# SMPS.net
KiCad netlist of a schematic drawn in Altium Designer
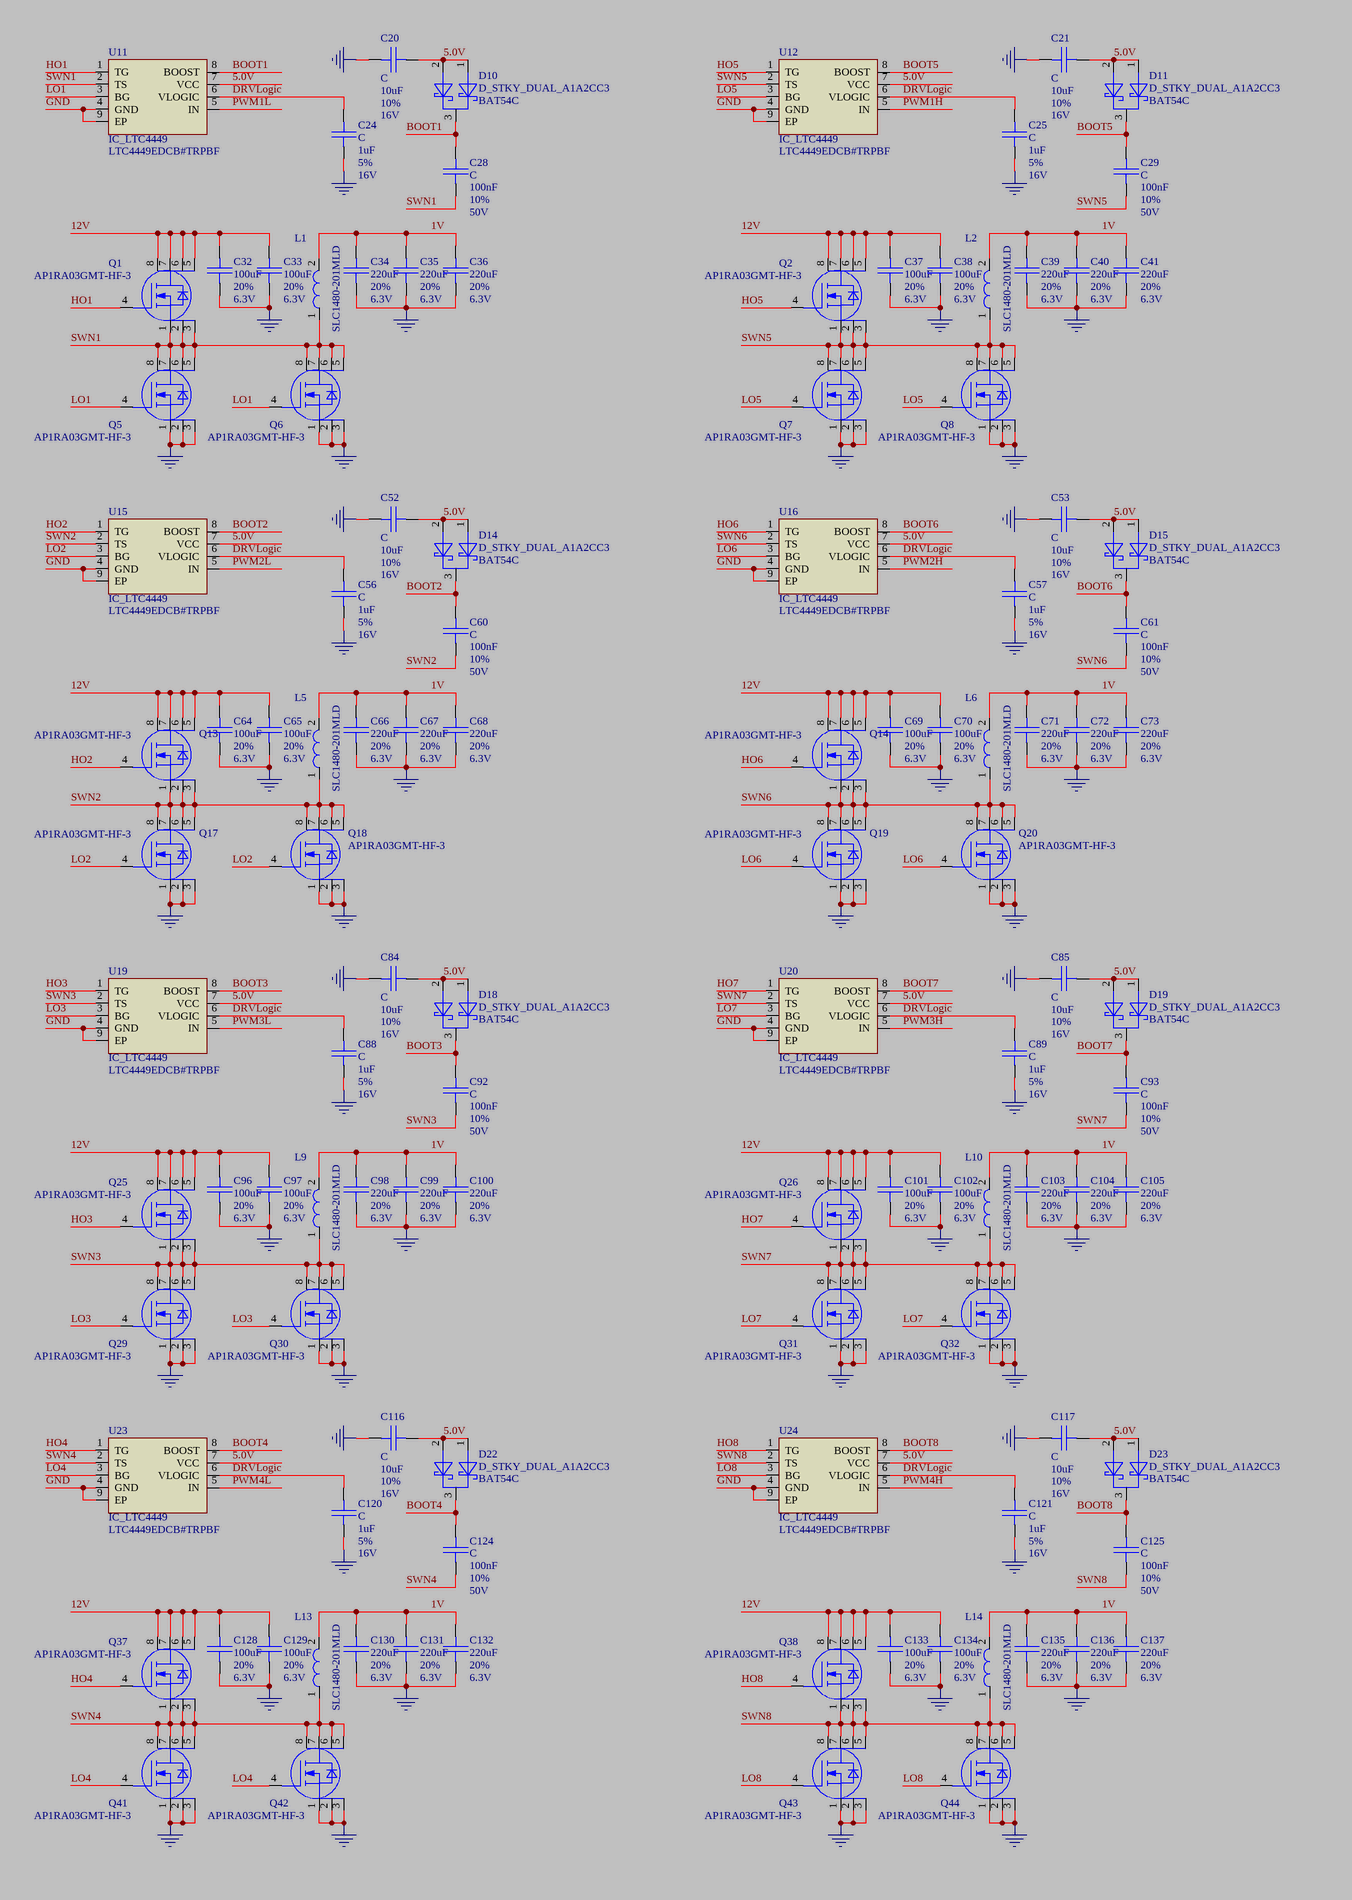
[diagram p0: SMPS.SchDoc, left]
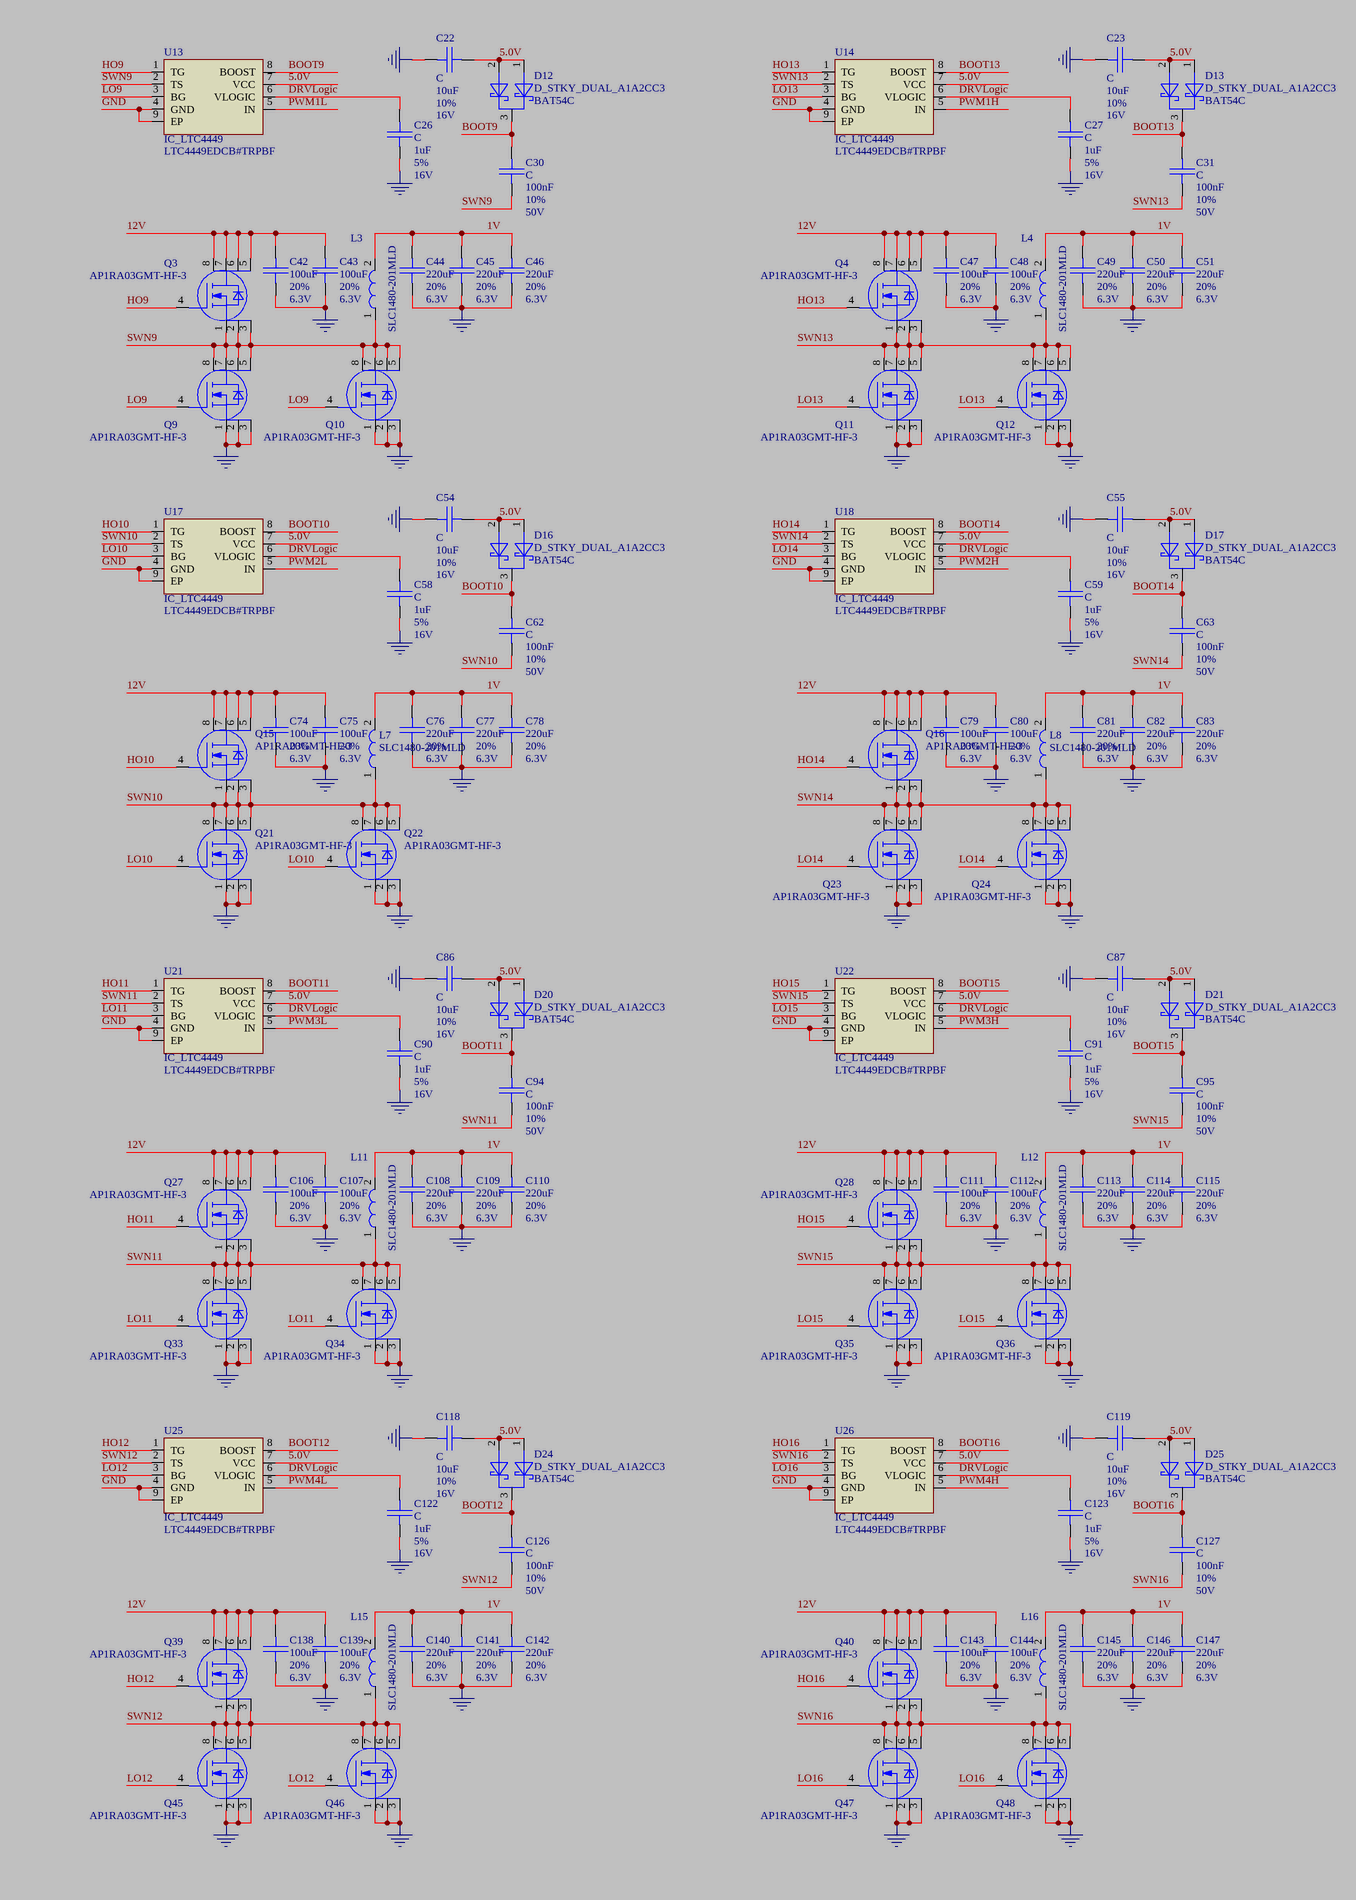
[diagram p1: SMPS.SchDoc, right]

(export (version "E")
  (design (tool "Eeschema 10.0.6"))
  (components
    (comp (ref "C20")
      (value "C")
      (footprint "SMD_0805_CAPC2012X145N")
      (fields
        (field (name "DB_PART_NUMBER") "CAP000043636")
        (field (name "DB_VALUE") "10uF")
        (field (name "DB_TOLERANCE") "10%")
        (field (name "DB_VOLTAGE") "16V")
        (field (name "DB_MANUFACTURER_PART") "KEMET    C0805C106K4PAC")
        (field (name "DB_APPROVED_BY") "ISHIDDEN=T")
      )
      (libsource (lib "Database_Libs1") (part "C"))
    )
    (comp (ref "C21")
      (value "C")
      (footprint "SMD_0805_CAPC2012X145N")
      (fields
        (field (name "DB_PART_NUMBER") "CAP000043636")
        (field (name "DB_VALUE") "10uF")
        (field (name "DB_TOLERANCE") "10%")
        (field (name "DB_VOLTAGE") "16V")
        (field (name "DB_MANUFACTURER_PART") "KEMET    C0805C106K4PAC")
        (field (name "DB_APPROVED_BY") "ISHIDDEN=T")
      )
      (libsource (lib "Database_Libs1") (part "C"))
    )
    (comp (ref "C22")
      (value "C")
      (footprint "SMD_0805_CAPC2012X145N")
      (fields
        (field (name "DB_PART_NUMBER") "CAP000043636")
        (field (name "DB_VALUE") "10uF")
        (field (name "DB_TOLERANCE") "10%")
        (field (name "DB_VOLTAGE") "16V")
        (field (name "DB_MANUFACTURER_PART") "KEMET    C0805C106K4PAC")
        (field (name "DB_APPROVED_BY") "ISHIDDEN=T")
      )
      (libsource (lib "Database_Libs1") (part "C"))
    )
    (comp (ref "C23")
      (value "C")
      (footprint "SMD_0805_CAPC2012X145N")
      (fields
        (field (name "DB_PART_NUMBER") "CAP000043636")
        (field (name "DB_VALUE") "10uF")
        (field (name "DB_TOLERANCE") "10%")
        (field (name "DB_VOLTAGE") "16V")
        (field (name "DB_MANUFACTURER_PART") "KEMET    C0805C106K4PAC")
        (field (name "DB_APPROVED_BY") "ISHIDDEN=T")
      )
      (libsource (lib "Database_Libs1") (part "C"))
    )
    (comp (ref "C24")
      (value "C")
      (footprint "SMD_0805_CAPC2012X145N")
      (fields
        (field (name "DB_PART_NUMBER") "CAP000028589")
        (field (name "DB_VALUE") "1uF")
        (field (name "DB_TOLERANCE") "5%")
        (field (name "DB_VOLTAGE") "16V")
        (field (name "DB_MANUFACTURER_PART") "KEMET    C0805C105J4RAC")
        (field (name "DB_APPROVED_BY") "ISHIDDEN=T")
      )
      (libsource (lib "Database_Libs1") (part "C"))
    )
    (comp (ref "C25")
      (value "C")
      (footprint "SMD_0805_CAPC2012X145N")
      (fields
        (field (name "DB_PART_NUMBER") "CAP000028589")
        (field (name "DB_VALUE") "1uF")
        (field (name "DB_TOLERANCE") "5%")
        (field (name "DB_VOLTAGE") "16V")
        (field (name "DB_MANUFACTURER_PART") "KEMET    C0805C105J4RAC")
        (field (name "DB_APPROVED_BY") "ISHIDDEN=T")
      )
      (libsource (lib "Database_Libs1") (part "C"))
    )
    (comp (ref "C26")
      (value "C")
      (footprint "SMD_0805_CAPC2012X145N")
      (fields
        (field (name "DB_PART_NUMBER") "CAP000028589")
        (field (name "DB_VALUE") "1uF")
        (field (name "DB_TOLERANCE") "5%")
        (field (name "DB_VOLTAGE") "16V")
        (field (name "DB_MANUFACTURER_PART") "KEMET    C0805C105J4RAC")
        (field (name "DB_APPROVED_BY") "ISHIDDEN=T")
      )
      (libsource (lib "Database_Libs1") (part "C"))
    )
    (comp (ref "C27")
      (value "C")
      (footprint "SMD_0805_CAPC2012X145N")
      (fields
        (field (name "DB_PART_NUMBER") "CAP000028589")
        (field (name "DB_VALUE") "1uF")
        (field (name "DB_TOLERANCE") "5%")
        (field (name "DB_VOLTAGE") "16V")
        (field (name "DB_MANUFACTURER_PART") "KEMET    C0805C105J4RAC")
        (field (name "DB_APPROVED_BY") "ISHIDDEN=T")
      )
      (libsource (lib "Database_Libs1") (part "C"))
    )
    (comp (ref "C28")
      (value "C")
      (footprint "SMD_0805_CAPC2012X145N")
      (fields
        (field (name "DB_PART_NUMBER") "CAP000027193")
        (field (name "DB_VALUE") "100nF")
        (field (name "DB_TOLERANCE") "10%")
        (field (name "DB_VOLTAGE") "50V")
        (field (name "DB_MANUFACTURER_PART") "KEMET    C0805C104K5RAC")
        (field (name "DB_APPROVED_BY") "ISHIDDEN=T")
      )
      (libsource (lib "Database_Libs1") (part "C"))
    )
    (comp (ref "C29")
      (value "C")
      (footprint "SMD_0805_CAPC2012X145N")
      (fields
        (field (name "DB_PART_NUMBER") "CAP000027193")
        (field (name "DB_VALUE") "100nF")
        (field (name "DB_TOLERANCE") "10%")
        (field (name "DB_VOLTAGE") "50V")
        (field (name "DB_MANUFACTURER_PART") "KEMET    C0805C104K5RAC")
        (field (name "DB_APPROVED_BY") "ISHIDDEN=T")
      )
      (libsource (lib "Database_Libs1") (part "C"))
    )
    (comp (ref "C30")
      (value "C")
      (footprint "SMD_0805_CAPC2012X145N")
      (fields
        (field (name "DB_PART_NUMBER") "CAP000027193")
        (field (name "DB_VALUE") "100nF")
        (field (name "DB_TOLERANCE") "10%")
        (field (name "DB_VOLTAGE") "50V")
        (field (name "DB_MANUFACTURER_PART") "KEMET    C0805C104K5RAC")
        (field (name "DB_APPROVED_BY") "ISHIDDEN=T")
      )
      (libsource (lib "Database_Libs1") (part "C"))
    )
    (comp (ref "C31")
      (value "C")
      (footprint "SMD_0805_CAPC2012X145N")
      (fields
        (field (name "DB_PART_NUMBER") "CAP000027193")
        (field (name "DB_VALUE") "100nF")
        (field (name "DB_TOLERANCE") "10%")
        (field (name "DB_VOLTAGE") "50V")
        (field (name "DB_MANUFACTURER_PART") "KEMET    C0805C104K5RAC")
        (field (name "DB_APPROVED_BY") "ISHIDDEN=T")
      )
      (libsource (lib "Database_Libs1") (part "C"))
    )
    (comp (ref "C32")
      (value "C")
      (footprint "SMD_1210_CAPC3225X270N")
      (fields
        (field (name "DB_PART_NUMBER") "CAP000043701")
        (field (name "DB_VALUE") "100uF")
        (field (name "DB_TOLERANCE") "20%")
        (field (name "DB_VOLTAGE") "6.3V")
        (field (name "DB_MANUFACTURER_PART") "KEMET    C1210C107M9PAC")
        (field (name "DB_APPROVED_BY") "ISHIDDEN=T")
      )
      (libsource (lib "Database_Libs1") (part "C"))
    )
    (comp (ref "C33")
      (value "C")
      (footprint "SMD_1210_CAPC3225X270N")
      (fields
        (field (name "DB_PART_NUMBER") "CAP000043701")
        (field (name "DB_VALUE") "100uF")
        (field (name "DB_TOLERANCE") "20%")
        (field (name "DB_VOLTAGE") "6.3V")
        (field (name "DB_MANUFACTURER_PART") "KEMET    C1210C107M9PAC")
        (field (name "DB_APPROVED_BY") "ISHIDDEN=T")
      )
      (libsource (lib "Database_Libs1") (part "C"))
    )
    (comp (ref "C34")
      (value "C")
      (footprint "SMD_1210_CAPC3225X279N")
      (fields
        (field (name "DB_PART_NUMBER") "CAP000047355")
        (field (name "DB_VALUE") "220uF")
        (field (name "DB_TOLERANCE") "20%")
        (field (name "DB_VOLTAGE") "6.3V")
        (field (name "DB_MANUFACTURER_PART") "SAMSUNG    CL32A227MQVNNNE")
        (field (name "DB_APPROVED_BY") "VSN")
      )
      (libsource (lib "Database_Libs1") (part "C"))
    )
    (comp (ref "C35")
      (value "C")
      (footprint "SMD_1210_CAPC3225X279N")
      (fields
        (field (name "DB_PART_NUMBER") "CAP000047355")
        (field (name "DB_VALUE") "220uF")
        (field (name "DB_TOLERANCE") "20%")
        (field (name "DB_VOLTAGE") "6.3V")
        (field (name "DB_MANUFACTURER_PART") "SAMSUNG    CL32A227MQVNNNE")
        (field (name "DB_APPROVED_BY") "VSN")
      )
      (libsource (lib "Database_Libs1") (part "C"))
    )
    (comp (ref "C36")
      (value "C")
      (footprint "SMD_1210_CAPC3225X279N")
      (fields
        (field (name "DB_PART_NUMBER") "CAP000047355")
        (field (name "DB_VALUE") "220uF")
        (field (name "DB_TOLERANCE") "20%")
        (field (name "DB_VOLTAGE") "6.3V")
        (field (name "DB_MANUFACTURER_PART") "SAMSUNG    CL32A227MQVNNNE")
        (field (name "DB_APPROVED_BY") "VSN")
      )
      (libsource (lib "Database_Libs1") (part "C"))
    )
    (comp (ref "C37")
      (value "C")
      (footprint "SMD_1210_CAPC3225X270N")
      (fields
        (field (name "DB_PART_NUMBER") "CAP000043701")
        (field (name "DB_VALUE") "100uF")
        (field (name "DB_TOLERANCE") "20%")
        (field (name "DB_VOLTAGE") "6.3V")
        (field (name "DB_MANUFACTURER_PART") "KEMET    C1210C107M9PAC")
        (field (name "DB_APPROVED_BY") "ISHIDDEN=T")
      )
      (libsource (lib "Database_Libs1") (part "C"))
    )
    (comp (ref "C38")
      (value "C")
      (footprint "SMD_1210_CAPC3225X270N")
      (fields
        (field (name "DB_PART_NUMBER") "CAP000043701")
        (field (name "DB_VALUE") "100uF")
        (field (name "DB_TOLERANCE") "20%")
        (field (name "DB_VOLTAGE") "6.3V")
        (field (name "DB_MANUFACTURER_PART") "KEMET    C1210C107M9PAC")
        (field (name "DB_APPROVED_BY") "ISHIDDEN=T")
      )
      (libsource (lib "Database_Libs1") (part "C"))
    )
    (comp (ref "C39")
      (value "C")
      (footprint "SMD_1210_CAPC3225X279N")
      (fields
        (field (name "DB_PART_NUMBER") "CAP000047355")
        (field (name "DB_VALUE") "220uF")
        (field (name "DB_TOLERANCE") "20%")
        (field (name "DB_VOLTAGE") "6.3V")
        (field (name "DB_MANUFACTURER_PART") "SAMSUNG    CL32A227MQVNNNE")
        (field (name "DB_APPROVED_BY") "VSN")
      )
      (libsource (lib "Database_Libs1") (part "C"))
    )
    (comp (ref "C40")
      (value "C")
      (footprint "SMD_1210_CAPC3225X279N")
      (fields
        (field (name "DB_PART_NUMBER") "CAP000047355")
        (field (name "DB_VALUE") "220uF")
        (field (name "DB_TOLERANCE") "20%")
        (field (name "DB_VOLTAGE") "6.3V")
        (field (name "DB_MANUFACTURER_PART") "SAMSUNG    CL32A227MQVNNNE")
        (field (name "DB_APPROVED_BY") "VSN")
      )
      (libsource (lib "Database_Libs1") (part "C"))
    )
    (comp (ref "C41")
      (value "C")
      (footprint "SMD_1210_CAPC3225X279N")
      (fields
        (field (name "DB_PART_NUMBER") "CAP000047355")
        (field (name "DB_VALUE") "220uF")
        (field (name "DB_TOLERANCE") "20%")
        (field (name "DB_VOLTAGE") "6.3V")
        (field (name "DB_MANUFACTURER_PART") "SAMSUNG    CL32A227MQVNNNE")
        (field (name "DB_APPROVED_BY") "VSN")
      )
      (libsource (lib "Database_Libs1") (part "C"))
    )
    (comp (ref "C42")
      (value "C")
      (footprint "SMD_1210_CAPC3225X270N")
      (fields
        (field (name "DB_PART_NUMBER") "CAP000043701")
        (field (name "DB_VALUE") "100uF")
        (field (name "DB_TOLERANCE") "20%")
        (field (name "DB_VOLTAGE") "6.3V")
        (field (name "DB_MANUFACTURER_PART") "KEMET    C1210C107M9PAC")
        (field (name "DB_APPROVED_BY") "ISHIDDEN=T")
      )
      (libsource (lib "Database_Libs1") (part "C"))
    )
    (comp (ref "C43")
      (value "C")
      (footprint "SMD_1210_CAPC3225X270N")
      (fields
        (field (name "DB_PART_NUMBER") "CAP000043701")
        (field (name "DB_VALUE") "100uF")
        (field (name "DB_TOLERANCE") "20%")
        (field (name "DB_VOLTAGE") "6.3V")
        (field (name "DB_MANUFACTURER_PART") "KEMET    C1210C107M9PAC")
        (field (name "DB_APPROVED_BY") "ISHIDDEN=T")
      )
      (libsource (lib "Database_Libs1") (part "C"))
    )
    (comp (ref "C44")
      (value "C")
      (footprint "SMD_1210_CAPC3225X279N")
      (fields
        (field (name "DB_PART_NUMBER") "CAP000047355")
        (field (name "DB_VALUE") "220uF")
        (field (name "DB_TOLERANCE") "20%")
        (field (name "DB_VOLTAGE") "6.3V")
        (field (name "DB_MANUFACTURER_PART") "SAMSUNG    CL32A227MQVNNNE")
        (field (name "DB_APPROVED_BY") "VSN")
      )
      (libsource (lib "Database_Libs1") (part "C"))
    )
    (comp (ref "C45")
      (value "C")
      (footprint "SMD_1210_CAPC3225X279N")
      (fields
        (field (name "DB_PART_NUMBER") "CAP000047355")
        (field (name "DB_VALUE") "220uF")
        (field (name "DB_TOLERANCE") "20%")
        (field (name "DB_VOLTAGE") "6.3V")
        (field (name "DB_MANUFACTURER_PART") "SAMSUNG    CL32A227MQVNNNE")
        (field (name "DB_APPROVED_BY") "VSN")
      )
      (libsource (lib "Database_Libs1") (part "C"))
    )
    (comp (ref "C46")
      (value "C")
      (footprint "SMD_1210_CAPC3225X279N")
      (fields
        (field (name "DB_PART_NUMBER") "CAP000047355")
        (field (name "DB_VALUE") "220uF")
        (field (name "DB_TOLERANCE") "20%")
        (field (name "DB_VOLTAGE") "6.3V")
        (field (name "DB_MANUFACTURER_PART") "SAMSUNG    CL32A227MQVNNNE")
        (field (name "DB_APPROVED_BY") "VSN")
      )
      (libsource (lib "Database_Libs1") (part "C"))
    )
    (comp (ref "C47")
      (value "C")
      (footprint "SMD_1210_CAPC3225X270N")
      (fields
        (field (name "DB_PART_NUMBER") "CAP000043701")
        (field (name "DB_VALUE") "100uF")
        (field (name "DB_TOLERANCE") "20%")
        (field (name "DB_VOLTAGE") "6.3V")
        (field (name "DB_MANUFACTURER_PART") "KEMET    C1210C107M9PAC")
        (field (name "DB_APPROVED_BY") "ISHIDDEN=T")
      )
      (libsource (lib "Database_Libs1") (part "C"))
    )
    (comp (ref "C48")
      (value "C")
      (footprint "SMD_1210_CAPC3225X270N")
      (fields
        (field (name "DB_PART_NUMBER") "CAP000043701")
        (field (name "DB_VALUE") "100uF")
        (field (name "DB_TOLERANCE") "20%")
        (field (name "DB_VOLTAGE") "6.3V")
        (field (name "DB_MANUFACTURER_PART") "KEMET    C1210C107M9PAC")
        (field (name "DB_APPROVED_BY") "ISHIDDEN=T")
      )
      (libsource (lib "Database_Libs1") (part "C"))
    )
    (comp (ref "C49")
      (value "C")
      (footprint "SMD_1210_CAPC3225X279N")
      (fields
        (field (name "DB_PART_NUMBER") "CAP000047355")
        (field (name "DB_VALUE") "220uF")
        (field (name "DB_TOLERANCE") "20%")
        (field (name "DB_VOLTAGE") "6.3V")
        (field (name "DB_MANUFACTURER_PART") "SAMSUNG    CL32A227MQVNNNE")
        (field (name "DB_APPROVED_BY") "VSN")
      )
      (libsource (lib "Database_Libs1") (part "C"))
    )
    (comp (ref "C50")
      (value "C")
      (footprint "SMD_1210_CAPC3225X279N")
      (fields
        (field (name "DB_PART_NUMBER") "CAP000047355")
        (field (name "DB_VALUE") "220uF")
        (field (name "DB_TOLERANCE") "20%")
        (field (name "DB_VOLTAGE") "6.3V")
        (field (name "DB_MANUFACTURER_PART") "SAMSUNG    CL32A227MQVNNNE")
        (field (name "DB_APPROVED_BY") "VSN")
      )
      (libsource (lib "Database_Libs1") (part "C"))
    )
    (comp (ref "C51")
      (value "C")
      (footprint "SMD_1210_CAPC3225X279N")
      (fields
        (field (name "DB_PART_NUMBER") "CAP000047355")
        (field (name "DB_VALUE") "220uF")
        (field (name "DB_TOLERANCE") "20%")
        (field (name "DB_VOLTAGE") "6.3V")
        (field (name "DB_MANUFACTURER_PART") "SAMSUNG    CL32A227MQVNNNE")
        (field (name "DB_APPROVED_BY") "VSN")
      )
      (libsource (lib "Database_Libs1") (part "C"))
    )
    (comp (ref "C52")
      (value "C")
      (footprint "SMD_0805_CAPC2012X145N")
      (fields
        (field (name "DB_PART_NUMBER") "CAP000043636")
        (field (name "DB_VALUE") "10uF")
        (field (name "DB_TOLERANCE") "10%")
        (field (name "DB_VOLTAGE") "16V")
        (field (name "DB_MANUFACTURER_PART") "KEMET    C0805C106K4PAC")
        (field (name "DB_APPROVED_BY") "ISHIDDEN=T")
      )
      (libsource (lib "Database_Libs1") (part "C"))
    )
    (comp (ref "C53")
      (value "C")
      (footprint "SMD_0805_CAPC2012X145N")
      (fields
        (field (name "DB_PART_NUMBER") "CAP000043636")
        (field (name "DB_VALUE") "10uF")
        (field (name "DB_TOLERANCE") "10%")
        (field (name "DB_VOLTAGE") "16V")
        (field (name "DB_MANUFACTURER_PART") "KEMET    C0805C106K4PAC")
        (field (name "DB_APPROVED_BY") "ISHIDDEN=T")
      )
      (libsource (lib "Database_Libs1") (part "C"))
    )
    (comp (ref "C54")
      (value "C")
      (footprint "SMD_0805_CAPC2012X145N")
      (fields
        (field (name "DB_PART_NUMBER") "CAP000043636")
        (field (name "DB_VALUE") "10uF")
        (field (name "DB_TOLERANCE") "10%")
        (field (name "DB_VOLTAGE") "16V")
        (field (name "DB_MANUFACTURER_PART") "KEMET    C0805C106K4PAC")
        (field (name "DB_APPROVED_BY") "ISHIDDEN=T")
      )
      (libsource (lib "Database_Libs1") (part "C"))
    )
    (comp (ref "C55")
      (value "C")
      (footprint "SMD_0805_CAPC2012X145N")
      (fields
        (field (name "DB_PART_NUMBER") "CAP000043636")
        (field (name "DB_VALUE") "10uF")
        (field (name "DB_TOLERANCE") "10%")
        (field (name "DB_VOLTAGE") "16V")
        (field (name "DB_MANUFACTURER_PART") "KEMET    C0805C106K4PAC")
        (field (name "DB_APPROVED_BY") "ISHIDDEN=T")
      )
      (libsource (lib "Database_Libs1") (part "C"))
    )
    (comp (ref "C56")
      (value "C")
      (footprint "SMD_0805_CAPC2012X145N")
      (fields
        (field (name "DB_PART_NUMBER") "CAP000028589")
        (field (name "DB_VALUE") "1uF")
        (field (name "DB_TOLERANCE") "5%")
        (field (name "DB_VOLTAGE") "16V")
        (field (name "DB_MANUFACTURER_PART") "KEMET    C0805C105J4RAC")
        (field (name "DB_APPROVED_BY") "ISHIDDEN=T")
      )
      (libsource (lib "Database_Libs1") (part "C"))
    )
    (comp (ref "C57")
      (value "C")
      (footprint "SMD_0805_CAPC2012X145N")
      (fields
        (field (name "DB_PART_NUMBER") "CAP000028589")
        (field (name "DB_VALUE") "1uF")
        (field (name "DB_TOLERANCE") "5%")
        (field (name "DB_VOLTAGE") "16V")
        (field (name "DB_MANUFACTURER_PART") "KEMET    C0805C105J4RAC")
        (field (name "DB_APPROVED_BY") "ISHIDDEN=T")
      )
      (libsource (lib "Database_Libs1") (part "C"))
    )
    (comp (ref "C58")
      (value "C")
      (footprint "SMD_0805_CAPC2012X145N")
      (fields
        (field (name "DB_PART_NUMBER") "CAP000028589")
        (field (name "DB_VALUE") "1uF")
        (field (name "DB_TOLERANCE") "5%")
        (field (name "DB_VOLTAGE") "16V")
        (field (name "DB_MANUFACTURER_PART") "KEMET    C0805C105J4RAC")
        (field (name "DB_APPROVED_BY") "ISHIDDEN=T")
      )
      (libsource (lib "Database_Libs1") (part "C"))
    )
    (comp (ref "C59")
      (value "C")
      (footprint "SMD_0805_CAPC2012X145N")
      (fields
        (field (name "DB_PART_NUMBER") "CAP000028589")
        (field (name "DB_VALUE") "1uF")
        (field (name "DB_TOLERANCE") "5%")
        (field (name "DB_VOLTAGE") "16V")
        (field (name "DB_MANUFACTURER_PART") "KEMET    C0805C105J4RAC")
        (field (name "DB_APPROVED_BY") "ISHIDDEN=T")
      )
      (libsource (lib "Database_Libs1") (part "C"))
    )
    (comp (ref "C60")
      (value "C")
      (footprint "SMD_0805_CAPC2012X145N")
      (fields
        (field (name "DB_PART_NUMBER") "CAP000027193")
        (field (name "DB_VALUE") "100nF")
        (field (name "DB_TOLERANCE") "10%")
        (field (name "DB_VOLTAGE") "50V")
        (field (name "DB_MANUFACTURER_PART") "KEMET    C0805C104K5RAC")
        (field (name "DB_APPROVED_BY") "ISHIDDEN=T")
      )
      (libsource (lib "Database_Libs1") (part "C"))
    )
    (comp (ref "C61")
      (value "C")
      (footprint "SMD_0805_CAPC2012X145N")
      (fields
        (field (name "DB_PART_NUMBER") "CAP000027193")
        (field (name "DB_VALUE") "100nF")
        (field (name "DB_TOLERANCE") "10%")
        (field (name "DB_VOLTAGE") "50V")
        (field (name "DB_MANUFACTURER_PART") "KEMET    C0805C104K5RAC")
        (field (name "DB_APPROVED_BY") "ISHIDDEN=T")
      )
      (libsource (lib "Database_Libs1") (part "C"))
    )
    (comp (ref "C62")
      (value "C")
      (footprint "SMD_0805_CAPC2012X145N")
      (fields
        (field (name "DB_PART_NUMBER") "CAP000027193")
        (field (name "DB_VALUE") "100nF")
        (field (name "DB_TOLERANCE") "10%")
        (field (name "DB_VOLTAGE") "50V")
        (field (name "DB_MANUFACTURER_PART") "KEMET    C0805C104K5RAC")
        (field (name "DB_APPROVED_BY") "ISHIDDEN=T")
      )
      (libsource (lib "Database_Libs1") (part "C"))
    )
    (comp (ref "C63")
      (value "C")
      (footprint "SMD_0805_CAPC2012X145N")
      (fields
        (field (name "DB_PART_NUMBER") "CAP000027193")
        (field (name "DB_VALUE") "100nF")
        (field (name "DB_TOLERANCE") "10%")
        (field (name "DB_VOLTAGE") "50V")
        (field (name "DB_MANUFACTURER_PART") "KEMET    C0805C104K5RAC")
        (field (name "DB_APPROVED_BY") "ISHIDDEN=T")
      )
      (libsource (lib "Database_Libs1") (part "C"))
    )
    (comp (ref "C64")
      (value "C")
      (footprint "SMD_1210_CAPC3225X270N")
      (fields
        (field (name "DB_PART_NUMBER") "CAP000043701")
        (field (name "DB_VALUE") "100uF")
        (field (name "DB_TOLERANCE") "20%")
        (field (name "DB_VOLTAGE") "6.3V")
        (field (name "DB_MANUFACTURER_PART") "KEMET    C1210C107M9PAC")
        (field (name "DB_APPROVED_BY") "ISHIDDEN=T")
      )
      (libsource (lib "Database_Libs1") (part "C"))
    )
    (comp (ref "C65")
      (value "C")
      (footprint "SMD_1210_CAPC3225X270N")
      (fields
        (field (name "DB_PART_NUMBER") "CAP000043701")
        (field (name "DB_VALUE") "100uF")
        (field (name "DB_TOLERANCE") "20%")
        (field (name "DB_VOLTAGE") "6.3V")
        (field (name "DB_MANUFACTURER_PART") "KEMET    C1210C107M9PAC")
        (field (name "DB_APPROVED_BY") "ISHIDDEN=T")
      )
      (libsource (lib "Database_Libs1") (part "C"))
    )
    (comp (ref "C66")
      (value "C")
      (footprint "SMD_1210_CAPC3225X279N")
      (fields
        (field (name "DB_PART_NUMBER") "CAP000047355")
        (field (name "DB_VALUE") "220uF")
        (field (name "DB_TOLERANCE") "20%")
        (field (name "DB_VOLTAGE") "6.3V")
        (field (name "DB_MANUFACTURER_PART") "SAMSUNG    CL32A227MQVNNNE")
        (field (name "DB_APPROVED_BY") "VSN")
      )
      (libsource (lib "Database_Libs1") (part "C"))
    )
    (comp (ref "C67")
      (value "C")
      (footprint "SMD_1210_CAPC3225X279N")
      (fields
        (field (name "DB_PART_NUMBER") "CAP000047355")
        (field (name "DB_VALUE") "220uF")
        (field (name "DB_TOLERANCE") "20%")
        (field (name "DB_VOLTAGE") "6.3V")
        (field (name "DB_MANUFACTURER_PART") "SAMSUNG    CL32A227MQVNNNE")
        (field (name "DB_APPROVED_BY") "VSN")
      )
      (libsource (lib "Database_Libs1") (part "C"))
    )
    (comp (ref "C68")
      (value "C")
      (footprint "SMD_1210_CAPC3225X279N")
      (fields
        (field (name "DB_PART_NUMBER") "CAP000047355")
        (field (name "DB_VALUE") "220uF")
        (field (name "DB_TOLERANCE") "20%")
        (field (name "DB_VOLTAGE") "6.3V")
        (field (name "DB_MANUFACTURER_PART") "SAMSUNG    CL32A227MQVNNNE")
        (field (name "DB_APPROVED_BY") "VSN")
      )
      (libsource (lib "Database_Libs1") (part "C"))
    )
    (comp (ref "C69")
      (value "C")
      (footprint "SMD_1210_CAPC3225X270N")
      (fields
        (field (name "DB_PART_NUMBER") "CAP000043701")
        (field (name "DB_VALUE") "100uF")
        (field (name "DB_TOLERANCE") "20%")
        (field (name "DB_VOLTAGE") "6.3V")
        (field (name "DB_MANUFACTURER_PART") "KEMET    C1210C107M9PAC")
        (field (name "DB_APPROVED_BY") "ISHIDDEN=T")
      )
      (libsource (lib "Database_Libs1") (part "C"))
    )
    (comp (ref "C70")
      (value "C")
      (footprint "SMD_1210_CAPC3225X270N")
      (fields
        (field (name "DB_PART_NUMBER") "CAP000043701")
        (field (name "DB_VALUE") "100uF")
        (field (name "DB_TOLERANCE") "20%")
        (field (name "DB_VOLTAGE") "6.3V")
        (field (name "DB_MANUFACTURER_PART") "KEMET    C1210C107M9PAC")
        (field (name "DB_APPROVED_BY") "ISHIDDEN=T")
      )
      (libsource (lib "Database_Libs1") (part "C"))
    )
    (comp (ref "C71")
      (value "C")
      (footprint "SMD_1210_CAPC3225X279N")
      (fields
        (field (name "DB_PART_NUMBER") "CAP000047355")
        (field (name "DB_VALUE") "220uF")
        (field (name "DB_TOLERANCE") "20%")
        (field (name "DB_VOLTAGE") "6.3V")
        (field (name "DB_MANUFACTURER_PART") "SAMSUNG    CL32A227MQVNNNE")
        (field (name "DB_APPROVED_BY") "VSN")
      )
      (libsource (lib "Database_Libs1") (part "C"))
    )
    (comp (ref "C72")
      (value "C")
      (footprint "SMD_1210_CAPC3225X279N")
      (fields
        (field (name "DB_PART_NUMBER") "CAP000047355")
        (field (name "DB_VALUE") "220uF")
        (field (name "DB_TOLERANCE") "20%")
        (field (name "DB_VOLTAGE") "6.3V")
        (field (name "DB_MANUFACTURER_PART") "SAMSUNG    CL32A227MQVNNNE")
        (field (name "DB_APPROVED_BY") "VSN")
      )
      (libsource (lib "Database_Libs1") (part "C"))
    )
    (comp (ref "C73")
      (value "C")
      (footprint "SMD_1210_CAPC3225X279N")
      (fields
        (field (name "DB_PART_NUMBER") "CAP000047355")
        (field (name "DB_VALUE") "220uF")
        (field (name "DB_TOLERANCE") "20%")
        (field (name "DB_VOLTAGE") "6.3V")
        (field (name "DB_MANUFACTURER_PART") "SAMSUNG    CL32A227MQVNNNE")
        (field (name "DB_APPROVED_BY") "VSN")
      )
      (libsource (lib "Database_Libs1") (part "C"))
    )
    (comp (ref "C74")
      (value "C")
      (footprint "SMD_1210_CAPC3225X270N")
      (fields
        (field (name "DB_PART_NUMBER") "CAP000043701")
        (field (name "DB_VALUE") "100uF")
        (field (name "DB_TOLERANCE") "20%")
        (field (name "DB_VOLTAGE") "6.3V")
        (field (name "DB_MANUFACTURER_PART") "KEMET    C1210C107M9PAC")
        (field (name "DB_APPROVED_BY") "ISHIDDEN=T")
      )
      (libsource (lib "Database_Libs1") (part "C"))
    )
    (comp (ref "C75")
      (value "C")
      (footprint "SMD_1210_CAPC3225X270N")
      (fields
        (field (name "DB_PART_NUMBER") "CAP000043701")
        (field (name "DB_VALUE") "100uF")
        (field (name "DB_TOLERANCE") "20%")
        (field (name "DB_VOLTAGE") "6.3V")
        (field (name "DB_MANUFACTURER_PART") "KEMET    C1210C107M9PAC")
        (field (name "DB_APPROVED_BY") "ISHIDDEN=T")
      )
      (libsource (lib "Database_Libs1") (part "C"))
    )
    (comp (ref "C76")
      (value "C")
      (footprint "SMD_1210_CAPC3225X279N")
      (fields
        (field (name "DB_PART_NUMBER") "CAP000047355")
        (field (name "DB_VALUE") "220uF")
        (field (name "DB_TOLERANCE") "20%")
        (field (name "DB_VOLTAGE") "6.3V")
        (field (name "DB_MANUFACTURER_PART") "SAMSUNG    CL32A227MQVNNNE")
        (field (name "DB_APPROVED_BY") "VSN")
      )
      (libsource (lib "Database_Libs1") (part "C"))
    )
    (comp (ref "C77")
      (value "C")
      (footprint "SMD_1210_CAPC3225X279N")
      (fields
        (field (name "DB_PART_NUMBER") "CAP000047355")
        (field (name "DB_VALUE") "220uF")
        (field (name "DB_TOLERANCE") "20%")
        (field (name "DB_VOLTAGE") "6.3V")
        (field (name "DB_MANUFACTURER_PART") "SAMSUNG    CL32A227MQVNNNE")
        (field (name "DB_APPROVED_BY") "VSN")
      )
      (libsource (lib "Database_Libs1") (part "C"))
    )
    (comp (ref "C78")
      (value "C")
      (footprint "SMD_1210_CAPC3225X279N")
      (fields
        (field (name "DB_PART_NUMBER") "CAP000047355")
        (field (name "DB_VALUE") "220uF")
        (field (name "DB_TOLERANCE") "20%")
        (field (name "DB_VOLTAGE") "6.3V")
        (field (name "DB_MANUFACTURER_PART") "SAMSUNG    CL32A227MQVNNNE")
        (field (name "DB_APPROVED_BY") "VSN")
      )
      (libsource (lib "Database_Libs1") (part "C"))
    )
    (comp (ref "C79")
      (value "C")
      (footprint "SMD_1210_CAPC3225X270N")
      (fields
        (field (name "DB_PART_NUMBER") "CAP000043701")
        (field (name "DB_VALUE") "100uF")
        (field (name "DB_TOLERANCE") "20%")
        (field (name "DB_VOLTAGE") "6.3V")
        (field (name "DB_MANUFACTURER_PART") "KEMET    C1210C107M9PAC")
        (field (name "DB_APPROVED_BY") "ISHIDDEN=T")
      )
      (libsource (lib "Database_Libs1") (part "C"))
    )
    (comp (ref "C80")
      (value "C")
      (footprint "SMD_1210_CAPC3225X270N")
      (fields
        (field (name "DB_PART_NUMBER") "CAP000043701")
        (field (name "DB_VALUE") "100uF")
        (field (name "DB_TOLERANCE") "20%")
        (field (name "DB_VOLTAGE") "6.3V")
        (field (name "DB_MANUFACTURER_PART") "KEMET    C1210C107M9PAC")
        (field (name "DB_APPROVED_BY") "ISHIDDEN=T")
      )
      (libsource (lib "Database_Libs1") (part "C"))
    )
    (comp (ref "C81")
      (value "C")
      (footprint "SMD_1210_CAPC3225X279N")
      (fields
        (field (name "DB_PART_NUMBER") "CAP000047355")
        (field (name "DB_VALUE") "220uF")
        (field (name "DB_TOLERANCE") "20%")
        (field (name "DB_VOLTAGE") "6.3V")
        (field (name "DB_MANUFACTURER_PART") "SAMSUNG    CL32A227MQVNNNE")
        (field (name "DB_APPROVED_BY") "VSN")
      )
      (libsource (lib "Database_Libs1") (part "C"))
    )
    (comp (ref "C82")
      (value "C")
      (footprint "SMD_1210_CAPC3225X279N")
      (fields
        (field (name "DB_PART_NUMBER") "CAP000047355")
        (field (name "DB_VALUE") "220uF")
        (field (name "DB_TOLERANCE") "20%")
        (field (name "DB_VOLTAGE") "6.3V")
        (field (name "DB_MANUFACTURER_PART") "SAMSUNG    CL32A227MQVNNNE")
        (field (name "DB_APPROVED_BY") "VSN")
      )
      (libsource (lib "Database_Libs1") (part "C"))
    )
    (comp (ref "C83")
      (value "C")
      (footprint "SMD_1210_CAPC3225X279N")
      (fields
        (field (name "DB_PART_NUMBER") "CAP000047355")
        (field (name "DB_VALUE") "220uF")
        (field (name "DB_TOLERANCE") "20%")
        (field (name "DB_VOLTAGE") "6.3V")
        (field (name "DB_MANUFACTURER_PART") "SAMSUNG    CL32A227MQVNNNE")
        (field (name "DB_APPROVED_BY") "VSN")
      )
      (libsource (lib "Database_Libs1") (part "C"))
    )
    (comp (ref "C84")
      (value "C")
      (footprint "SMD_0805_CAPC2012X145N")
      (fields
        (field (name "DB_PART_NUMBER") "CAP000043636")
        (field (name "DB_VALUE") "10uF")
        (field (name "DB_TOLERANCE") "10%")
        (field (name "DB_VOLTAGE") "16V")
        (field (name "DB_MANUFACTURER_PART") "KEMET    C0805C106K4PAC")
        (field (name "DB_APPROVED_BY") "ISHIDDEN=T")
      )
      (libsource (lib "Database_Libs1") (part "C"))
    )
    (comp (ref "C85")
      (value "C")
      (footprint "SMD_0805_CAPC2012X145N")
      (fields
        (field (name "DB_PART_NUMBER") "CAP000043636")
        (field (name "DB_VALUE") "10uF")
        (field (name "DB_TOLERANCE") "10%")
        (field (name "DB_VOLTAGE") "16V")
        (field (name "DB_MANUFACTURER_PART") "KEMET    C0805C106K4PAC")
        (field (name "DB_APPROVED_BY") "ISHIDDEN=T")
      )
      (libsource (lib "Database_Libs1") (part "C"))
    )
    (comp (ref "C86")
      (value "C")
      (footprint "SMD_0805_CAPC2012X145N")
      (fields
        (field (name "DB_PART_NUMBER") "CAP000043636")
        (field (name "DB_VALUE") "10uF")
        (field (name "DB_TOLERANCE") "10%")
        (field (name "DB_VOLTAGE") "16V")
        (field (name "DB_MANUFACTURER_PART") "KEMET    C0805C106K4PAC")
        (field (name "DB_APPROVED_BY") "ISHIDDEN=T")
      )
      (libsource (lib "Database_Libs1") (part "C"))
    )
    (comp (ref "C87")
      (value "C")
      (footprint "SMD_0805_CAPC2012X145N")
      (fields
        (field (name "DB_PART_NUMBER") "CAP000043636")
        (field (name "DB_VALUE") "10uF")
        (field (name "DB_TOLERANCE") "10%")
        (field (name "DB_VOLTAGE") "16V")
        (field (name "DB_MANUFACTURER_PART") "KEMET    C0805C106K4PAC")
        (field (name "DB_APPROVED_BY") "ISHIDDEN=T")
      )
      (libsource (lib "Database_Libs1") (part "C"))
    )
    (comp (ref "C88")
      (value "C")
      (footprint "SMD_0805_CAPC2012X145N")
      (fields
        (field (name "DB_PART_NUMBER") "CAP000028589")
        (field (name "DB_VALUE") "1uF")
        (field (name "DB_TOLERANCE") "5%")
        (field (name "DB_VOLTAGE") "16V")
        (field (name "DB_MANUFACTURER_PART") "KEMET    C0805C105J4RAC")
        (field (name "DB_APPROVED_BY") "ISHIDDEN=T")
      )
      (libsource (lib "Database_Libs1") (part "C"))
    )
    (comp (ref "C89")
      (value "C")
      (footprint "SMD_0805_CAPC2012X145N")
      (fields
        (field (name "DB_PART_NUMBER") "CAP000028589")
        (field (name "DB_VALUE") "1uF")
        (field (name "DB_TOLERANCE") "5%")
        (field (name "DB_VOLTAGE") "16V")
        (field (name "DB_MANUFACTURER_PART") "KEMET    C0805C105J4RAC")
        (field (name "DB_APPROVED_BY") "ISHIDDEN=T")
      )
      (libsource (lib "Database_Libs1") (part "C"))
    )
    (comp (ref "C90")
      (value "C")
      (footprint "SMD_0805_CAPC2012X145N")
      (fields
        (field (name "DB_PART_NUMBER") "CAP000028589")
        (field (name "DB_VALUE") "1uF")
        (field (name "DB_TOLERANCE") "5%")
        (field (name "DB_VOLTAGE") "16V")
        (field (name "DB_MANUFACTURER_PART") "KEMET    C0805C105J4RAC")
        (field (name "DB_APPROVED_BY") "ISHIDDEN=T")
      )
      (libsource (lib "Database_Libs1") (part "C"))
    )
    (comp (ref "C91")
      (value "C")
      (footprint "SMD_0805_CAPC2012X145N")
      (fields
        (field (name "DB_PART_NUMBER") "CAP000028589")
        (field (name "DB_VALUE") "1uF")
        (field (name "DB_TOLERANCE") "5%")
        (field (name "DB_VOLTAGE") "16V")
        (field (name "DB_MANUFACTURER_PART") "KEMET    C0805C105J4RAC")
        (field (name "DB_APPROVED_BY") "ISHIDDEN=T")
      )
      (libsource (lib "Database_Libs1") (part "C"))
    )
    (comp (ref "C92")
      (value "C")
      (footprint "SMD_0805_CAPC2012X145N")
      (fields
        (field (name "DB_PART_NUMBER") "CAP000027193")
        (field (name "DB_VALUE") "100nF")
        (field (name "DB_TOLERANCE") "10%")
        (field (name "DB_VOLTAGE") "50V")
        (field (name "DB_MANUFACTURER_PART") "KEMET    C0805C104K5RAC")
        (field (name "DB_APPROVED_BY") "ISHIDDEN=T")
      )
      (libsource (lib "Database_Libs1") (part "C"))
    )
    (comp (ref "C93")
      (value "C")
      (footprint "SMD_0805_CAPC2012X145N")
      (fields
        (field (name "DB_PART_NUMBER") "CAP000027193")
        (field (name "DB_VALUE") "100nF")
        (field (name "DB_TOLERANCE") "10%")
        (field (name "DB_VOLTAGE") "50V")
        (field (name "DB_MANUFACTURER_PART") "KEMET    C0805C104K5RAC")
        (field (name "DB_APPROVED_BY") "ISHIDDEN=T")
      )
      (libsource (lib "Database_Libs1") (part "C"))
    )
    (comp (ref "C94")
      (value "C")
      (footprint "SMD_0805_CAPC2012X145N")
      (fields
        (field (name "DB_PART_NUMBER") "CAP000027193")
        (field (name "DB_VALUE") "100nF")
        (field (name "DB_TOLERANCE") "10%")
        (field (name "DB_VOLTAGE") "50V")
        (field (name "DB_MANUFACTURER_PART") "KEMET    C0805C104K5RAC")
        (field (name "DB_APPROVED_BY") "ISHIDDEN=T")
      )
      (libsource (lib "Database_Libs1") (part "C"))
    )
    (comp (ref "C95")
      (value "C")
      (footprint "SMD_0805_CAPC2012X145N")
      (fields
        (field (name "DB_PART_NUMBER") "CAP000027193")
        (field (name "DB_VALUE") "100nF")
        (field (name "DB_TOLERANCE") "10%")
        (field (name "DB_VOLTAGE") "50V")
        (field (name "DB_MANUFACTURER_PART") "KEMET    C0805C104K5RAC")
        (field (name "DB_APPROVED_BY") "ISHIDDEN=T")
      )
      (libsource (lib "Database_Libs1") (part "C"))
    )
    (comp (ref "C96")
      (value "C")
      (footprint "SMD_1210_CAPC3225X270N")
      (fields
        (field (name "DB_PART_NUMBER") "CAP000043701")
        (field (name "DB_VALUE") "100uF")
        (field (name "DB_TOLERANCE") "20%")
        (field (name "DB_VOLTAGE") "6.3V")
        (field (name "DB_MANUFACTURER_PART") "KEMET    C1210C107M9PAC")
        (field (name "DB_APPROVED_BY") "ISHIDDEN=T")
      )
      (libsource (lib "Database_Libs1") (part "C"))
    )
    (comp (ref "C97")
      (value "C")
      (footprint "SMD_1210_CAPC3225X270N")
      (fields
        (field (name "DB_PART_NUMBER") "CAP000043701")
        (field (name "DB_VALUE") "100uF")
        (field (name "DB_TOLERANCE") "20%")
        (field (name "DB_VOLTAGE") "6.3V")
        (field (name "DB_MANUFACTURER_PART") "KEMET    C1210C107M9PAC")
        (field (name "DB_APPROVED_BY") "ISHIDDEN=T")
      )
      (libsource (lib "Database_Libs1") (part "C"))
    )
    (comp (ref "C98")
      (value "C")
      (footprint "SMD_1210_CAPC3225X279N")
      (fields
        (field (name "DB_PART_NUMBER") "CAP000047355")
        (field (name "DB_VALUE") "220uF")
        (field (name "DB_TOLERANCE") "20%")
        (field (name "DB_VOLTAGE") "6.3V")
        (field (name "DB_MANUFACTURER_PART") "SAMSUNG    CL32A227MQVNNNE")
        (field (name "DB_APPROVED_BY") "VSN")
      )
      (libsource (lib "Database_Libs1") (part "C"))
    )
    (comp (ref "C99")
      (value "C")
      (footprint "SMD_1210_CAPC3225X279N")
      (fields
        (field (name "DB_PART_NUMBER") "CAP000047355")
        (field (name "DB_VALUE") "220uF")
        (field (name "DB_TOLERANCE") "20%")
        (field (name "DB_VOLTAGE") "6.3V")
        (field (name "DB_MANUFACTURER_PART") "SAMSUNG    CL32A227MQVNNNE")
        (field (name "DB_APPROVED_BY") "VSN")
      )
      (libsource (lib "Database_Libs1") (part "C"))
    )
    (comp (ref "C100")
      (value "C")
      (footprint "SMD_1210_CAPC3225X279N")
      (fields
        (field (name "DB_PART_NUMBER") "CAP000047355")
        (field (name "DB_VALUE") "220uF")
        (field (name "DB_TOLERANCE") "20%")
        (field (name "DB_VOLTAGE") "6.3V")
        (field (name "DB_MANUFACTURER_PART") "SAMSUNG    CL32A227MQVNNNE")
        (field (name "DB_APPROVED_BY") "VSN")
      )
      (libsource (lib "Database_Libs1") (part "C"))
    )
    (comp (ref "C101")
      (value "C")
      (footprint "SMD_1210_CAPC3225X270N")
      (fields
        (field (name "DB_PART_NUMBER") "CAP000043701")
        (field (name "DB_VALUE") "100uF")
        (field (name "DB_TOLERANCE") "20%")
        (field (name "DB_VOLTAGE") "6.3V")
        (field (name "DB_MANUFACTURER_PART") "KEMET    C1210C107M9PAC")
        (field (name "DB_APPROVED_BY") "ISHIDDEN=T")
      )
      (libsource (lib "Database_Libs1") (part "C"))
    )
    (comp (ref "C102")
      (value "C")
      (footprint "SMD_1210_CAPC3225X270N")
      (fields
        (field (name "DB_PART_NUMBER") "CAP000043701")
        (field (name "DB_VALUE") "100uF")
        (field (name "DB_TOLERANCE") "20%")
        (field (name "DB_VOLTAGE") "6.3V")
        (field (name "DB_MANUFACTURER_PART") "KEMET    C1210C107M9PAC")
        (field (name "DB_APPROVED_BY") "ISHIDDEN=T")
      )
      (libsource (lib "Database_Libs1") (part "C"))
    )
    (comp (ref "C103")
      (value "C")
      (footprint "SMD_1210_CAPC3225X279N")
      (fields
        (field (name "DB_PART_NUMBER") "CAP000047355")
        (field (name "DB_VALUE") "220uF")
        (field (name "DB_TOLERANCE") "20%")
        (field (name "DB_VOLTAGE") "6.3V")
        (field (name "DB_MANUFACTURER_PART") "SAMSUNG    CL32A227MQVNNNE")
        (field (name "DB_APPROVED_BY") "VSN")
      )
      (libsource (lib "Database_Libs1") (part "C"))
    )
    (comp (ref "C104")
      (value "C")
      (footprint "SMD_1210_CAPC3225X279N")
      (fields
        (field (name "DB_PART_NUMBER") "CAP000047355")
        (field (name "DB_VALUE") "220uF")
        (field (name "DB_TOLERANCE") "20%")
        (field (name "DB_VOLTAGE") "6.3V")
        (field (name "DB_MANUFACTURER_PART") "SAMSUNG    CL32A227MQVNNNE")
        (field (name "DB_APPROVED_BY") "VSN")
      )
      (libsource (lib "Database_Libs1") (part "C"))
    )
    (comp (ref "C105")
      (value "C")
      (footprint "SMD_1210_CAPC3225X279N")
      (fields
        (field (name "DB_PART_NUMBER") "CAP000047355")
        (field (name "DB_VALUE") "220uF")
        (field (name "DB_TOLERANCE") "20%")
        (field (name "DB_VOLTAGE") "6.3V")
        (field (name "DB_MANUFACTURER_PART") "SAMSUNG    CL32A227MQVNNNE")
        (field (name "DB_APPROVED_BY") "VSN")
      )
      (libsource (lib "Database_Libs1") (part "C"))
    )
    (comp (ref "C106")
      (value "C")
      (footprint "SMD_1210_CAPC3225X270N")
      (fields
        (field (name "DB_PART_NUMBER") "CAP000043701")
        (field (name "DB_VALUE") "100uF")
        (field (name "DB_TOLERANCE") "20%")
        (field (name "DB_VOLTAGE") "6.3V")
        (field (name "DB_MANUFACTURER_PART") "KEMET    C1210C107M9PAC")
        (field (name "DB_APPROVED_BY") "ISHIDDEN=T")
      )
      (libsource (lib "Database_Libs1") (part "C"))
    )
    (comp (ref "C107")
      (value "C")
      (footprint "SMD_1210_CAPC3225X270N")
      (fields
        (field (name "DB_PART_NUMBER") "CAP000043701")
        (field (name "DB_VALUE") "100uF")
        (field (name "DB_TOLERANCE") "20%")
        (field (name "DB_VOLTAGE") "6.3V")
        (field (name "DB_MANUFACTURER_PART") "KEMET    C1210C107M9PAC")
        (field (name "DB_APPROVED_BY") "ISHIDDEN=T")
      )
      (libsource (lib "Database_Libs1") (part "C"))
    )
    (comp (ref "C108")
      (value "C")
      (footprint "SMD_1210_CAPC3225X279N")
      (fields
        (field (name "DB_PART_NUMBER") "CAP000047355")
        (field (name "DB_VALUE") "220uF")
        (field (name "DB_TOLERANCE") "20%")
        (field (name "DB_VOLTAGE") "6.3V")
        (field (name "DB_MANUFACTURER_PART") "SAMSUNG    CL32A227MQVNNNE")
        (field (name "DB_APPROVED_BY") "VSN")
      )
      (libsource (lib "Database_Libs1") (part "C"))
    )
    (comp (ref "C109")
      (value "C")
      (footprint "SMD_1210_CAPC3225X279N")
      (fields
        (field (name "DB_PART_NUMBER") "CAP000047355")
        (field (name "DB_VALUE") "220uF")
        (field (name "DB_TOLERANCE") "20%")
        (field (name "DB_VOLTAGE") "6.3V")
        (field (name "DB_MANUFACTURER_PART") "SAMSUNG    CL32A227MQVNNNE")
        (field (name "DB_APPROVED_BY") "VSN")
      )
      (libsource (lib "Database_Libs1") (part "C"))
    )
    (comp (ref "C110")
      (value "C")
      (footprint "SMD_1210_CAPC3225X279N")
      (fields
        (field (name "DB_PART_NUMBER") "CAP000047355")
        (field (name "DB_VALUE") "220uF")
        (field (name "DB_TOLERANCE") "20%")
        (field (name "DB_VOLTAGE") "6.3V")
        (field (name "DB_MANUFACTURER_PART") "SAMSUNG    CL32A227MQVNNNE")
        (field (name "DB_APPROVED_BY") "VSN")
      )
      (libsource (lib "Database_Libs1") (part "C"))
    )
    (comp (ref "C111")
      (value "C")
      (footprint "SMD_1210_CAPC3225X270N")
      (fields
        (field (name "DB_PART_NUMBER") "CAP000043701")
        (field (name "DB_VALUE") "100uF")
        (field (name "DB_TOLERANCE") "20%")
        (field (name "DB_VOLTAGE") "6.3V")
        (field (name "DB_MANUFACTURER_PART") "KEMET    C1210C107M9PAC")
        (field (name "DB_APPROVED_BY") "ISHIDDEN=T")
      )
      (libsource (lib "Database_Libs1") (part "C"))
    )
    (comp (ref "C112")
      (value "C")
      (footprint "SMD_1210_CAPC3225X270N")
      (fields
        (field (name "DB_PART_NUMBER") "CAP000043701")
        (field (name "DB_VALUE") "100uF")
        (field (name "DB_TOLERANCE") "20%")
        (field (name "DB_VOLTAGE") "6.3V")
        (field (name "DB_MANUFACTURER_PART") "KEMET    C1210C107M9PAC")
        (field (name "DB_APPROVED_BY") "ISHIDDEN=T")
      )
      (libsource (lib "Database_Libs1") (part "C"))
    )
    (comp (ref "C113")
      (value "C")
      (footprint "SMD_1210_CAPC3225X279N")
      (fields
        (field (name "DB_PART_NUMBER") "CAP000047355")
        (field (name "DB_VALUE") "220uF")
        (field (name "DB_TOLERANCE") "20%")
        (field (name "DB_VOLTAGE") "6.3V")
        (field (name "DB_MANUFACTURER_PART") "SAMSUNG    CL32A227MQVNNNE")
        (field (name "DB_APPROVED_BY") "VSN")
      )
      (libsource (lib "Database_Libs1") (part "C"))
    )
    (comp (ref "C114")
      (value "C")
      (footprint "SMD_1210_CAPC3225X279N")
      (fields
        (field (name "DB_PART_NUMBER") "CAP000047355")
        (field (name "DB_VALUE") "220uF")
        (field (name "DB_TOLERANCE") "20%")
        (field (name "DB_VOLTAGE") "6.3V")
        (field (name "DB_MANUFACTURER_PART") "SAMSUNG    CL32A227MQVNNNE")
        (field (name "DB_APPROVED_BY") "VSN")
      )
      (libsource (lib "Database_Libs1") (part "C"))
    )
    (comp (ref "C115")
      (value "C")
      (footprint "SMD_1210_CAPC3225X279N")
      (fields
        (field (name "DB_PART_NUMBER") "CAP000047355")
        (field (name "DB_VALUE") "220uF")
        (field (name "DB_TOLERANCE") "20%")
        (field (name "DB_VOLTAGE") "6.3V")
        (field (name "DB_MANUFACTURER_PART") "SAMSUNG    CL32A227MQVNNNE")
        (field (name "DB_APPROVED_BY") "VSN")
      )
      (libsource (lib "Database_Libs1") (part "C"))
    )
    (comp (ref "C116")
      (value "C")
      (footprint "SMD_0805_CAPC2012X145N")
      (fields
        (field (name "DB_PART_NUMBER") "CAP000043636")
        (field (name "DB_VALUE") "10uF")
        (field (name "DB_TOLERANCE") "10%")
        (field (name "DB_VOLTAGE") "16V")
        (field (name "DB_MANUFACTURER_PART") "KEMET    C0805C106K4PAC")
        (field (name "DB_APPROVED_BY") "ISHIDDEN=T")
      )
      (libsource (lib "Database_Libs1") (part "C"))
    )
    (comp (ref "C117")
      (value "C")
      (footprint "SMD_0805_CAPC2012X145N")
      (fields
        (field (name "DB_PART_NUMBER") "CAP000043636")
        (field (name "DB_VALUE") "10uF")
        (field (name "DB_TOLERANCE") "10%")
        (field (name "DB_VOLTAGE") "16V")
        (field (name "DB_MANUFACTURER_PART") "KEMET    C0805C106K4PAC")
        (field (name "DB_APPROVED_BY") "ISHIDDEN=T")
      )
      (libsource (lib "Database_Libs1") (part "C"))
    )
    (comp (ref "C118")
      (value "C")
      (footprint "SMD_0805_CAPC2012X145N")
      (fields
        (field (name "DB_PART_NUMBER") "CAP000043636")
        (field (name "DB_VALUE") "10uF")
        (field (name "DB_TOLERANCE") "10%")
        (field (name "DB_VOLTAGE") "16V")
        (field (name "DB_MANUFACTURER_PART") "KEMET    C0805C106K4PAC")
        (field (name "DB_APPROVED_BY") "ISHIDDEN=T")
      )
      (libsource (lib "Database_Libs1") (part "C"))
    )
    (comp (ref "C119")
      (value "C")
      (footprint "SMD_0805_CAPC2012X145N")
      (fields
        (field (name "DB_PART_NUMBER") "CAP000043636")
        (field (name "DB_VALUE") "10uF")
        (field (name "DB_TOLERANCE") "10%")
        (field (name "DB_VOLTAGE") "16V")
        (field (name "DB_MANUFACTURER_PART") "KEMET    C0805C106K4PAC")
        (field (name "DB_APPROVED_BY") "ISHIDDEN=T")
      )
      (libsource (lib "Database_Libs1") (part "C"))
    )
    (comp (ref "C120")
      (value "C")
      (footprint "SMD_0805_CAPC2012X145N")
      (fields
        (field (name "DB_PART_NUMBER") "CAP000028589")
        (field (name "DB_VALUE") "1uF")
        (field (name "DB_TOLERANCE") "5%")
        (field (name "DB_VOLTAGE") "16V")
        (field (name "DB_MANUFACTURER_PART") "KEMET    C0805C105J4RAC")
        (field (name "DB_APPROVED_BY") "ISHIDDEN=T")
      )
      (libsource (lib "Database_Libs1") (part "C"))
    )
    (comp (ref "C121")
      (value "C")
      (footprint "SMD_0805_CAPC2012X145N")
      (fields
        (field (name "DB_PART_NUMBER") "CAP000028589")
        (field (name "DB_VALUE") "1uF")
        (field (name "DB_TOLERANCE") "5%")
        (field (name "DB_VOLTAGE") "16V")
        (field (name "DB_MANUFACTURER_PART") "KEMET    C0805C105J4RAC")
        (field (name "DB_APPROVED_BY") "ISHIDDEN=T")
      )
      (libsource (lib "Database_Libs1") (part "C"))
    )
    (comp (ref "C122")
      (value "C")
      (footprint "SMD_0805_CAPC2012X145N")
      (fields
        (field (name "DB_PART_NUMBER") "CAP000028589")
        (field (name "DB_VALUE") "1uF")
        (field (name "DB_TOLERANCE") "5%")
        (field (name "DB_VOLTAGE") "16V")
        (field (name "DB_MANUFACTURER_PART") "KEMET    C0805C105J4RAC")
        (field (name "DB_APPROVED_BY") "ISHIDDEN=T")
      )
      (libsource (lib "Database_Libs1") (part "C"))
    )
    (comp (ref "C123")
      (value "C")
      (footprint "SMD_0805_CAPC2012X145N")
      (fields
        (field (name "DB_PART_NUMBER") "CAP000028589")
        (field (name "DB_VALUE") "1uF")
        (field (name "DB_TOLERANCE") "5%")
        (field (name "DB_VOLTAGE") "16V")
        (field (name "DB_MANUFACTURER_PART") "KEMET    C0805C105J4RAC")
        (field (name "DB_APPROVED_BY") "ISHIDDEN=T")
      )
      (libsource (lib "Database_Libs1") (part "C"))
    )
    (comp (ref "C124")
      (value "C")
      (footprint "SMD_0805_CAPC2012X145N")
      (fields
        (field (name "DB_PART_NUMBER") "CAP000027193")
        (field (name "DB_VALUE") "100nF")
        (field (name "DB_TOLERANCE") "10%")
        (field (name "DB_VOLTAGE") "50V")
        (field (name "DB_MANUFACTURER_PART") "KEMET    C0805C104K5RAC")
        (field (name "DB_APPROVED_BY") "ISHIDDEN=T")
      )
      (libsource (lib "Database_Libs1") (part "C"))
    )
    (comp (ref "C125")
      (value "C")
      (footprint "SMD_0805_CAPC2012X145N")
      (fields
        (field (name "DB_PART_NUMBER") "CAP000027193")
        (field (name "DB_VALUE") "100nF")
        (field (name "DB_TOLERANCE") "10%")
        (field (name "DB_VOLTAGE") "50V")
        (field (name "DB_MANUFACTURER_PART") "KEMET    C0805C104K5RAC")
        (field (name "DB_APPROVED_BY") "ISHIDDEN=T")
      )
      (libsource (lib "Database_Libs1") (part "C"))
    )
    (comp (ref "C126")
      (value "C")
      (footprint "SMD_0805_CAPC2012X145N")
      (fields
        (field (name "DB_PART_NUMBER") "CAP000027193")
        (field (name "DB_VALUE") "100nF")
        (field (name "DB_TOLERANCE") "10%")
        (field (name "DB_VOLTAGE") "50V")
        (field (name "DB_MANUFACTURER_PART") "KEMET    C0805C104K5RAC")
        (field (name "DB_APPROVED_BY") "ISHIDDEN=T")
      )
      (libsource (lib "Database_Libs1") (part "C"))
    )
    (comp (ref "C127")
      (value "C")
      (footprint "SMD_0805_CAPC2012X145N")
      (fields
        (field (name "DB_PART_NUMBER") "CAP000027193")
        (field (name "DB_VALUE") "100nF")
        (field (name "DB_TOLERANCE") "10%")
        (field (name "DB_VOLTAGE") "50V")
        (field (name "DB_MANUFACTURER_PART") "KEMET    C0805C104K5RAC")
        (field (name "DB_APPROVED_BY") "ISHIDDEN=T")
      )
      (libsource (lib "Database_Libs1") (part "C"))
    )
    (comp (ref "C128")
      (value "C")
      (footprint "SMD_1210_CAPC3225X270N")
      (fields
        (field (name "DB_PART_NUMBER") "CAP000043701")
        (field (name "DB_VALUE") "100uF")
        (field (name "DB_TOLERANCE") "20%")
        (field (name "DB_VOLTAGE") "6.3V")
        (field (name "DB_MANUFACTURER_PART") "KEMET    C1210C107M9PAC")
        (field (name "DB_APPROVED_BY") "ISHIDDEN=T")
      )
      (libsource (lib "Database_Libs1") (part "C"))
    )
    (comp (ref "C129")
      (value "C")
      (footprint "SMD_1210_CAPC3225X270N")
      (fields
        (field (name "DB_PART_NUMBER") "CAP000043701")
        (field (name "DB_VALUE") "100uF")
        (field (name "DB_TOLERANCE") "20%")
        (field (name "DB_VOLTAGE") "6.3V")
        (field (name "DB_MANUFACTURER_PART") "KEMET    C1210C107M9PAC")
        (field (name "DB_APPROVED_BY") "ISHIDDEN=T")
      )
      (libsource (lib "Database_Libs1") (part "C"))
    )
    (comp (ref "C130")
      (value "C")
      (footprint "SMD_1210_CAPC3225X279N")
      (fields
        (field (name "DB_PART_NUMBER") "CAP000047355")
        (field (name "DB_VALUE") "220uF")
        (field (name "DB_TOLERANCE") "20%")
        (field (name "DB_VOLTAGE") "6.3V")
        (field (name "DB_MANUFACTURER_PART") "SAMSUNG    CL32A227MQVNNNE")
        (field (name "DB_APPROVED_BY") "VSN")
      )
      (libsource (lib "Database_Libs1") (part "C"))
    )
    (comp (ref "C131")
      (value "C")
      (footprint "SMD_1210_CAPC3225X279N")
      (fields
        (field (name "DB_PART_NUMBER") "CAP000047355")
        (field (name "DB_VALUE") "220uF")
        (field (name "DB_TOLERANCE") "20%")
        (field (name "DB_VOLTAGE") "6.3V")
        (field (name "DB_MANUFACTURER_PART") "SAMSUNG    CL32A227MQVNNNE")
        (field (name "DB_APPROVED_BY") "VSN")
      )
      (libsource (lib "Database_Libs1") (part "C"))
    )
    (comp (ref "C132")
      (value "C")
      (footprint "SMD_1210_CAPC3225X279N")
      (fields
        (field (name "DB_PART_NUMBER") "CAP000047355")
        (field (name "DB_VALUE") "220uF")
        (field (name "DB_TOLERANCE") "20%")
        (field (name "DB_VOLTAGE") "6.3V")
        (field (name "DB_MANUFACTURER_PART") "SAMSUNG    CL32A227MQVNNNE")
        (field (name "DB_APPROVED_BY") "VSN")
      )
      (libsource (lib "Database_Libs1") (part "C"))
    )
    (comp (ref "C133")
      (value "C")
      (footprint "SMD_1210_CAPC3225X270N")
      (fields
        (field (name "DB_PART_NUMBER") "CAP000043701")
        (field (name "DB_VALUE") "100uF")
        (field (name "DB_TOLERANCE") "20%")
        (field (name "DB_VOLTAGE") "6.3V")
        (field (name "DB_MANUFACTURER_PART") "KEMET    C1210C107M9PAC")
        (field (name "DB_APPROVED_BY") "ISHIDDEN=T")
      )
      (libsource (lib "Database_Libs1") (part "C"))
    )
    (comp (ref "C134")
      (value "C")
      (footprint "SMD_1210_CAPC3225X270N")
      (fields
        (field (name "DB_PART_NUMBER") "CAP000043701")
        (field (name "DB_VALUE") "100uF")
        (field (name "DB_TOLERANCE") "20%")
        (field (name "DB_VOLTAGE") "6.3V")
        (field (name "DB_MANUFACTURER_PART") "KEMET    C1210C107M9PAC")
        (field (name "DB_APPROVED_BY") "ISHIDDEN=T")
      )
      (libsource (lib "Database_Libs1") (part "C"))
    )
    (comp (ref "C135")
      (value "C")
      (footprint "SMD_1210_CAPC3225X279N")
      (fields
        (field (name "DB_PART_NUMBER") "CAP000047355")
        (field (name "DB_VALUE") "220uF")
        (field (name "DB_TOLERANCE") "20%")
        (field (name "DB_VOLTAGE") "6.3V")
        (field (name "DB_MANUFACTURER_PART") "SAMSUNG    CL32A227MQVNNNE")
        (field (name "DB_APPROVED_BY") "VSN")
      )
      (libsource (lib "Database_Libs1") (part "C"))
    )
    (comp (ref "C136")
      (value "C")
      (footprint "SMD_1210_CAPC3225X279N")
      (fields
        (field (name "DB_PART_NUMBER") "CAP000047355")
        (field (name "DB_VALUE") "220uF")
        (field (name "DB_TOLERANCE") "20%")
        (field (name "DB_VOLTAGE") "6.3V")
        (field (name "DB_MANUFACTURER_PART") "SAMSUNG    CL32A227MQVNNNE")
        (field (name "DB_APPROVED_BY") "VSN")
      )
      (libsource (lib "Database_Libs1") (part "C"))
    )
    (comp (ref "C137")
      (value "C")
      (footprint "SMD_1210_CAPC3225X279N")
      (fields
        (field (name "DB_PART_NUMBER") "CAP000047355")
        (field (name "DB_VALUE") "220uF")
        (field (name "DB_TOLERANCE") "20%")
        (field (name "DB_VOLTAGE") "6.3V")
        (field (name "DB_MANUFACTURER_PART") "SAMSUNG    CL32A227MQVNNNE")
        (field (name "DB_APPROVED_BY") "VSN")
      )
      (libsource (lib "Database_Libs1") (part "C"))
    )
    (comp (ref "C138")
      (value "C")
      (footprint "SMD_1210_CAPC3225X270N")
      (fields
        (field (name "DB_PART_NUMBER") "CAP000043701")
        (field (name "DB_VALUE") "100uF")
        (field (name "DB_TOLERANCE") "20%")
        (field (name "DB_VOLTAGE") "6.3V")
        (field (name "DB_MANUFACTURER_PART") "KEMET    C1210C107M9PAC")
        (field (name "DB_APPROVED_BY") "ISHIDDEN=T")
      )
      (libsource (lib "Database_Libs1") (part "C"))
    )
    (comp (ref "C139")
      (value "C")
      (footprint "SMD_1210_CAPC3225X270N")
      (fields
        (field (name "DB_PART_NUMBER") "CAP000043701")
        (field (name "DB_VALUE") "100uF")
        (field (name "DB_TOLERANCE") "20%")
        (field (name "DB_VOLTAGE") "6.3V")
        (field (name "DB_MANUFACTURER_PART") "KEMET    C1210C107M9PAC")
        (field (name "DB_APPROVED_BY") "ISHIDDEN=T")
      )
      (libsource (lib "Database_Libs1") (part "C"))
    )
    (comp (ref "C140")
      (value "C")
      (footprint "SMD_1210_CAPC3225X279N")
      (fields
        (field (name "DB_PART_NUMBER") "CAP000047355")
        (field (name "DB_VALUE") "220uF")
        (field (name "DB_TOLERANCE") "20%")
        (field (name "DB_VOLTAGE") "6.3V")
        (field (name "DB_MANUFACTURER_PART") "SAMSUNG    CL32A227MQVNNNE")
        (field (name "DB_APPROVED_BY") "VSN")
      )
      (libsource (lib "Database_Libs1") (part "C"))
    )
    (comp (ref "C141")
      (value "C")
      (footprint "SMD_1210_CAPC3225X279N")
      (fields
        (field (name "DB_PART_NUMBER") "CAP000047355")
        (field (name "DB_VALUE") "220uF")
        (field (name "DB_TOLERANCE") "20%")
        (field (name "DB_VOLTAGE") "6.3V")
        (field (name "DB_MANUFACTURER_PART") "SAMSUNG    CL32A227MQVNNNE")
        (field (name "DB_APPROVED_BY") "VSN")
      )
      (libsource (lib "Database_Libs1") (part "C"))
    )
    (comp (ref "C142")
      (value "C")
      (footprint "SMD_1210_CAPC3225X279N")
      (fields
        (field (name "DB_PART_NUMBER") "CAP000047355")
        (field (name "DB_VALUE") "220uF")
        (field (name "DB_TOLERANCE") "20%")
        (field (name "DB_VOLTAGE") "6.3V")
        (field (name "DB_MANUFACTURER_PART") "SAMSUNG    CL32A227MQVNNNE")
        (field (name "DB_APPROVED_BY") "VSN")
      )
      (libsource (lib "Database_Libs1") (part "C"))
    )
    (comp (ref "C143")
      (value "C")
      (footprint "SMD_1210_CAPC3225X270N")
      (fields
        (field (name "DB_PART_NUMBER") "CAP000043701")
        (field (name "DB_VALUE") "100uF")
        (field (name "DB_TOLERANCE") "20%")
        (field (name "DB_VOLTAGE") "6.3V")
        (field (name "DB_MANUFACTURER_PART") "KEMET    C1210C107M9PAC")
        (field (name "DB_APPROVED_BY") "ISHIDDEN=T")
      )
      (libsource (lib "Database_Libs1") (part "C"))
    )
    (comp (ref "C144")
      (value "C")
      (footprint "SMD_1210_CAPC3225X270N")
      (fields
        (field (name "DB_PART_NUMBER") "CAP000043701")
        (field (name "DB_VALUE") "100uF")
        (field (name "DB_TOLERANCE") "20%")
        (field (name "DB_VOLTAGE") "6.3V")
        (field (name "DB_MANUFACTURER_PART") "KEMET    C1210C107M9PAC")
        (field (name "DB_APPROVED_BY") "ISHIDDEN=T")
      )
      (libsource (lib "Database_Libs1") (part "C"))
    )
    (comp (ref "C145")
      (value "C")
      (footprint "SMD_1210_CAPC3225X279N")
      (fields
        (field (name "DB_PART_NUMBER") "CAP000047355")
        (field (name "DB_VALUE") "220uF")
        (field (name "DB_TOLERANCE") "20%")
        (field (name "DB_VOLTAGE") "6.3V")
        (field (name "DB_MANUFACTURER_PART") "SAMSUNG    CL32A227MQVNNNE")
        (field (name "DB_APPROVED_BY") "VSN")
      )
      (libsource (lib "Database_Libs1") (part "C"))
    )
    (comp (ref "C146")
      (value "C")
      (footprint "SMD_1210_CAPC3225X279N")
      (fields
        (field (name "DB_PART_NUMBER") "CAP000047355")
        (field (name "DB_VALUE") "220uF")
        (field (name "DB_TOLERANCE") "20%")
        (field (name "DB_VOLTAGE") "6.3V")
        (field (name "DB_MANUFACTURER_PART") "SAMSUNG    CL32A227MQVNNNE")
        (field (name "DB_APPROVED_BY") "VSN")
      )
      (libsource (lib "Database_Libs1") (part "C"))
    )
    (comp (ref "C147")
      (value "C")
      (footprint "SMD_1210_CAPC3225X279N")
      (fields
        (field (name "DB_PART_NUMBER") "CAP000047355")
        (field (name "DB_VALUE") "220uF")
        (field (name "DB_TOLERANCE") "20%")
        (field (name "DB_VOLTAGE") "6.3V")
        (field (name "DB_MANUFACTURER_PART") "SAMSUNG    CL32A227MQVNNNE")
        (field (name "DB_APPROVED_BY") "VSN")
      )
      (libsource (lib "Database_Libs1") (part "C"))
    )
    (comp (ref "D10")
      (value "D_STKY_DUAL_A1A2CC3")
      (footprint "SMD_SOT23_SOT95P240X120-3N")
      (fields
        (field (name "DB_PART_NUMBER") "DDE000000490")
        (field (name "DB_VALUE") "BAT54C")
        (field (name "DB_MANUFACTURER_PART") "Diodes        BAT54C")
        (field (name "DB_APPROVED_BY") "ISHIDDEN=T")
      )
      (libsource (lib "Database_Libs1") (part "D_STKY_DUAL_A1A2CC3"))
    )
    (comp (ref "D11")
      (value "D_STKY_DUAL_A1A2CC3")
      (footprint "SMD_SOT23_SOT95P240X120-3N")
      (fields
        (field (name "DB_PART_NUMBER") "DDE000000490")
        (field (name "DB_VALUE") "BAT54C")
        (field (name "DB_MANUFACTURER_PART") "Diodes        BAT54C")
        (field (name "DB_APPROVED_BY") "ISHIDDEN=T")
      )
      (libsource (lib "Database_Libs1") (part "D_STKY_DUAL_A1A2CC3"))
    )
    (comp (ref "D12")
      (value "D_STKY_DUAL_A1A2CC3")
      (footprint "SMD_SOT23_SOT95P240X120-3N")
      (fields
        (field (name "DB_PART_NUMBER") "DDE000000490")
        (field (name "DB_VALUE") "BAT54C")
        (field (name "DB_MANUFACTURER_PART") "Diodes        BAT54C")
        (field (name "DB_APPROVED_BY") "ISHIDDEN=T")
      )
      (libsource (lib "Database_Libs1") (part "D_STKY_DUAL_A1A2CC3"))
    )
    (comp (ref "D13")
      (value "D_STKY_DUAL_A1A2CC3")
      (footprint "SMD_SOT23_SOT95P240X120-3N")
      (fields
        (field (name "DB_PART_NUMBER") "DDE000000490")
        (field (name "DB_VALUE") "BAT54C")
        (field (name "DB_MANUFACTURER_PART") "Diodes        BAT54C")
        (field (name "DB_APPROVED_BY") "ISHIDDEN=T")
      )
      (libsource (lib "Database_Libs1") (part "D_STKY_DUAL_A1A2CC3"))
    )
    (comp (ref "D14")
      (value "D_STKY_DUAL_A1A2CC3")
      (footprint "SMD_SOT23_SOT95P240X120-3N")
      (fields
        (field (name "DB_PART_NUMBER") "DDE000000490")
        (field (name "DB_VALUE") "BAT54C")
        (field (name "DB_MANUFACTURER_PART") "Diodes        BAT54C")
        (field (name "DB_APPROVED_BY") "ISHIDDEN=T")
      )
      (libsource (lib "Database_Libs1") (part "D_STKY_DUAL_A1A2CC3"))
    )
    (comp (ref "D15")
      (value "D_STKY_DUAL_A1A2CC3")
      (footprint "SMD_SOT23_SOT95P240X120-3N")
      (fields
        (field (name "DB_PART_NUMBER") "DDE000000490")
        (field (name "DB_VALUE") "BAT54C")
        (field (name "DB_MANUFACTURER_PART") "Diodes        BAT54C")
        (field (name "DB_APPROVED_BY") "ISHIDDEN=T")
      )
      (libsource (lib "Database_Libs1") (part "D_STKY_DUAL_A1A2CC3"))
    )
    (comp (ref "D16")
      (value "D_STKY_DUAL_A1A2CC3")
      (footprint "SMD_SOT23_SOT95P240X120-3N")
      (fields
        (field (name "DB_PART_NUMBER") "DDE000000490")
        (field (name "DB_VALUE") "BAT54C")
        (field (name "DB_MANUFACTURER_PART") "Diodes        BAT54C")
        (field (name "DB_APPROVED_BY") "ISHIDDEN=T")
      )
      (libsource (lib "Database_Libs1") (part "D_STKY_DUAL_A1A2CC3"))
    )
    (comp (ref "D17")
      (value "D_STKY_DUAL_A1A2CC3")
      (footprint "SMD_SOT23_SOT95P240X120-3N")
      (fields
        (field (name "DB_PART_NUMBER") "DDE000000490")
        (field (name "DB_VALUE") "BAT54C")
        (field (name "DB_MANUFACTURER_PART") "Diodes        BAT54C")
        (field (name "DB_APPROVED_BY") "ISHIDDEN=T")
      )
      (libsource (lib "Database_Libs1") (part "D_STKY_DUAL_A1A2CC3"))
    )
    (comp (ref "D18")
      (value "D_STKY_DUAL_A1A2CC3")
      (footprint "SMD_SOT23_SOT95P240X120-3N")
      (fields
        (field (name "DB_PART_NUMBER") "DDE000000490")
        (field (name "DB_VALUE") "BAT54C")
        (field (name "DB_MANUFACTURER_PART") "Diodes        BAT54C")
        (field (name "DB_APPROVED_BY") "ISHIDDEN=T")
      )
      (libsource (lib "Database_Libs1") (part "D_STKY_DUAL_A1A2CC3"))
    )
    (comp (ref "D19")
      (value "D_STKY_DUAL_A1A2CC3")
      (footprint "SMD_SOT23_SOT95P240X120-3N")
      (fields
        (field (name "DB_PART_NUMBER") "DDE000000490")
        (field (name "DB_VALUE") "BAT54C")
        (field (name "DB_MANUFACTURER_PART") "Diodes        BAT54C")
        (field (name "DB_APPROVED_BY") "ISHIDDEN=T")
      )
      (libsource (lib "Database_Libs1") (part "D_STKY_DUAL_A1A2CC3"))
    )
    (comp (ref "D20")
      (value "D_STKY_DUAL_A1A2CC3")
      (footprint "SMD_SOT23_SOT95P240X120-3N")
      (fields
        (field (name "DB_PART_NUMBER") "DDE000000490")
        (field (name "DB_VALUE") "BAT54C")
        (field (name "DB_MANUFACTURER_PART") "Diodes        BAT54C")
        (field (name "DB_APPROVED_BY") "ISHIDDEN=T")
      )
      (libsource (lib "Database_Libs1") (part "D_STKY_DUAL_A1A2CC3"))
    )
    (comp (ref "D21")
      (value "D_STKY_DUAL_A1A2CC3")
      (footprint "SMD_SOT23_SOT95P240X120-3N")
      (fields
        (field (name "DB_PART_NUMBER") "DDE000000490")
        (field (name "DB_VALUE") "BAT54C")
        (field (name "DB_MANUFACTURER_PART") "Diodes        BAT54C")
        (field (name "DB_APPROVED_BY") "ISHIDDEN=T")
      )
      (libsource (lib "Database_Libs1") (part "D_STKY_DUAL_A1A2CC3"))
    )
    (comp (ref "D22")
      (value "D_STKY_DUAL_A1A2CC3")
      (footprint "SMD_SOT23_SOT95P240X120-3N")
      (fields
        (field (name "DB_PART_NUMBER") "DDE000000490")
        (field (name "DB_VALUE") "BAT54C")
        (field (name "DB_MANUFACTURER_PART") "Diodes        BAT54C")
        (field (name "DB_APPROVED_BY") "ISHIDDEN=T")
      )
      (libsource (lib "Database_Libs1") (part "D_STKY_DUAL_A1A2CC3"))
    )
    (comp (ref "D23")
      (value "D_STKY_DUAL_A1A2CC3")
      (footprint "SMD_SOT23_SOT95P240X120-3N")
      (fields
        (field (name "DB_PART_NUMBER") "DDE000000490")
        (field (name "DB_VALUE") "BAT54C")
        (field (name "DB_MANUFACTURER_PART") "Diodes        BAT54C")
        (field (name "DB_APPROVED_BY") "ISHIDDEN=T")
      )
      (libsource (lib "Database_Libs1") (part "D_STKY_DUAL_A1A2CC3"))
    )
    (comp (ref "D24")
      (value "D_STKY_DUAL_A1A2CC3")
      (footprint "SMD_SOT23_SOT95P240X120-3N")
      (fields
        (field (name "DB_PART_NUMBER") "DDE000000490")
        (field (name "DB_VALUE") "BAT54C")
        (field (name "DB_MANUFACTURER_PART") "Diodes        BAT54C")
        (field (name "DB_APPROVED_BY") "ISHIDDEN=T")
      )
      (libsource (lib "Database_Libs1") (part "D_STKY_DUAL_A1A2CC3"))
    )
    (comp (ref "D25")
      (value "D_STKY_DUAL_A1A2CC3")
      (footprint "SMD_SOT23_SOT95P240X120-3N")
      (fields
        (field (name "DB_PART_NUMBER") "DDE000000490")
        (field (name "DB_VALUE") "BAT54C")
        (field (name "DB_MANUFACTURER_PART") "Diodes        BAT54C")
        (field (name "DB_APPROVED_BY") "ISHIDDEN=T")
      )
      (libsource (lib "Database_Libs1") (part "D_STKY_DUAL_A1A2CC3"))
    )
    (comp (ref "L1")
      (value "SLC1480-201MLD")
      (footprint "SMT_INDM135130X800N")
      (libsource (lib "EPIQ_DND_CIS_Library") (part "L"))
    )
    (comp (ref "L2")
      (value "SLC1480-201MLD")
      (footprint "SMT_INDM135130X800N")
      (libsource (lib "EPIQ_DND_CIS_Library") (part "L"))
    )
    (comp (ref "L3")
      (value "SLC1480-201MLD")
      (footprint "SMT_INDM135130X800N")
      (libsource (lib "EPIQ_DND_CIS_Library") (part "L"))
    )
    (comp (ref "L4")
      (value "SLC1480-201MLD")
      (footprint "SMT_INDM135130X800N")
      (libsource (lib "EPIQ_DND_CIS_Library") (part "L"))
    )
    (comp (ref "L5")
      (value "SLC1480-201MLD")
      (footprint "SMT_INDM135130X800N")
      (libsource (lib "EPIQ_DND_CIS_Library") (part "L"))
    )
    (comp (ref "L6")
      (value "SLC1480-201MLD")
      (footprint "SMT_INDM135130X800N")
      (libsource (lib "EPIQ_DND_CIS_Library") (part "L"))
    )
    (comp (ref "L7")
      (value "SLC1480-201MLD")
      (footprint "SMT_INDM135130X800N")
      (libsource (lib "EPIQ_DND_CIS_Library") (part "L"))
    )
    (comp (ref "L8")
      (value "SLC1480-201MLD")
      (footprint "SMT_INDM135130X800N")
      (libsource (lib "EPIQ_DND_CIS_Library") (part "L"))
    )
    (comp (ref "L9")
      (value "SLC1480-201MLD")
      (footprint "SMT_INDM135130X800N")
      (libsource (lib "EPIQ_DND_CIS_Library") (part "L"))
    )
    (comp (ref "L10")
      (value "SLC1480-201MLD")
      (footprint "SMT_INDM135130X800N")
      (libsource (lib "EPIQ_DND_CIS_Library") (part "L"))
    )
    (comp (ref "L11")
      (value "SLC1480-201MLD")
      (footprint "SMT_INDM135130X800N")
      (libsource (lib "EPIQ_DND_CIS_Library") (part "L"))
    )
    (comp (ref "L12")
      (value "SLC1480-201MLD")
      (footprint "SMT_INDM135130X800N")
      (libsource (lib "EPIQ_DND_CIS_Library") (part "L"))
    )
    (comp (ref "L13")
      (value "SLC1480-201MLD")
      (footprint "SMT_INDM135130X800N")
      (libsource (lib "EPIQ_DND_CIS_Library") (part "L"))
    )
    (comp (ref "L14")
      (value "SLC1480-201MLD")
      (footprint "SMT_INDM135130X800N")
      (libsource (lib "EPIQ_DND_CIS_Library") (part "L"))
    )
    (comp (ref "L15")
      (value "SLC1480-201MLD")
      (footprint "SMT_INDM135130X800N")
      (libsource (lib "EPIQ_DND_CIS_Library") (part "L"))
    )
    (comp (ref "L16")
      (value "SLC1480-201MLD")
      (footprint "SMT_INDM135130X800N")
      (libsource (lib "EPIQ_DND_CIS_Library") (part "L"))
    )
    (comp (ref "Q1")
      (value "MOS_N_D1_S1S2S3G4D5D6D7D8")
      (footprint "SMD_SOIC127P600X110-9AN")
      (fields
        (field (name "DB_PART_NUMBER") "TRA000001604")
        (field (name "DB_VALUE") "AP1RA03GMT-HF-3")
        (field (name "DB_MANUFACTURER_PART") "ADVANCED POWER ELECTRONICS CORP      AP1RA03GMT-HF-3")
        (field (name "DB_APPROVED_BY") "VSN")
      )
      (libsource (lib "Database_Libs1") (part "MOS_N_D1_S1S2S3G4D5D6D7D8"))
    )
    (comp (ref "Q2")
      (value "MOS_N_D1_S1S2S3G4D5D6D7D8")
      (footprint "SMD_SOIC127P600X110-9AN")
      (fields
        (field (name "DB_PART_NUMBER") "TRA000001604")
        (field (name "DB_VALUE") "AP1RA03GMT-HF-3")
        (field (name "DB_MANUFACTURER_PART") "ADVANCED POWER ELECTRONICS CORP      AP1RA03GMT-HF-3")
        (field (name "DB_APPROVED_BY") "VSN")
      )
      (libsource (lib "Database_Libs1") (part "MOS_N_D1_S1S2S3G4D5D6D7D8"))
    )
    (comp (ref "Q3")
      (value "MOS_N_D1_S1S2S3G4D5D6D7D8")
      (footprint "SMD_SOIC127P600X110-9AN")
      (fields
        (field (name "DB_PART_NUMBER") "TRA000001604")
        (field (name "DB_VALUE") "AP1RA03GMT-HF-3")
        (field (name "DB_MANUFACTURER_PART") "ADVANCED POWER ELECTRONICS CORP      AP1RA03GMT-HF-3")
        (field (name "DB_APPROVED_BY") "VSN")
      )
      (libsource (lib "Database_Libs1") (part "MOS_N_D1_S1S2S3G4D5D6D7D8"))
    )
    (comp (ref "Q4")
      (value "MOS_N_D1_S1S2S3G4D5D6D7D8")
      (footprint "SMD_SOIC127P600X110-9AN")
      (fields
        (field (name "DB_PART_NUMBER") "TRA000001604")
        (field (name "DB_VALUE") "AP1RA03GMT-HF-3")
        (field (name "DB_MANUFACTURER_PART") "ADVANCED POWER ELECTRONICS CORP      AP1RA03GMT-HF-3")
        (field (name "DB_APPROVED_BY") "VSN")
      )
      (libsource (lib "Database_Libs1") (part "MOS_N_D1_S1S2S3G4D5D6D7D8"))
    )
    (comp (ref "Q5")
      (value "MOS_N_D1_S1S2S3G4D5D6D7D8")
      (footprint "SMD_SOIC127P600X110-9AN")
      (fields
        (field (name "DB_PART_NUMBER") "TRA000001604")
        (field (name "DB_VALUE") "AP1RA03GMT-HF-3")
        (field (name "DB_MANUFACTURER_PART") "ADVANCED POWER ELECTRONICS CORP      AP1RA03GMT-HF-3")
        (field (name "DB_APPROVED_BY") "VSN")
      )
      (libsource (lib "Database_Libs1") (part "MOS_N_D1_S1S2S3G4D5D6D7D8"))
    )
    (comp (ref "Q6")
      (value "MOS_N_D1_S1S2S3G4D5D6D7D8")
      (footprint "SMD_SOIC127P600X110-9AN")
      (fields
        (field (name "DB_PART_NUMBER") "TRA000001604")
        (field (name "DB_VALUE") "AP1RA03GMT-HF-3")
        (field (name "DB_MANUFACTURER_PART") "ADVANCED POWER ELECTRONICS CORP      AP1RA03GMT-HF-3")
        (field (name "DB_APPROVED_BY") "VSN")
      )
      (libsource (lib "Database_Libs1") (part "MOS_N_D1_S1S2S3G4D5D6D7D8"))
    )
    (comp (ref "Q7")
      (value "MOS_N_D1_S1S2S3G4D5D6D7D8")
      (footprint "SMD_SOIC127P600X110-9AN")
      (fields
        (field (name "DB_PART_NUMBER") "TRA000001604")
        (field (name "DB_VALUE") "AP1RA03GMT-HF-3")
        (field (name "DB_MANUFACTURER_PART") "ADVANCED POWER ELECTRONICS CORP      AP1RA03GMT-HF-3")
        (field (name "DB_APPROVED_BY") "VSN")
      )
      (libsource (lib "Database_Libs1") (part "MOS_N_D1_S1S2S3G4D5D6D7D8"))
    )
    (comp (ref "Q8")
      (value "MOS_N_D1_S1S2S3G4D5D6D7D8")
      (footprint "SMD_SOIC127P600X110-9AN")
      (fields
        (field (name "DB_PART_NUMBER") "TRA000001604")
        (field (name "DB_VALUE") "AP1RA03GMT-HF-3")
        (field (name "DB_MANUFACTURER_PART") "ADVANCED POWER ELECTRONICS CORP      AP1RA03GMT-HF-3")
        (field (name "DB_APPROVED_BY") "VSN")
      )
      (libsource (lib "Database_Libs1") (part "MOS_N_D1_S1S2S3G4D5D6D7D8"))
    )
    (comp (ref "Q9")
      (value "MOS_N_D1_S1S2S3G4D5D6D7D8")
      (footprint "SMD_SOIC127P600X110-9AN")
      (fields
        (field (name "DB_PART_NUMBER") "TRA000001604")
        (field (name "DB_VALUE") "AP1RA03GMT-HF-3")
        (field (name "DB_MANUFACTURER_PART") "ADVANCED POWER ELECTRONICS CORP      AP1RA03GMT-HF-3")
        (field (name "DB_APPROVED_BY") "VSN")
      )
      (libsource (lib "Database_Libs1") (part "MOS_N_D1_S1S2S3G4D5D6D7D8"))
    )
    (comp (ref "Q10")
      (value "MOS_N_D1_S1S2S3G4D5D6D7D8")
      (footprint "SMD_SOIC127P600X110-9AN")
      (fields
        (field (name "DB_PART_NUMBER") "TRA000001604")
        (field (name "DB_VALUE") "AP1RA03GMT-HF-3")
        (field (name "DB_MANUFACTURER_PART") "ADVANCED POWER ELECTRONICS CORP      AP1RA03GMT-HF-3")
        (field (name "DB_APPROVED_BY") "VSN")
      )
      (libsource (lib "Database_Libs1") (part "MOS_N_D1_S1S2S3G4D5D6D7D8"))
    )
    (comp (ref "Q11")
      (value "MOS_N_D1_S1S2S3G4D5D6D7D8")
      (footprint "SMD_SOIC127P600X110-9AN")
      (fields
        (field (name "DB_PART_NUMBER") "TRA000001604")
        (field (name "DB_VALUE") "AP1RA03GMT-HF-3")
        (field (name "DB_MANUFACTURER_PART") "ADVANCED POWER ELECTRONICS CORP      AP1RA03GMT-HF-3")
        (field (name "DB_APPROVED_BY") "VSN")
      )
      (libsource (lib "Database_Libs1") (part "MOS_N_D1_S1S2S3G4D5D6D7D8"))
    )
    (comp (ref "Q12")
      (value "MOS_N_D1_S1S2S3G4D5D6D7D8")
      (footprint "SMD_SOIC127P600X110-9AN")
      (fields
        (field (name "DB_PART_NUMBER") "TRA000001604")
        (field (name "DB_VALUE") "AP1RA03GMT-HF-3")
        (field (name "DB_MANUFACTURER_PART") "ADVANCED POWER ELECTRONICS CORP      AP1RA03GMT-HF-3")
        (field (name "DB_APPROVED_BY") "VSN")
      )
      (libsource (lib "Database_Libs1") (part "MOS_N_D1_S1S2S3G4D5D6D7D8"))
    )
    (comp (ref "Q13")
      (value "MOS_N_D1_S1S2S3G4D5D6D7D8")
      (footprint "SMD_SOIC127P600X110-9AN")
      (fields
        (field (name "DB_PART_NUMBER") "TRA000001604")
        (field (name "DB_VALUE") "AP1RA03GMT-HF-3")
        (field (name "DB_MANUFACTURER_PART") "ADVANCED POWER ELECTRONICS CORP      AP1RA03GMT-HF-3")
        (field (name "DB_APPROVED_BY") "VSN")
      )
      (libsource (lib "Database_Libs1") (part "MOS_N_D1_S1S2S3G4D5D6D7D8"))
    )
    (comp (ref "Q14")
      (value "MOS_N_D1_S1S2S3G4D5D6D7D8")
      (footprint "SMD_SOIC127P600X110-9AN")
      (fields
        (field (name "DB_PART_NUMBER") "TRA000001604")
        (field (name "DB_VALUE") "AP1RA03GMT-HF-3")
        (field (name "DB_MANUFACTURER_PART") "ADVANCED POWER ELECTRONICS CORP      AP1RA03GMT-HF-3")
        (field (name "DB_APPROVED_BY") "VSN")
      )
      (libsource (lib "Database_Libs1") (part "MOS_N_D1_S1S2S3G4D5D6D7D8"))
    )
    (comp (ref "Q15")
      (value "MOS_N_D1_S1S2S3G4D5D6D7D8")
      (footprint "SMD_SOIC127P600X110-9AN")
      (fields
        (field (name "DB_PART_NUMBER") "TRA000001604")
        (field (name "DB_VALUE") "AP1RA03GMT-HF-3")
        (field (name "DB_MANUFACTURER_PART") "ADVANCED POWER ELECTRONICS CORP      AP1RA03GMT-HF-3")
        (field (name "DB_APPROVED_BY") "VSN")
      )
      (libsource (lib "Database_Libs1") (part "MOS_N_D1_S1S2S3G4D5D6D7D8"))
    )
    (comp (ref "Q16")
      (value "MOS_N_D1_S1S2S3G4D5D6D7D8")
      (footprint "SMD_SOIC127P600X110-9AN")
      (fields
        (field (name "DB_PART_NUMBER") "TRA000001604")
        (field (name "DB_VALUE") "AP1RA03GMT-HF-3")
        (field (name "DB_MANUFACTURER_PART") "ADVANCED POWER ELECTRONICS CORP      AP1RA03GMT-HF-3")
        (field (name "DB_APPROVED_BY") "VSN")
      )
      (libsource (lib "Database_Libs1") (part "MOS_N_D1_S1S2S3G4D5D6D7D8"))
    )
    (comp (ref "Q17")
      (value "MOS_N_D1_S1S2S3G4D5D6D7D8")
      (footprint "SMD_SOIC127P600X110-9AN")
      (fields
        (field (name "DB_PART_NUMBER") "TRA000001604")
        (field (name "DB_VALUE") "AP1RA03GMT-HF-3")
        (field (name "DB_MANUFACTURER_PART") "ADVANCED POWER ELECTRONICS CORP      AP1RA03GMT-HF-3")
        (field (name "DB_APPROVED_BY") "VSN")
      )
      (libsource (lib "Database_Libs1") (part "MOS_N_D1_S1S2S3G4D5D6D7D8"))
    )
    (comp (ref "Q18")
      (value "MOS_N_D1_S1S2S3G4D5D6D7D8")
      (footprint "SMD_SOIC127P600X110-9AN")
      (fields
        (field (name "DB_PART_NUMBER") "TRA000001604")
        (field (name "DB_VALUE") "AP1RA03GMT-HF-3")
        (field (name "DB_MANUFACTURER_PART") "ADVANCED POWER ELECTRONICS CORP      AP1RA03GMT-HF-3")
        (field (name "DB_APPROVED_BY") "VSN")
      )
      (libsource (lib "Database_Libs1") (part "MOS_N_D1_S1S2S3G4D5D6D7D8"))
    )
    (comp (ref "Q19")
      (value "MOS_N_D1_S1S2S3G4D5D6D7D8")
      (footprint "SMD_SOIC127P600X110-9AN")
      (fields
        (field (name "DB_PART_NUMBER") "TRA000001604")
        (field (name "DB_VALUE") "AP1RA03GMT-HF-3")
        (field (name "DB_MANUFACTURER_PART") "ADVANCED POWER ELECTRONICS CORP      AP1RA03GMT-HF-3")
        (field (name "DB_APPROVED_BY") "VSN")
      )
      (libsource (lib "Database_Libs1") (part "MOS_N_D1_S1S2S3G4D5D6D7D8"))
    )
    (comp (ref "Q20")
      (value "MOS_N_D1_S1S2S3G4D5D6D7D8")
      (footprint "SMD_SOIC127P600X110-9AN")
      (fields
        (field (name "DB_PART_NUMBER") "TRA000001604")
        (field (name "DB_VALUE") "AP1RA03GMT-HF-3")
        (field (name "DB_MANUFACTURER_PART") "ADVANCED POWER ELECTRONICS CORP      AP1RA03GMT-HF-3")
        (field (name "DB_APPROVED_BY") "VSN")
      )
      (libsource (lib "Database_Libs1") (part "MOS_N_D1_S1S2S3G4D5D6D7D8"))
    )
    (comp (ref "Q21")
      (value "MOS_N_D1_S1S2S3G4D5D6D7D8")
      (footprint "SMD_SOIC127P600X110-9AN")
      (fields
        (field (name "DB_PART_NUMBER") "TRA000001604")
        (field (name "DB_VALUE") "AP1RA03GMT-HF-3")
        (field (name "DB_MANUFACTURER_PART") "ADVANCED POWER ELECTRONICS CORP      AP1RA03GMT-HF-3")
        (field (name "DB_APPROVED_BY") "VSN")
      )
      (libsource (lib "Database_Libs1") (part "MOS_N_D1_S1S2S3G4D5D6D7D8"))
    )
    (comp (ref "Q22")
      (value "MOS_N_D1_S1S2S3G4D5D6D7D8")
      (footprint "SMD_SOIC127P600X110-9AN")
      (fields
        (field (name "DB_PART_NUMBER") "TRA000001604")
        (field (name "DB_VALUE") "AP1RA03GMT-HF-3")
        (field (name "DB_MANUFACTURER_PART") "ADVANCED POWER ELECTRONICS CORP      AP1RA03GMT-HF-3")
        (field (name "DB_APPROVED_BY") "VSN")
      )
      (libsource (lib "Database_Libs1") (part "MOS_N_D1_S1S2S3G4D5D6D7D8"))
    )
    (comp (ref "Q23")
      (value "MOS_N_D1_S1S2S3G4D5D6D7D8")
      (footprint "SMD_SOIC127P600X110-9AN")
      (fields
        (field (name "DB_PART_NUMBER") "TRA000001604")
        (field (name "DB_VALUE") "AP1RA03GMT-HF-3")
        (field (name "DB_MANUFACTURER_PART") "ADVANCED POWER ELECTRONICS CORP      AP1RA03GMT-HF-3")
        (field (name "DB_APPROVED_BY") "VSN")
      )
      (libsource (lib "Database_Libs1") (part "MOS_N_D1_S1S2S3G4D5D6D7D8"))
    )
    (comp (ref "Q24")
      (value "MOS_N_D1_S1S2S3G4D5D6D7D8")
      (footprint "SMD_SOIC127P600X110-9AN")
      (fields
        (field (name "DB_PART_NUMBER") "TRA000001604")
        (field (name "DB_VALUE") "AP1RA03GMT-HF-3")
        (field (name "DB_MANUFACTURER_PART") "ADVANCED POWER ELECTRONICS CORP      AP1RA03GMT-HF-3")
        (field (name "DB_APPROVED_BY") "VSN")
      )
      (libsource (lib "Database_Libs1") (part "MOS_N_D1_S1S2S3G4D5D6D7D8"))
    )
    (comp (ref "Q25")
      (value "MOS_N_D1_S1S2S3G4D5D6D7D8")
      (footprint "SMD_SOIC127P600X110-9AN")
      (fields
        (field (name "DB_PART_NUMBER") "TRA000001604")
        (field (name "DB_VALUE") "AP1RA03GMT-HF-3")
        (field (name "DB_MANUFACTURER_PART") "ADVANCED POWER ELECTRONICS CORP      AP1RA03GMT-HF-3")
        (field (name "DB_APPROVED_BY") "VSN")
      )
      (libsource (lib "Database_Libs1") (part "MOS_N_D1_S1S2S3G4D5D6D7D8"))
    )
    (comp (ref "Q26")
      (value "MOS_N_D1_S1S2S3G4D5D6D7D8")
      (footprint "SMD_SOIC127P600X110-9AN")
      (fields
        (field (name "DB_PART_NUMBER") "TRA000001604")
        (field (name "DB_VALUE") "AP1RA03GMT-HF-3")
        (field (name "DB_MANUFACTURER_PART") "ADVANCED POWER ELECTRONICS CORP      AP1RA03GMT-HF-3")
        (field (name "DB_APPROVED_BY") "VSN")
      )
      (libsource (lib "Database_Libs1") (part "MOS_N_D1_S1S2S3G4D5D6D7D8"))
    )
    (comp (ref "Q27")
      (value "MOS_N_D1_S1S2S3G4D5D6D7D8")
      (footprint "SMD_SOIC127P600X110-9AN")
      (fields
        (field (name "DB_PART_NUMBER") "TRA000001604")
        (field (name "DB_VALUE") "AP1RA03GMT-HF-3")
        (field (name "DB_MANUFACTURER_PART") "ADVANCED POWER ELECTRONICS CORP      AP1RA03GMT-HF-3")
        (field (name "DB_APPROVED_BY") "VSN")
      )
      (libsource (lib "Database_Libs1") (part "MOS_N_D1_S1S2S3G4D5D6D7D8"))
    )
    (comp (ref "Q28")
      (value "MOS_N_D1_S1S2S3G4D5D6D7D8")
      (footprint "SMD_SOIC127P600X110-9AN")
      (fields
        (field (name "DB_PART_NUMBER") "TRA000001604")
        (field (name "DB_VALUE") "AP1RA03GMT-HF-3")
        (field (name "DB_MANUFACTURER_PART") "ADVANCED POWER ELECTRONICS CORP      AP1RA03GMT-HF-3")
        (field (name "DB_APPROVED_BY") "VSN")
      )
      (libsource (lib "Database_Libs1") (part "MOS_N_D1_S1S2S3G4D5D6D7D8"))
    )
    (comp (ref "Q29")
      (value "MOS_N_D1_S1S2S3G4D5D6D7D8")
      (footprint "SMD_SOIC127P600X110-9AN")
      (fields
        (field (name "DB_PART_NUMBER") "TRA000001604")
        (field (name "DB_VALUE") "AP1RA03GMT-HF-3")
        (field (name "DB_MANUFACTURER_PART") "ADVANCED POWER ELECTRONICS CORP      AP1RA03GMT-HF-3")
        (field (name "DB_APPROVED_BY") "VSN")
      )
      (libsource (lib "Database_Libs1") (part "MOS_N_D1_S1S2S3G4D5D6D7D8"))
    )
    (comp (ref "Q30")
      (value "MOS_N_D1_S1S2S3G4D5D6D7D8")
      (footprint "SMD_SOIC127P600X110-9AN")
      (fields
        (field (name "DB_PART_NUMBER") "TRA000001604")
        (field (name "DB_VALUE") "AP1RA03GMT-HF-3")
        (field (name "DB_MANUFACTURER_PART") "ADVANCED POWER ELECTRONICS CORP      AP1RA03GMT-HF-3")
        (field (name "DB_APPROVED_BY") "VSN")
      )
      (libsource (lib "Database_Libs1") (part "MOS_N_D1_S1S2S3G4D5D6D7D8"))
    )
    (comp (ref "Q31")
      (value "MOS_N_D1_S1S2S3G4D5D6D7D8")
      (footprint "SMD_SOIC127P600X110-9AN")
      (fields
        (field (name "DB_PART_NUMBER") "TRA000001604")
        (field (name "DB_VALUE") "AP1RA03GMT-HF-3")
        (field (name "DB_MANUFACTURER_PART") "ADVANCED POWER ELECTRONICS CORP      AP1RA03GMT-HF-3")
        (field (name "DB_APPROVED_BY") "VSN")
      )
      (libsource (lib "Database_Libs1") (part "MOS_N_D1_S1S2S3G4D5D6D7D8"))
    )
    (comp (ref "Q32")
      (value "MOS_N_D1_S1S2S3G4D5D6D7D8")
      (footprint "SMD_SOIC127P600X110-9AN")
      (fields
        (field (name "DB_PART_NUMBER") "TRA000001604")
        (field (name "DB_VALUE") "AP1RA03GMT-HF-3")
        (field (name "DB_MANUFACTURER_PART") "ADVANCED POWER ELECTRONICS CORP      AP1RA03GMT-HF-3")
        (field (name "DB_APPROVED_BY") "VSN")
      )
      (libsource (lib "Database_Libs1") (part "MOS_N_D1_S1S2S3G4D5D6D7D8"))
    )
    (comp (ref "Q33")
      (value "MOS_N_D1_S1S2S3G4D5D6D7D8")
      (footprint "SMD_SOIC127P600X110-9AN")
      (fields
        (field (name "DB_PART_NUMBER") "TRA000001604")
        (field (name "DB_VALUE") "AP1RA03GMT-HF-3")
        (field (name "DB_MANUFACTURER_PART") "ADVANCED POWER ELECTRONICS CORP      AP1RA03GMT-HF-3")
        (field (name "DB_APPROVED_BY") "VSN")
      )
      (libsource (lib "Database_Libs1") (part "MOS_N_D1_S1S2S3G4D5D6D7D8"))
    )
    (comp (ref "Q34")
      (value "MOS_N_D1_S1S2S3G4D5D6D7D8")
      (footprint "SMD_SOIC127P600X110-9AN")
      (fields
        (field (name "DB_PART_NUMBER") "TRA000001604")
        (field (name "DB_VALUE") "AP1RA03GMT-HF-3")
        (field (name "DB_MANUFACTURER_PART") "ADVANCED POWER ELECTRONICS CORP      AP1RA03GMT-HF-3")
        (field (name "DB_APPROVED_BY") "VSN")
      )
      (libsource (lib "Database_Libs1") (part "MOS_N_D1_S1S2S3G4D5D6D7D8"))
    )
    (comp (ref "Q35")
      (value "MOS_N_D1_S1S2S3G4D5D6D7D8")
      (footprint "SMD_SOIC127P600X110-9AN")
      (fields
        (field (name "DB_PART_NUMBER") "TRA000001604")
        (field (name "DB_VALUE") "AP1RA03GMT-HF-3")
        (field (name "DB_MANUFACTURER_PART") "ADVANCED POWER ELECTRONICS CORP      AP1RA03GMT-HF-3")
        (field (name "DB_APPROVED_BY") "VSN")
      )
      (libsource (lib "Database_Libs1") (part "MOS_N_D1_S1S2S3G4D5D6D7D8"))
    )
    (comp (ref "Q36")
      (value "MOS_N_D1_S1S2S3G4D5D6D7D8")
      (footprint "SMD_SOIC127P600X110-9AN")
      (fields
        (field (name "DB_PART_NUMBER") "TRA000001604")
        (field (name "DB_VALUE") "AP1RA03GMT-HF-3")
        (field (name "DB_MANUFACTURER_PART") "ADVANCED POWER ELECTRONICS CORP      AP1RA03GMT-HF-3")
        (field (name "DB_APPROVED_BY") "VSN")
      )
      (libsource (lib "Database_Libs1") (part "MOS_N_D1_S1S2S3G4D5D6D7D8"))
    )
    (comp (ref "Q37")
      (value "MOS_N_D1_S1S2S3G4D5D6D7D8")
      (footprint "SMD_SOIC127P600X110-9AN")
      (fields
        (field (name "DB_PART_NUMBER") "TRA000001604")
        (field (name "DB_VALUE") "AP1RA03GMT-HF-3")
        (field (name "DB_MANUFACTURER_PART") "ADVANCED POWER ELECTRONICS CORP      AP1RA03GMT-HF-3")
        (field (name "DB_APPROVED_BY") "VSN")
      )
      (libsource (lib "Database_Libs1") (part "MOS_N_D1_S1S2S3G4D5D6D7D8"))
    )
    (comp (ref "Q38")
      (value "MOS_N_D1_S1S2S3G4D5D6D7D8")
      (footprint "SMD_SOIC127P600X110-9AN")
      (fields
        (field (name "DB_PART_NUMBER") "TRA000001604")
        (field (name "DB_VALUE") "AP1RA03GMT-HF-3")
        (field (name "DB_MANUFACTURER_PART") "ADVANCED POWER ELECTRONICS CORP      AP1RA03GMT-HF-3")
        (field (name "DB_APPROVED_BY") "VSN")
      )
      (libsource (lib "Database_Libs1") (part "MOS_N_D1_S1S2S3G4D5D6D7D8"))
    )
    (comp (ref "Q39")
      (value "MOS_N_D1_S1S2S3G4D5D6D7D8")
      (footprint "SMD_SOIC127P600X110-9AN")
      (fields
        (field (name "DB_PART_NUMBER") "TRA000001604")
        (field (name "DB_VALUE") "AP1RA03GMT-HF-3")
        (field (name "DB_MANUFACTURER_PART") "ADVANCED POWER ELECTRONICS CORP      AP1RA03GMT-HF-3")
        (field (name "DB_APPROVED_BY") "VSN")
      )
      (libsource (lib "Database_Libs1") (part "MOS_N_D1_S1S2S3G4D5D6D7D8"))
    )
    (comp (ref "Q40")
      (value "MOS_N_D1_S1S2S3G4D5D6D7D8")
      (footprint "SMD_SOIC127P600X110-9AN")
      (fields
        (field (name "DB_PART_NUMBER") "TRA000001604")
        (field (name "DB_VALUE") "AP1RA03GMT-HF-3")
        (field (name "DB_MANUFACTURER_PART") "ADVANCED POWER ELECTRONICS CORP      AP1RA03GMT-HF-3")
        (field (name "DB_APPROVED_BY") "VSN")
      )
      (libsource (lib "Database_Libs1") (part "MOS_N_D1_S1S2S3G4D5D6D7D8"))
    )
    (comp (ref "Q41")
      (value "MOS_N_D1_S1S2S3G4D5D6D7D8")
      (footprint "SMD_SOIC127P600X110-9AN")
      (fields
        (field (name "DB_PART_NUMBER") "TRA000001604")
        (field (name "DB_VALUE") "AP1RA03GMT-HF-3")
        (field (name "DB_MANUFACTURER_PART") "ADVANCED POWER ELECTRONICS CORP      AP1RA03GMT-HF-3")
        (field (name "DB_APPROVED_BY") "VSN")
      )
      (libsource (lib "Database_Libs1") (part "MOS_N_D1_S1S2S3G4D5D6D7D8"))
    )
    (comp (ref "Q42")
      (value "MOS_N_D1_S1S2S3G4D5D6D7D8")
      (footprint "SMD_SOIC127P600X110-9AN")
      (fields
        (field (name "DB_PART_NUMBER") "TRA000001604")
        (field (name "DB_VALUE") "AP1RA03GMT-HF-3")
        (field (name "DB_MANUFACTURER_PART") "ADVANCED POWER ELECTRONICS CORP      AP1RA03GMT-HF-3")
        (field (name "DB_APPROVED_BY") "VSN")
      )
      (libsource (lib "Database_Libs1") (part "MOS_N_D1_S1S2S3G4D5D6D7D8"))
    )
    (comp (ref "Q43")
      (value "MOS_N_D1_S1S2S3G4D5D6D7D8")
      (footprint "SMD_SOIC127P600X110-9AN")
      (fields
        (field (name "DB_PART_NUMBER") "TRA000001604")
        (field (name "DB_VALUE") "AP1RA03GMT-HF-3")
        (field (name "DB_MANUFACTURER_PART") "ADVANCED POWER ELECTRONICS CORP      AP1RA03GMT-HF-3")
        (field (name "DB_APPROVED_BY") "VSN")
      )
      (libsource (lib "Database_Libs1") (part "MOS_N_D1_S1S2S3G4D5D6D7D8"))
    )
    (comp (ref "Q44")
      (value "MOS_N_D1_S1S2S3G4D5D6D7D8")
      (footprint "SMD_SOIC127P600X110-9AN")
      (fields
        (field (name "DB_PART_NUMBER") "TRA000001604")
        (field (name "DB_VALUE") "AP1RA03GMT-HF-3")
        (field (name "DB_MANUFACTURER_PART") "ADVANCED POWER ELECTRONICS CORP      AP1RA03GMT-HF-3")
        (field (name "DB_APPROVED_BY") "VSN")
      )
      (libsource (lib "Database_Libs1") (part "MOS_N_D1_S1S2S3G4D5D6D7D8"))
    )
    (comp (ref "Q45")
      (value "MOS_N_D1_S1S2S3G4D5D6D7D8")
      (footprint "SMD_SOIC127P600X110-9AN")
      (fields
        (field (name "DB_PART_NUMBER") "TRA000001604")
        (field (name "DB_VALUE") "AP1RA03GMT-HF-3")
        (field (name "DB_MANUFACTURER_PART") "ADVANCED POWER ELECTRONICS CORP      AP1RA03GMT-HF-3")
        (field (name "DB_APPROVED_BY") "VSN")
      )
      (libsource (lib "Database_Libs1") (part "MOS_N_D1_S1S2S3G4D5D6D7D8"))
    )
    (comp (ref "Q46")
      (value "MOS_N_D1_S1S2S3G4D5D6D7D8")
      (footprint "SMD_SOIC127P600X110-9AN")
      (fields
        (field (name "DB_PART_NUMBER") "TRA000001604")
        (field (name "DB_VALUE") "AP1RA03GMT-HF-3")
        (field (name "DB_MANUFACTURER_PART") "ADVANCED POWER ELECTRONICS CORP      AP1RA03GMT-HF-3")
        (field (name "DB_APPROVED_BY") "VSN")
      )
      (libsource (lib "Database_Libs1") (part "MOS_N_D1_S1S2S3G4D5D6D7D8"))
    )
    (comp (ref "Q47")
      (value "MOS_N_D1_S1S2S3G4D5D6D7D8")
      (footprint "SMD_SOIC127P600X110-9AN")
      (fields
        (field (name "DB_PART_NUMBER") "TRA000001604")
        (field (name "DB_VALUE") "AP1RA03GMT-HF-3")
        (field (name "DB_MANUFACTURER_PART") "ADVANCED POWER ELECTRONICS CORP      AP1RA03GMT-HF-3")
        (field (name "DB_APPROVED_BY") "VSN")
      )
      (libsource (lib "Database_Libs1") (part "MOS_N_D1_S1S2S3G4D5D6D7D8"))
    )
    (comp (ref "Q48")
      (value "MOS_N_D1_S1S2S3G4D5D6D7D8")
      (footprint "SMD_SOIC127P600X110-9AN")
      (fields
        (field (name "DB_PART_NUMBER") "TRA000001604")
        (field (name "DB_VALUE") "AP1RA03GMT-HF-3")
        (field (name "DB_MANUFACTURER_PART") "ADVANCED POWER ELECTRONICS CORP      AP1RA03GMT-HF-3")
        (field (name "DB_APPROVED_BY") "VSN")
      )
      (libsource (lib "Database_Libs1") (part "MOS_N_D1_S1S2S3G4D5D6D7D8"))
    )
    (comp (ref "U11")
      (value "IC_LTC4449")
      (footprint "SMD_SON45P300X200X80-9N")
      (fields
        (field (name "DB_PART_NUMBER") "DRV000000079")
        (field (name "DB_VALUE") "LTC4449EDCB#TRPBF")
        (field (name "DB_MANUFACTURER_PART") "LINEAR       LTC4449EDCB#TRPBF")
        (field (name "DB_APPROVED_BY") "VSN")
      )
      (libsource (lib "Database_Libs1") (part "IC_LTC4449"))
    )
    (comp (ref "U12")
      (value "IC_LTC4449")
      (footprint "SMD_SON45P300X200X80-9N")
      (fields
        (field (name "DB_PART_NUMBER") "DRV000000079")
        (field (name "DB_VALUE") "LTC4449EDCB#TRPBF")
        (field (name "DB_MANUFACTURER_PART") "LINEAR       LTC4449EDCB#TRPBF")
        (field (name "DB_APPROVED_BY") "VSN")
      )
      (libsource (lib "Database_Libs1") (part "IC_LTC4449"))
    )
    (comp (ref "U13")
      (value "IC_LTC4449")
      (footprint "SMD_SON45P300X200X80-9N")
      (fields
        (field (name "DB_PART_NUMBER") "DRV000000079")
        (field (name "DB_VALUE") "LTC4449EDCB#TRPBF")
        (field (name "DB_MANUFACTURER_PART") "LINEAR       LTC4449EDCB#TRPBF")
        (field (name "DB_APPROVED_BY") "VSN")
      )
      (libsource (lib "Database_Libs1") (part "IC_LTC4449"))
    )
    (comp (ref "U14")
      (value "IC_LTC4449")
      (footprint "SMD_SON45P300X200X80-9N")
      (fields
        (field (name "DB_PART_NUMBER") "DRV000000079")
        (field (name "DB_VALUE") "LTC4449EDCB#TRPBF")
        (field (name "DB_MANUFACTURER_PART") "LINEAR       LTC4449EDCB#TRPBF")
        (field (name "DB_APPROVED_BY") "VSN")
      )
      (libsource (lib "Database_Libs1") (part "IC_LTC4449"))
    )
    (comp (ref "U15")
      (value "IC_LTC4449")
      (footprint "SMD_SON45P300X200X80-9N")
      (fields
        (field (name "DB_PART_NUMBER") "DRV000000079")
        (field (name "DB_VALUE") "LTC4449EDCB#TRPBF")
        (field (name "DB_MANUFACTURER_PART") "LINEAR       LTC4449EDCB#TRPBF")
        (field (name "DB_APPROVED_BY") "VSN")
      )
      (libsource (lib "Database_Libs1") (part "IC_LTC4449"))
    )
    (comp (ref "U16")
      (value "IC_LTC4449")
      (footprint "SMD_SON45P300X200X80-9N")
      (fields
        (field (name "DB_PART_NUMBER") "DRV000000079")
        (field (name "DB_VALUE") "LTC4449EDCB#TRPBF")
        (field (name "DB_MANUFACTURER_PART") "LINEAR       LTC4449EDCB#TRPBF")
        (field (name "DB_APPROVED_BY") "VSN")
      )
      (libsource (lib "Database_Libs1") (part "IC_LTC4449"))
    )
    (comp (ref "U17")
      (value "IC_LTC4449")
      (footprint "SMD_SON45P300X200X80-9N")
      (fields
        (field (name "DB_PART_NUMBER") "DRV000000079")
        (field (name "DB_VALUE") "LTC4449EDCB#TRPBF")
        (field (name "DB_MANUFACTURER_PART") "LINEAR       LTC4449EDCB#TRPBF")
        (field (name "DB_APPROVED_BY") "VSN")
      )
      (libsource (lib "Database_Libs1") (part "IC_LTC4449"))
    )
    (comp (ref "U18")
      (value "IC_LTC4449")
      (footprint "SMD_SON45P300X200X80-9N")
      (fields
        (field (name "DB_PART_NUMBER") "DRV000000079")
        (field (name "DB_VALUE") "LTC4449EDCB#TRPBF")
        (field (name "DB_MANUFACTURER_PART") "LINEAR       LTC4449EDCB#TRPBF")
        (field (name "DB_APPROVED_BY") "VSN")
      )
      (libsource (lib "Database_Libs1") (part "IC_LTC4449"))
    )
    (comp (ref "U19")
      (value "IC_LTC4449")
      (footprint "SMD_SON45P300X200X80-9N")
      (fields
        (field (name "DB_PART_NUMBER") "DRV000000079")
        (field (name "DB_VALUE") "LTC4449EDCB#TRPBF")
        (field (name "DB_MANUFACTURER_PART") "LINEAR       LTC4449EDCB#TRPBF")
        (field (name "DB_APPROVED_BY") "VSN")
      )
      (libsource (lib "Database_Libs1") (part "IC_LTC4449"))
    )
    (comp (ref "U20")
      (value "IC_LTC4449")
      (footprint "SMD_SON45P300X200X80-9N")
      (fields
        (field (name "DB_PART_NUMBER") "DRV000000079")
        (field (name "DB_VALUE") "LTC4449EDCB#TRPBF")
        (field (name "DB_MANUFACTURER_PART") "LINEAR       LTC4449EDCB#TRPBF")
        (field (name "DB_APPROVED_BY") "VSN")
      )
      (libsource (lib "Database_Libs1") (part "IC_LTC4449"))
    )
    (comp (ref "U21")
      (value "IC_LTC4449")
      (footprint "SMD_SON45P300X200X80-9N")
      (fields
        (field (name "DB_PART_NUMBER") "DRV000000079")
        (field (name "DB_VALUE") "LTC4449EDCB#TRPBF")
        (field (name "DB_MANUFACTURER_PART") "LINEAR       LTC4449EDCB#TRPBF")
        (field (name "DB_APPROVED_BY") "VSN")
      )
      (libsource (lib "Database_Libs1") (part "IC_LTC4449"))
    )
    (comp (ref "U22")
      (value "IC_LTC4449")
      (footprint "SMD_SON45P300X200X80-9N")
      (fields
        (field (name "DB_PART_NUMBER") "DRV000000079")
        (field (name "DB_VALUE") "LTC4449EDCB#TRPBF")
        (field (name "DB_MANUFACTURER_PART") "LINEAR       LTC4449EDCB#TRPBF")
        (field (name "DB_APPROVED_BY") "VSN")
      )
      (libsource (lib "Database_Libs1") (part "IC_LTC4449"))
    )
    (comp (ref "U23")
      (value "IC_LTC4449")
      (footprint "SMD_SON45P300X200X80-9N")
      (fields
        (field (name "DB_PART_NUMBER") "DRV000000079")
        (field (name "DB_VALUE") "LTC4449EDCB#TRPBF")
        (field (name "DB_MANUFACTURER_PART") "LINEAR       LTC4449EDCB#TRPBF")
        (field (name "DB_APPROVED_BY") "VSN")
      )
      (libsource (lib "Database_Libs1") (part "IC_LTC4449"))
    )
    (comp (ref "U24")
      (value "IC_LTC4449")
      (footprint "SMD_SON45P300X200X80-9N")
      (fields
        (field (name "DB_PART_NUMBER") "DRV000000079")
        (field (name "DB_VALUE") "LTC4449EDCB#TRPBF")
        (field (name "DB_MANUFACTURER_PART") "LINEAR       LTC4449EDCB#TRPBF")
        (field (name "DB_APPROVED_BY") "VSN")
      )
      (libsource (lib "Database_Libs1") (part "IC_LTC4449"))
    )
    (comp (ref "U25")
      (value "IC_LTC4449")
      (footprint "SMD_SON45P300X200X80-9N")
      (fields
        (field (name "DB_PART_NUMBER") "DRV000000079")
        (field (name "DB_VALUE") "LTC4449EDCB#TRPBF")
        (field (name "DB_MANUFACTURER_PART") "LINEAR       LTC4449EDCB#TRPBF")
        (field (name "DB_APPROVED_BY") "VSN")
      )
      (libsource (lib "Database_Libs1") (part "IC_LTC4449"))
    )
    (comp (ref "U26")
      (value "IC_LTC4449")
      (footprint "SMD_SON45P300X200X80-9N")
      (fields
        (field (name "DB_PART_NUMBER") "DRV000000079")
        (field (name "DB_VALUE") "LTC4449EDCB#TRPBF")
        (field (name "DB_MANUFACTURER_PART") "LINEAR       LTC4449EDCB#TRPBF")
        (field (name "DB_APPROVED_BY") "VSN")
      )
      (libsource (lib "Database_Libs1") (part "IC_LTC4449"))
    )
  )
  (nets
    (net (code "1") (name "/1V") (class "Default")
      (node (ref "C100") (pin "2") (pinfunction "2_2") (pintype "passive"))
      (node (ref "C103") (pin "2") (pinfunction "2_2") (pintype "passive"))
      (node (ref "C104") (pin "2") (pinfunction "2_2") (pintype "passive"))
      (node (ref "C105") (pin "2") (pinfunction "2_2") (pintype "passive"))
      (node (ref "C108") (pin "2") (pinfunction "2_2") (pintype "passive"))
      (node (ref "C109") (pin "2") (pinfunction "2_2") (pintype "passive"))
      (node (ref "C110") (pin "2") (pinfunction "2_2") (pintype "passive"))
      (node (ref "C113") (pin "2") (pinfunction "2_2") (pintype "passive"))
      (node (ref "C114") (pin "2") (pinfunction "2_2") (pintype "passive"))
      (node (ref "C115") (pin "2") (pinfunction "2_2") (pintype "passive"))
      (node (ref "C130") (pin "2") (pinfunction "2_2") (pintype "passive"))
      (node (ref "C131") (pin "2") (pinfunction "2_2") (pintype "passive"))
      (node (ref "C132") (pin "2") (pinfunction "2_2") (pintype "passive"))
      (node (ref "C135") (pin "2") (pinfunction "2_2") (pintype "passive"))
      (node (ref "C136") (pin "2") (pinfunction "2_2") (pintype "passive"))
      (node (ref "C137") (pin "2") (pinfunction "2_2") (pintype "passive"))
      (node (ref "C140") (pin "2") (pinfunction "2_2") (pintype "passive"))
      (node (ref "C141") (pin "2") (pinfunction "2_2") (pintype "passive"))
      (node (ref "C142") (pin "2") (pinfunction "2_2") (pintype "passive"))
      (node (ref "C145") (pin "2") (pinfunction "2_2") (pintype "passive"))
      (node (ref "C146") (pin "2") (pinfunction "2_2") (pintype "passive"))
      (node (ref "C147") (pin "2") (pinfunction "2_2") (pintype "passive"))
      (node (ref "C34") (pin "2") (pinfunction "2_2") (pintype "passive"))
      (node (ref "C35") (pin "2") (pinfunction "2_2") (pintype "passive"))
      (node (ref "C36") (pin "2") (pinfunction "2_2") (pintype "passive"))
      (node (ref "C39") (pin "2") (pinfunction "2_2") (pintype "passive"))
      (node (ref "C40") (pin "2") (pinfunction "2_2") (pintype "passive"))
      (node (ref "C41") (pin "2") (pinfunction "2_2") (pintype "passive"))
      (node (ref "C44") (pin "2") (pinfunction "2_2") (pintype "passive"))
      (node (ref "C45") (pin "2") (pinfunction "2_2") (pintype "passive"))
      (node (ref "C46") (pin "2") (pinfunction "2_2") (pintype "passive"))
      (node (ref "C49") (pin "2") (pinfunction "2_2") (pintype "passive"))
      (node (ref "C50") (pin "2") (pinfunction "2_2") (pintype "passive"))
      (node (ref "C51") (pin "2") (pinfunction "2_2") (pintype "passive"))
      (node (ref "C66") (pin "2") (pinfunction "2_2") (pintype "passive"))
      (node (ref "C67") (pin "2") (pinfunction "2_2") (pintype "passive"))
      (node (ref "C68") (pin "2") (pinfunction "2_2") (pintype "passive"))
      (node (ref "C71") (pin "2") (pinfunction "2_2") (pintype "passive"))
      (node (ref "C72") (pin "2") (pinfunction "2_2") (pintype "passive"))
      (node (ref "C73") (pin "2") (pinfunction "2_2") (pintype "passive"))
      (node (ref "C76") (pin "2") (pinfunction "2_2") (pintype "passive"))
      (node (ref "C77") (pin "2") (pinfunction "2_2") (pintype "passive"))
      (node (ref "C78") (pin "2") (pinfunction "2_2") (pintype "passive"))
      (node (ref "C81") (pin "2") (pinfunction "2_2") (pintype "passive"))
      (node (ref "C82") (pin "2") (pinfunction "2_2") (pintype "passive"))
      (node (ref "C83") (pin "2") (pinfunction "2_2") (pintype "passive"))
      (node (ref "C98") (pin "2") (pinfunction "2_2") (pintype "passive"))
      (node (ref "C99") (pin "2") (pinfunction "2_2") (pintype "passive"))
      (node (ref "L1") (pin "2") (pinfunction "2_2") (pintype "passive"))
      (node (ref "L10") (pin "2") (pinfunction "2_2") (pintype "passive"))
      (node (ref "L11") (pin "2") (pinfunction "2_2") (pintype "passive"))
      (node (ref "L12") (pin "2") (pinfunction "2_2") (pintype "passive"))
      (node (ref "L13") (pin "2") (pinfunction "2_2") (pintype "passive"))
      (node (ref "L14") (pin "2") (pinfunction "2_2") (pintype "passive"))
      (node (ref "L15") (pin "2") (pinfunction "2_2") (pintype "passive"))
      (node (ref "L16") (pin "2") (pinfunction "2_2") (pintype "passive"))
      (node (ref "L2") (pin "2") (pinfunction "2_2") (pintype "passive"))
      (node (ref "L3") (pin "2") (pinfunction "2_2") (pintype "passive"))
      (node (ref "L4") (pin "2") (pinfunction "2_2") (pintype "passive"))
      (node (ref "L5") (pin "2") (pinfunction "2_2") (pintype "passive"))
      (node (ref "L6") (pin "2") (pinfunction "2_2") (pintype "passive"))
      (node (ref "L7") (pin "2") (pinfunction "2_2") (pintype "passive"))
      (node (ref "L8") (pin "2") (pinfunction "2_2") (pintype "passive"))
      (node (ref "L9") (pin "2") (pinfunction "2_2") (pintype "passive"))
    )
    (net (code "2") (name "/5.0V") (class "Default")
      (node (ref "C116") (pin "2") (pinfunction "2_2") (pintype "passive"))
      (node (ref "C117") (pin "2") (pinfunction "2_2") (pintype "passive"))
      (node (ref "C118") (pin "2") (pinfunction "2_2") (pintype "passive"))
      (node (ref "C119") (pin "2") (pinfunction "2_2") (pintype "passive"))
      (node (ref "C20") (pin "2") (pinfunction "2_2") (pintype "passive"))
      (node (ref "C21") (pin "2") (pinfunction "2_2") (pintype "passive"))
      (node (ref "C22") (pin "2") (pinfunction "2_2") (pintype "passive"))
      (node (ref "C23") (pin "2") (pinfunction "2_2") (pintype "passive"))
      (node (ref "C52") (pin "2") (pinfunction "2_2") (pintype "passive"))
      (node (ref "C53") (pin "2") (pinfunction "2_2") (pintype "passive"))
      (node (ref "C54") (pin "2") (pinfunction "2_2") (pintype "passive"))
      (node (ref "C55") (pin "2") (pinfunction "2_2") (pintype "passive"))
      (node (ref "C84") (pin "2") (pinfunction "2_2") (pintype "passive"))
      (node (ref "C85") (pin "2") (pinfunction "2_2") (pintype "passive"))
      (node (ref "C86") (pin "2") (pinfunction "2_2") (pintype "passive"))
      (node (ref "C87") (pin "2") (pinfunction "2_2") (pintype "passive"))
      (node (ref "D10") (pin "1") (pinfunction "A1_1") (pintype "passive"))
      (node (ref "D10") (pin "2") (pinfunction "A2_2") (pintype "passive"))
      (node (ref "D11") (pin "1") (pinfunction "A1_1") (pintype "passive"))
      (node (ref "D11") (pin "2") (pinfunction "A2_2") (pintype "passive"))
      (node (ref "D12") (pin "1") (pinfunction "A1_1") (pintype "passive"))
      (node (ref "D12") (pin "2") (pinfunction "A2_2") (pintype "passive"))
      (node (ref "D13") (pin "1") (pinfunction "A1_1") (pintype "passive"))
      (node (ref "D13") (pin "2") (pinfunction "A2_2") (pintype "passive"))
      (node (ref "D14") (pin "1") (pinfunction "A1_1") (pintype "passive"))
      (node (ref "D14") (pin "2") (pinfunction "A2_2") (pintype "passive"))
      (node (ref "D15") (pin "1") (pinfunction "A1_1") (pintype "passive"))
      (node (ref "D15") (pin "2") (pinfunction "A2_2") (pintype "passive"))
      (node (ref "D16") (pin "1") (pinfunction "A1_1") (pintype "passive"))
      (node (ref "D16") (pin "2") (pinfunction "A2_2") (pintype "passive"))
      (node (ref "D17") (pin "1") (pinfunction "A1_1") (pintype "passive"))
      (node (ref "D17") (pin "2") (pinfunction "A2_2") (pintype "passive"))
      (node (ref "D18") (pin "1") (pinfunction "A1_1") (pintype "passive"))
      (node (ref "D18") (pin "2") (pinfunction "A2_2") (pintype "passive"))
      (node (ref "D19") (pin "1") (pinfunction "A1_1") (pintype "passive"))
      (node (ref "D19") (pin "2") (pinfunction "A2_2") (pintype "passive"))
      (node (ref "D20") (pin "1") (pinfunction "A1_1") (pintype "passive"))
      (node (ref "D20") (pin "2") (pinfunction "A2_2") (pintype "passive"))
      (node (ref "D21") (pin "1") (pinfunction "A1_1") (pintype "passive"))
      (node (ref "D21") (pin "2") (pinfunction "A2_2") (pintype "passive"))
      (node (ref "D22") (pin "1") (pinfunction "A1_1") (pintype "passive"))
      (node (ref "D22") (pin "2") (pinfunction "A2_2") (pintype "passive"))
      (node (ref "D23") (pin "1") (pinfunction "A1_1") (pintype "passive"))
      (node (ref "D23") (pin "2") (pinfunction "A2_2") (pintype "passive"))
      (node (ref "D24") (pin "1") (pinfunction "A1_1") (pintype "passive"))
      (node (ref "D24") (pin "2") (pinfunction "A2_2") (pintype "passive"))
      (node (ref "D25") (pin "1") (pinfunction "A1_1") (pintype "passive"))
      (node (ref "D25") (pin "2") (pinfunction "A2_2") (pintype "passive"))
      (node (ref "U11") (pin "7") (pinfunction "VCC_7") (pintype "passive"))
      (node (ref "U12") (pin "7") (pinfunction "VCC_7") (pintype "passive"))
      (node (ref "U13") (pin "7") (pinfunction "VCC_7") (pintype "passive"))
      (node (ref "U14") (pin "7") (pinfunction "VCC_7") (pintype "passive"))
      (node (ref "U15") (pin "7") (pinfunction "VCC_7") (pintype "passive"))
      (node (ref "U16") (pin "7") (pinfunction "VCC_7") (pintype "passive"))
      (node (ref "U17") (pin "7") (pinfunction "VCC_7") (pintype "passive"))
      (node (ref "U18") (pin "7") (pinfunction "VCC_7") (pintype "passive"))
      (node (ref "U19") (pin "7") (pinfunction "VCC_7") (pintype "passive"))
      (node (ref "U20") (pin "7") (pinfunction "VCC_7") (pintype "passive"))
      (node (ref "U21") (pin "7") (pinfunction "VCC_7") (pintype "passive"))
      (node (ref "U22") (pin "7") (pinfunction "VCC_7") (pintype "passive"))
      (node (ref "U23") (pin "7") (pinfunction "VCC_7") (pintype "passive"))
      (node (ref "U24") (pin "7") (pinfunction "VCC_7") (pintype "passive"))
      (node (ref "U25") (pin "7") (pinfunction "VCC_7") (pintype "passive"))
      (node (ref "U26") (pin "7") (pinfunction "VCC_7") (pintype "passive"))
    )
    (net (code "3") (name "/12V") (class "Default")
      (node (ref "C101") (pin "2") (pinfunction "2_2") (pintype "passive"))
      (node (ref "C102") (pin "2") (pinfunction "2_2") (pintype "passive"))
      (node (ref "C106") (pin "2") (pinfunction "2_2") (pintype "passive"))
      (node (ref "C107") (pin "2") (pinfunction "2_2") (pintype "passive"))
      (node (ref "C111") (pin "2") (pinfunction "2_2") (pintype "passive"))
      (node (ref "C112") (pin "2") (pinfunction "2_2") (pintype "passive"))
      (node (ref "C128") (pin "2") (pinfunction "2_2") (pintype "passive"))
      (node (ref "C129") (pin "2") (pinfunction "2_2") (pintype "passive"))
      (node (ref "C133") (pin "2") (pinfunction "2_2") (pintype "passive"))
      (node (ref "C134") (pin "2") (pinfunction "2_2") (pintype "passive"))
      (node (ref "C138") (pin "2") (pinfunction "2_2") (pintype "passive"))
      (node (ref "C139") (pin "2") (pinfunction "2_2") (pintype "passive"))
      (node (ref "C143") (pin "2") (pinfunction "2_2") (pintype "passive"))
      (node (ref "C144") (pin "2") (pinfunction "2_2") (pintype "passive"))
      (node (ref "C32") (pin "2") (pinfunction "2_2") (pintype "passive"))
      (node (ref "C33") (pin "2") (pinfunction "2_2") (pintype "passive"))
      (node (ref "C37") (pin "2") (pinfunction "2_2") (pintype "passive"))
      (node (ref "C38") (pin "2") (pinfunction "2_2") (pintype "passive"))
      (node (ref "C42") (pin "2") (pinfunction "2_2") (pintype "passive"))
      (node (ref "C43") (pin "2") (pinfunction "2_2") (pintype "passive"))
      (node (ref "C47") (pin "2") (pinfunction "2_2") (pintype "passive"))
      (node (ref "C48") (pin "2") (pinfunction "2_2") (pintype "passive"))
      (node (ref "C64") (pin "2") (pinfunction "2_2") (pintype "passive"))
      (node (ref "C65") (pin "2") (pinfunction "2_2") (pintype "passive"))
      (node (ref "C69") (pin "2") (pinfunction "2_2") (pintype "passive"))
      (node (ref "C70") (pin "2") (pinfunction "2_2") (pintype "passive"))
      (node (ref "C74") (pin "2") (pinfunction "2_2") (pintype "passive"))
      (node (ref "C75") (pin "2") (pinfunction "2_2") (pintype "passive"))
      (node (ref "C79") (pin "2") (pinfunction "2_2") (pintype "passive"))
      (node (ref "C80") (pin "2") (pinfunction "2_2") (pintype "passive"))
      (node (ref "C96") (pin "2") (pinfunction "2_2") (pintype "passive"))
      (node (ref "C97") (pin "2") (pinfunction "2_2") (pintype "passive"))
      (node (ref "Q1") (pin "5") (pinfunction "D_5") (pintype "passive"))
      (node (ref "Q1") (pin "6") (pinfunction "D_6") (pintype "passive"))
      (node (ref "Q1") (pin "7") (pinfunction "D_7") (pintype "passive"))
      (node (ref "Q1") (pin "8") (pinfunction "D_8") (pintype "passive"))
      (node (ref "Q13") (pin "5") (pinfunction "D_5") (pintype "passive"))
      (node (ref "Q13") (pin "6") (pinfunction "D_6") (pintype "passive"))
      (node (ref "Q13") (pin "7") (pinfunction "D_7") (pintype "passive"))
      (node (ref "Q13") (pin "8") (pinfunction "D_8") (pintype "passive"))
      (node (ref "Q14") (pin "5") (pinfunction "D_5") (pintype "passive"))
      (node (ref "Q14") (pin "6") (pinfunction "D_6") (pintype "passive"))
      (node (ref "Q14") (pin "7") (pinfunction "D_7") (pintype "passive"))
      (node (ref "Q14") (pin "8") (pinfunction "D_8") (pintype "passive"))
      (node (ref "Q15") (pin "5") (pinfunction "D_5") (pintype "passive"))
      (node (ref "Q15") (pin "6") (pinfunction "D_6") (pintype "passive"))
      (node (ref "Q15") (pin "7") (pinfunction "D_7") (pintype "passive"))
      (node (ref "Q15") (pin "8") (pinfunction "D_8") (pintype "passive"))
      (node (ref "Q16") (pin "5") (pinfunction "D_5") (pintype "passive"))
      (node (ref "Q16") (pin "6") (pinfunction "D_6") (pintype "passive"))
      (node (ref "Q16") (pin "7") (pinfunction "D_7") (pintype "passive"))
      (node (ref "Q16") (pin "8") (pinfunction "D_8") (pintype "passive"))
      (node (ref "Q2") (pin "5") (pinfunction "D_5") (pintype "passive"))
      (node (ref "Q2") (pin "6") (pinfunction "D_6") (pintype "passive"))
      (node (ref "Q2") (pin "7") (pinfunction "D_7") (pintype "passive"))
      (node (ref "Q2") (pin "8") (pinfunction "D_8") (pintype "passive"))
      (node (ref "Q25") (pin "5") (pinfunction "D_5") (pintype "passive"))
      (node (ref "Q25") (pin "6") (pinfunction "D_6") (pintype "passive"))
      (node (ref "Q25") (pin "7") (pinfunction "D_7") (pintype "passive"))
      (node (ref "Q25") (pin "8") (pinfunction "D_8") (pintype "passive"))
      (node (ref "Q26") (pin "5") (pinfunction "D_5") (pintype "passive"))
      (node (ref "Q26") (pin "6") (pinfunction "D_6") (pintype "passive"))
      (node (ref "Q26") (pin "7") (pinfunction "D_7") (pintype "passive"))
      (node (ref "Q26") (pin "8") (pinfunction "D_8") (pintype "passive"))
      (node (ref "Q27") (pin "5") (pinfunction "D_5") (pintype "passive"))
      (node (ref "Q27") (pin "6") (pinfunction "D_6") (pintype "passive"))
      (node (ref "Q27") (pin "7") (pinfunction "D_7") (pintype "passive"))
      (node (ref "Q27") (pin "8") (pinfunction "D_8") (pintype "passive"))
      (node (ref "Q28") (pin "5") (pinfunction "D_5") (pintype "passive"))
      (node (ref "Q28") (pin "6") (pinfunction "D_6") (pintype "passive"))
      (node (ref "Q28") (pin "7") (pinfunction "D_7") (pintype "passive"))
      (node (ref "Q28") (pin "8") (pinfunction "D_8") (pintype "passive"))
      (node (ref "Q3") (pin "5") (pinfunction "D_5") (pintype "passive"))
      (node (ref "Q3") (pin "6") (pinfunction "D_6") (pintype "passive"))
      (node (ref "Q3") (pin "7") (pinfunction "D_7") (pintype "passive"))
      (node (ref "Q3") (pin "8") (pinfunction "D_8") (pintype "passive"))
      (node (ref "Q37") (pin "5") (pinfunction "D_5") (pintype "passive"))
      (node (ref "Q37") (pin "6") (pinfunction "D_6") (pintype "passive"))
      (node (ref "Q37") (pin "7") (pinfunction "D_7") (pintype "passive"))
      (node (ref "Q37") (pin "8") (pinfunction "D_8") (pintype "passive"))
      (node (ref "Q38") (pin "5") (pinfunction "D_5") (pintype "passive"))
      (node (ref "Q38") (pin "6") (pinfunction "D_6") (pintype "passive"))
      (node (ref "Q38") (pin "7") (pinfunction "D_7") (pintype "passive"))
      (node (ref "Q38") (pin "8") (pinfunction "D_8") (pintype "passive"))
      (node (ref "Q39") (pin "5") (pinfunction "D_5") (pintype "passive"))
      (node (ref "Q39") (pin "6") (pinfunction "D_6") (pintype "passive"))
      (node (ref "Q39") (pin "7") (pinfunction "D_7") (pintype "passive"))
      (node (ref "Q39") (pin "8") (pinfunction "D_8") (pintype "passive"))
      (node (ref "Q4") (pin "5") (pinfunction "D_5") (pintype "passive"))
      (node (ref "Q4") (pin "6") (pinfunction "D_6") (pintype "passive"))
      (node (ref "Q4") (pin "7") (pinfunction "D_7") (pintype "passive"))
      (node (ref "Q4") (pin "8") (pinfunction "D_8") (pintype "passive"))
      (node (ref "Q40") (pin "5") (pinfunction "D_5") (pintype "passive"))
      (node (ref "Q40") (pin "6") (pinfunction "D_6") (pintype "passive"))
      (node (ref "Q40") (pin "7") (pinfunction "D_7") (pintype "passive"))
      (node (ref "Q40") (pin "8") (pinfunction "D_8") (pintype "passive"))
    )
    (net (code "4") (name "/BOOT1") (class "Default")
      (node (ref "C28") (pin "1") (pinfunction "1_1") (pintype "passive"))
      (node (ref "D10") (pin "3") (pinfunction "CC_3") (pintype "passive"))
      (node (ref "U11") (pin "8") (pinfunction "BOOST_8") (pintype "passive"))
    )
    (net (code "5") (name "/BOOT2") (class "Default")
      (node (ref "C60") (pin "1") (pinfunction "1_1") (pintype "passive"))
      (node (ref "D14") (pin "3") (pinfunction "CC_3") (pintype "passive"))
      (node (ref "U15") (pin "8") (pinfunction "BOOST_8") (pintype "passive"))
    )
    (net (code "6") (name "/BOOT3") (class "Default")
      (node (ref "C92") (pin "1") (pinfunction "1_1") (pintype "passive"))
      (node (ref "D18") (pin "3") (pinfunction "CC_3") (pintype "passive"))
      (node (ref "U19") (pin "8") (pinfunction "BOOST_8") (pintype "passive"))
    )
    (net (code "7") (name "/BOOT4") (class "Default")
      (node (ref "C124") (pin "1") (pinfunction "1_1") (pintype "passive"))
      (node (ref "D22") (pin "3") (pinfunction "CC_3") (pintype "passive"))
      (node (ref "U23") (pin "8") (pinfunction "BOOST_8") (pintype "passive"))
    )
    (net (code "8") (name "/BOOT5") (class "Default")
      (node (ref "C29") (pin "1") (pinfunction "1_1") (pintype "passive"))
      (node (ref "D11") (pin "3") (pinfunction "CC_3") (pintype "passive"))
      (node (ref "U12") (pin "8") (pinfunction "BOOST_8") (pintype "passive"))
    )
    (net (code "9") (name "/BOOT6") (class "Default")
      (node (ref "C61") (pin "1") (pinfunction "1_1") (pintype "passive"))
      (node (ref "D15") (pin "3") (pinfunction "CC_3") (pintype "passive"))
      (node (ref "U16") (pin "8") (pinfunction "BOOST_8") (pintype "passive"))
    )
    (net (code "10") (name "/BOOT7") (class "Default")
      (node (ref "C93") (pin "1") (pinfunction "1_1") (pintype "passive"))
      (node (ref "D19") (pin "3") (pinfunction "CC_3") (pintype "passive"))
      (node (ref "U20") (pin "8") (pinfunction "BOOST_8") (pintype "passive"))
    )
    (net (code "11") (name "/BOOT8") (class "Default")
      (node (ref "C125") (pin "1") (pinfunction "1_1") (pintype "passive"))
      (node (ref "D23") (pin "3") (pinfunction "CC_3") (pintype "passive"))
      (node (ref "U24") (pin "8") (pinfunction "BOOST_8") (pintype "passive"))
    )
    (net (code "12") (name "/BOOT9") (class "Default")
      (node (ref "C30") (pin "1") (pinfunction "1_1") (pintype "passive"))
      (node (ref "D12") (pin "3") (pinfunction "CC_3") (pintype "passive"))
      (node (ref "U13") (pin "8") (pinfunction "BOOST_8") (pintype "passive"))
    )
    (net (code "13") (name "/BOOT10") (class "Default")
      (node (ref "C62") (pin "1") (pinfunction "1_1") (pintype "passive"))
      (node (ref "D16") (pin "3") (pinfunction "CC_3") (pintype "passive"))
      (node (ref "U17") (pin "8") (pinfunction "BOOST_8") (pintype "passive"))
    )
    (net (code "14") (name "/BOOT11") (class "Default")
      (node (ref "C94") (pin "1") (pinfunction "1_1") (pintype "passive"))
      (node (ref "D20") (pin "3") (pinfunction "CC_3") (pintype "passive"))
      (node (ref "U21") (pin "8") (pinfunction "BOOST_8") (pintype "passive"))
    )
    (net (code "15") (name "/BOOT12") (class "Default")
      (node (ref "C126") (pin "1") (pinfunction "1_1") (pintype "passive"))
      (node (ref "D24") (pin "3") (pinfunction "CC_3") (pintype "passive"))
      (node (ref "U25") (pin "8") (pinfunction "BOOST_8") (pintype "passive"))
    )
    (net (code "16") (name "/BOOT13") (class "Default")
      (node (ref "C31") (pin "1") (pinfunction "1_1") (pintype "passive"))
      (node (ref "D13") (pin "3") (pinfunction "CC_3") (pintype "passive"))
      (node (ref "U14") (pin "8") (pinfunction "BOOST_8") (pintype "passive"))
    )
    (net (code "17") (name "/BOOT14") (class "Default")
      (node (ref "C63") (pin "1") (pinfunction "1_1") (pintype "passive"))
      (node (ref "D17") (pin "3") (pinfunction "CC_3") (pintype "passive"))
      (node (ref "U18") (pin "8") (pinfunction "BOOST_8") (pintype "passive"))
    )
    (net (code "18") (name "/BOOT15") (class "Default")
      (node (ref "C95") (pin "1") (pinfunction "1_1") (pintype "passive"))
      (node (ref "D21") (pin "3") (pinfunction "CC_3") (pintype "passive"))
      (node (ref "U22") (pin "8") (pinfunction "BOOST_8") (pintype "passive"))
    )
    (net (code "19") (name "/BOOT16") (class "Default")
      (node (ref "C127") (pin "1") (pinfunction "1_1") (pintype "passive"))
      (node (ref "D25") (pin "3") (pinfunction "CC_3") (pintype "passive"))
      (node (ref "U26") (pin "8") (pinfunction "BOOST_8") (pintype "passive"))
    )
    (net (code "20") (name "/DRVLogic") (class "Default")
      (node (ref "C120") (pin "1") (pinfunction "1_1") (pintype "passive"))
      (node (ref "C121") (pin "1") (pinfunction "1_1") (pintype "passive"))
      (node (ref "C122") (pin "1") (pinfunction "1_1") (pintype "passive"))
      (node (ref "C123") (pin "1") (pinfunction "1_1") (pintype "passive"))
      (node (ref "C24") (pin "1") (pinfunction "1_1") (pintype "passive"))
      (node (ref "C25") (pin "1") (pinfunction "1_1") (pintype "passive"))
      (node (ref "C26") (pin "1") (pinfunction "1_1") (pintype "passive"))
      (node (ref "C27") (pin "1") (pinfunction "1_1") (pintype "passive"))
      (node (ref "C56") (pin "1") (pinfunction "1_1") (pintype "passive"))
      (node (ref "C57") (pin "1") (pinfunction "1_1") (pintype "passive"))
      (node (ref "C58") (pin "1") (pinfunction "1_1") (pintype "passive"))
      (node (ref "C59") (pin "1") (pinfunction "1_1") (pintype "passive"))
      (node (ref "C88") (pin "1") (pinfunction "1_1") (pintype "passive"))
      (node (ref "C89") (pin "1") (pinfunction "1_1") (pintype "passive"))
      (node (ref "C90") (pin "1") (pinfunction "1_1") (pintype "passive"))
      (node (ref "C91") (pin "1") (pinfunction "1_1") (pintype "passive"))
      (node (ref "U11") (pin "6") (pinfunction "VLOGIC_6") (pintype "passive"))
      (node (ref "U12") (pin "6") (pinfunction "VLOGIC_6") (pintype "passive"))
      (node (ref "U13") (pin "6") (pinfunction "VLOGIC_6") (pintype "passive"))
      (node (ref "U14") (pin "6") (pinfunction "VLOGIC_6") (pintype "passive"))
      (node (ref "U15") (pin "6") (pinfunction "VLOGIC_6") (pintype "passive"))
      (node (ref "U16") (pin "6") (pinfunction "VLOGIC_6") (pintype "passive"))
      (node (ref "U17") (pin "6") (pinfunction "VLOGIC_6") (pintype "passive"))
      (node (ref "U18") (pin "6") (pinfunction "VLOGIC_6") (pintype "passive"))
      (node (ref "U19") (pin "6") (pinfunction "VLOGIC_6") (pintype "passive"))
      (node (ref "U20") (pin "6") (pinfunction "VLOGIC_6") (pintype "passive"))
      (node (ref "U21") (pin "6") (pinfunction "VLOGIC_6") (pintype "passive"))
      (node (ref "U22") (pin "6") (pinfunction "VLOGIC_6") (pintype "passive"))
      (node (ref "U23") (pin "6") (pinfunction "VLOGIC_6") (pintype "passive"))
      (node (ref "U24") (pin "6") (pinfunction "VLOGIC_6") (pintype "passive"))
      (node (ref "U25") (pin "6") (pinfunction "VLOGIC_6") (pintype "passive"))
      (node (ref "U26") (pin "6") (pinfunction "VLOGIC_6") (pintype "passive"))
    )
    (net (code "21") (name "/HO1") (class "Default")
      (node (ref "Q1") (pin "4") (pinfunction "G_4") (pintype "passive"))
      (node (ref "U11") (pin "1") (pinfunction "TG_1") (pintype "passive"))
    )
    (net (code "22") (name "/HO2") (class "Default")
      (node (ref "Q13") (pin "4") (pinfunction "G_4") (pintype "passive"))
      (node (ref "U15") (pin "1") (pinfunction "TG_1") (pintype "passive"))
    )
    (net (code "23") (name "/HO3") (class "Default")
      (node (ref "Q25") (pin "4") (pinfunction "G_4") (pintype "passive"))
      (node (ref "U19") (pin "1") (pinfunction "TG_1") (pintype "passive"))
    )
    (net (code "24") (name "/HO4") (class "Default")
      (node (ref "Q37") (pin "4") (pinfunction "G_4") (pintype "passive"))
      (node (ref "U23") (pin "1") (pinfunction "TG_1") (pintype "passive"))
    )
    (net (code "25") (name "/HO5") (class "Default")
      (node (ref "Q2") (pin "4") (pinfunction "G_4") (pintype "passive"))
      (node (ref "U12") (pin "1") (pinfunction "TG_1") (pintype "passive"))
    )
    (net (code "26") (name "/HO6") (class "Default")
      (node (ref "Q14") (pin "4") (pinfunction "G_4") (pintype "passive"))
      (node (ref "U16") (pin "1") (pinfunction "TG_1") (pintype "passive"))
    )
    (net (code "27") (name "/HO7") (class "Default")
      (node (ref "Q26") (pin "4") (pinfunction "G_4") (pintype "passive"))
      (node (ref "U20") (pin "1") (pinfunction "TG_1") (pintype "passive"))
    )
    (net (code "28") (name "/HO8") (class "Default")
      (node (ref "Q38") (pin "4") (pinfunction "G_4") (pintype "passive"))
      (node (ref "U24") (pin "1") (pinfunction "TG_1") (pintype "passive"))
    )
    (net (code "29") (name "/HO9") (class "Default")
      (node (ref "Q3") (pin "4") (pinfunction "G_4") (pintype "passive"))
      (node (ref "U13") (pin "1") (pinfunction "TG_1") (pintype "passive"))
    )
    (net (code "30") (name "/HO10") (class "Default")
      (node (ref "Q15") (pin "4") (pinfunction "G_4") (pintype "passive"))
      (node (ref "U17") (pin "1") (pinfunction "TG_1") (pintype "passive"))
    )
    (net (code "31") (name "/HO11") (class "Default")
      (node (ref "Q27") (pin "4") (pinfunction "G_4") (pintype "passive"))
      (node (ref "U21") (pin "1") (pinfunction "TG_1") (pintype "passive"))
    )
    (net (code "32") (name "/HO12") (class "Default")
      (node (ref "Q39") (pin "4") (pinfunction "G_4") (pintype "passive"))
      (node (ref "U25") (pin "1") (pinfunction "TG_1") (pintype "passive"))
    )
    (net (code "33") (name "/HO13") (class "Default")
      (node (ref "Q4") (pin "4") (pinfunction "G_4") (pintype "passive"))
      (node (ref "U14") (pin "1") (pinfunction "TG_1") (pintype "passive"))
    )
    (net (code "34") (name "/HO14") (class "Default")
      (node (ref "Q16") (pin "4") (pinfunction "G_4") (pintype "passive"))
      (node (ref "U18") (pin "1") (pinfunction "TG_1") (pintype "passive"))
    )
    (net (code "35") (name "/HO15") (class "Default")
      (node (ref "Q28") (pin "4") (pinfunction "G_4") (pintype "passive"))
      (node (ref "U22") (pin "1") (pinfunction "TG_1") (pintype "passive"))
    )
    (net (code "36") (name "/HO16") (class "Default")
      (node (ref "Q40") (pin "4") (pinfunction "G_4") (pintype "passive"))
      (node (ref "U26") (pin "1") (pinfunction "TG_1") (pintype "passive"))
    )
    (net (code "37") (name "/LO1") (class "Default")
      (node (ref "Q5") (pin "4") (pinfunction "G_4") (pintype "passive"))
      (node (ref "Q6") (pin "4") (pinfunction "G_4") (pintype "passive"))
      (node (ref "U11") (pin "3") (pinfunction "BG_3") (pintype "passive"))
    )
    (net (code "38") (name "/LO2") (class "Default")
      (node (ref "Q17") (pin "4") (pinfunction "G_4") (pintype "passive"))
      (node (ref "Q18") (pin "4") (pinfunction "G_4") (pintype "passive"))
      (node (ref "U15") (pin "3") (pinfunction "BG_3") (pintype "passive"))
    )
    (net (code "39") (name "/LO3") (class "Default")
      (node (ref "Q29") (pin "4") (pinfunction "G_4") (pintype "passive"))
      (node (ref "Q30") (pin "4") (pinfunction "G_4") (pintype "passive"))
      (node (ref "U19") (pin "3") (pinfunction "BG_3") (pintype "passive"))
    )
    (net (code "40") (name "/LO4") (class "Default")
      (node (ref "Q41") (pin "4") (pinfunction "G_4") (pintype "passive"))
      (node (ref "Q42") (pin "4") (pinfunction "G_4") (pintype "passive"))
      (node (ref "U23") (pin "3") (pinfunction "BG_3") (pintype "passive"))
    )
    (net (code "41") (name "/LO5") (class "Default")
      (node (ref "Q7") (pin "4") (pinfunction "G_4") (pintype "passive"))
      (node (ref "Q8") (pin "4") (pinfunction "G_4") (pintype "passive"))
      (node (ref "U12") (pin "3") (pinfunction "BG_3") (pintype "passive"))
    )
    (net (code "42") (name "/LO6") (class "Default")
      (node (ref "Q19") (pin "4") (pinfunction "G_4") (pintype "passive"))
      (node (ref "Q20") (pin "4") (pinfunction "G_4") (pintype "passive"))
      (node (ref "U16") (pin "3") (pinfunction "BG_3") (pintype "passive"))
    )
    (net (code "43") (name "/LO7") (class "Default")
      (node (ref "Q31") (pin "4") (pinfunction "G_4") (pintype "passive"))
      (node (ref "Q32") (pin "4") (pinfunction "G_4") (pintype "passive"))
      (node (ref "U20") (pin "3") (pinfunction "BG_3") (pintype "passive"))
    )
    (net (code "44") (name "/LO8") (class "Default")
      (node (ref "Q43") (pin "4") (pinfunction "G_4") (pintype "passive"))
      (node (ref "Q44") (pin "4") (pinfunction "G_4") (pintype "passive"))
      (node (ref "U24") (pin "3") (pinfunction "BG_3") (pintype "passive"))
    )
    (net (code "45") (name "/LO9") (class "Default")
      (node (ref "Q10") (pin "4") (pinfunction "G_4") (pintype "passive"))
      (node (ref "Q9") (pin "4") (pinfunction "G_4") (pintype "passive"))
      (node (ref "U13") (pin "3") (pinfunction "BG_3") (pintype "passive"))
    )
    (net (code "46") (name "/LO10") (class "Default")
      (node (ref "Q21") (pin "4") (pinfunction "G_4") (pintype "passive"))
      (node (ref "Q22") (pin "4") (pinfunction "G_4") (pintype "passive"))
      (node (ref "U17") (pin "3") (pinfunction "BG_3") (pintype "passive"))
    )
    (net (code "47") (name "/LO11") (class "Default")
      (node (ref "Q33") (pin "4") (pinfunction "G_4") (pintype "passive"))
      (node (ref "Q34") (pin "4") (pinfunction "G_4") (pintype "passive"))
      (node (ref "U21") (pin "3") (pinfunction "BG_3") (pintype "passive"))
    )
    (net (code "48") (name "/LO12") (class "Default")
      (node (ref "Q45") (pin "4") (pinfunction "G_4") (pintype "passive"))
      (node (ref "Q46") (pin "4") (pinfunction "G_4") (pintype "passive"))
      (node (ref "U25") (pin "3") (pinfunction "BG_3") (pintype "passive"))
    )
    (net (code "49") (name "/LO13") (class "Default")
      (node (ref "Q11") (pin "4") (pinfunction "G_4") (pintype "passive"))
      (node (ref "Q12") (pin "4") (pinfunction "G_4") (pintype "passive"))
      (node (ref "U14") (pin "3") (pinfunction "BG_3") (pintype "passive"))
    )
    (net (code "50") (name "/LO14") (class "Default")
      (node (ref "Q23") (pin "4") (pinfunction "G_4") (pintype "passive"))
      (node (ref "Q24") (pin "4") (pinfunction "G_4") (pintype "passive"))
      (node (ref "U18") (pin "3") (pinfunction "BG_3") (pintype "passive"))
    )
    (net (code "51") (name "/LO15") (class "Default")
      (node (ref "Q35") (pin "4") (pinfunction "G_4") (pintype "passive"))
      (node (ref "Q36") (pin "4") (pinfunction "G_4") (pintype "passive"))
      (node (ref "U22") (pin "3") (pinfunction "BG_3") (pintype "passive"))
    )
    (net (code "52") (name "/LO16") (class "Default")
      (node (ref "Q47") (pin "4") (pinfunction "G_4") (pintype "passive"))
      (node (ref "Q48") (pin "4") (pinfunction "G_4") (pintype "passive"))
      (node (ref "U26") (pin "3") (pinfunction "BG_3") (pintype "passive"))
    )
    (net (code "53") (name "/PWM1H") (class "Default")
      (node (ref "U12") (pin "5") (pinfunction "IN_5") (pintype "passive"))
      (node (ref "U14") (pin "5") (pinfunction "IN_5") (pintype "passive"))
    )
    (net (code "54") (name "/PWM1L") (class "Default")
      (node (ref "U11") (pin "5") (pinfunction "IN_5") (pintype "passive"))
      (node (ref "U13") (pin "5") (pinfunction "IN_5") (pintype "passive"))
    )
    (net (code "55") (name "/PWM2H") (class "Default")
      (node (ref "U16") (pin "5") (pinfunction "IN_5") (pintype "passive"))
      (node (ref "U18") (pin "5") (pinfunction "IN_5") (pintype "passive"))
    )
    (net (code "56") (name "/PWM2L") (class "Default")
      (node (ref "U15") (pin "5") (pinfunction "IN_5") (pintype "passive"))
      (node (ref "U17") (pin "5") (pinfunction "IN_5") (pintype "passive"))
    )
    (net (code "57") (name "/PWM3H") (class "Default")
      (node (ref "U20") (pin "5") (pinfunction "IN_5") (pintype "passive"))
      (node (ref "U22") (pin "5") (pinfunction "IN_5") (pintype "passive"))
    )
    (net (code "58") (name "/PWM3L") (class "Default")
      (node (ref "U19") (pin "5") (pinfunction "IN_5") (pintype "passive"))
      (node (ref "U21") (pin "5") (pinfunction "IN_5") (pintype "passive"))
    )
    (net (code "59") (name "/PWM4H") (class "Default")
      (node (ref "U24") (pin "5") (pinfunction "IN_5") (pintype "passive"))
      (node (ref "U26") (pin "5") (pinfunction "IN_5") (pintype "passive"))
    )
    (net (code "60") (name "/PWM4L") (class "Default")
      (node (ref "U23") (pin "5") (pinfunction "IN_5") (pintype "passive"))
      (node (ref "U25") (pin "5") (pinfunction "IN_5") (pintype "passive"))
    )
    (net (code "61") (name "/SWN1") (class "Default")
      (node (ref "C28") (pin "2") (pinfunction "2_2") (pintype "passive"))
      (node (ref "L1") (pin "1") (pinfunction "1_1") (pintype "passive"))
      (node (ref "Q1") (pin "1") (pinfunction "S_1") (pintype "passive"))
      (node (ref "Q1") (pin "2") (pinfunction "S_2") (pintype "passive"))
      (node (ref "Q1") (pin "3") (pinfunction "S_3") (pintype "passive"))
      (node (ref "Q5") (pin "5") (pinfunction "D_5") (pintype "passive"))
      (node (ref "Q5") (pin "6") (pinfunction "D_6") (pintype "passive"))
      (node (ref "Q5") (pin "7") (pinfunction "D_7") (pintype "passive"))
      (node (ref "Q5") (pin "8") (pinfunction "D_8") (pintype "passive"))
      (node (ref "Q6") (pin "5") (pinfunction "D_5") (pintype "passive"))
      (node (ref "Q6") (pin "6") (pinfunction "D_6") (pintype "passive"))
      (node (ref "Q6") (pin "7") (pinfunction "D_7") (pintype "passive"))
      (node (ref "Q6") (pin "8") (pinfunction "D_8") (pintype "passive"))
      (node (ref "U11") (pin "2") (pinfunction "TS_2") (pintype "passive"))
    )
    (net (code "62") (name "/SWN2") (class "Default")
      (node (ref "C60") (pin "2") (pinfunction "2_2") (pintype "passive"))
      (node (ref "L5") (pin "1") (pinfunction "1_1") (pintype "passive"))
      (node (ref "Q13") (pin "1") (pinfunction "S_1") (pintype "passive"))
      (node (ref "Q13") (pin "2") (pinfunction "S_2") (pintype "passive"))
      (node (ref "Q13") (pin "3") (pinfunction "S_3") (pintype "passive"))
      (node (ref "Q17") (pin "5") (pinfunction "D_5") (pintype "passive"))
      (node (ref "Q17") (pin "6") (pinfunction "D_6") (pintype "passive"))
      (node (ref "Q17") (pin "7") (pinfunction "D_7") (pintype "passive"))
      (node (ref "Q17") (pin "8") (pinfunction "D_8") (pintype "passive"))
      (node (ref "Q18") (pin "5") (pinfunction "D_5") (pintype "passive"))
      (node (ref "Q18") (pin "6") (pinfunction "D_6") (pintype "passive"))
      (node (ref "Q18") (pin "7") (pinfunction "D_7") (pintype "passive"))
      (node (ref "Q18") (pin "8") (pinfunction "D_8") (pintype "passive"))
      (node (ref "U15") (pin "2") (pinfunction "TS_2") (pintype "passive"))
    )
    (net (code "63") (name "/SWN3") (class "Default")
      (node (ref "C92") (pin "2") (pinfunction "2_2") (pintype "passive"))
      (node (ref "L9") (pin "1") (pinfunction "1_1") (pintype "passive"))
      (node (ref "Q25") (pin "1") (pinfunction "S_1") (pintype "passive"))
      (node (ref "Q25") (pin "2") (pinfunction "S_2") (pintype "passive"))
      (node (ref "Q25") (pin "3") (pinfunction "S_3") (pintype "passive"))
      (node (ref "Q29") (pin "5") (pinfunction "D_5") (pintype "passive"))
      (node (ref "Q29") (pin "6") (pinfunction "D_6") (pintype "passive"))
      (node (ref "Q29") (pin "7") (pinfunction "D_7") (pintype "passive"))
      (node (ref "Q29") (pin "8") (pinfunction "D_8") (pintype "passive"))
      (node (ref "Q30") (pin "5") (pinfunction "D_5") (pintype "passive"))
      (node (ref "Q30") (pin "6") (pinfunction "D_6") (pintype "passive"))
      (node (ref "Q30") (pin "7") (pinfunction "D_7") (pintype "passive"))
      (node (ref "Q30") (pin "8") (pinfunction "D_8") (pintype "passive"))
      (node (ref "U19") (pin "2") (pinfunction "TS_2") (pintype "passive"))
    )
    (net (code "64") (name "/SWN4") (class "Default")
      (node (ref "C124") (pin "2") (pinfunction "2_2") (pintype "passive"))
      (node (ref "L13") (pin "1") (pinfunction "1_1") (pintype "passive"))
      (node (ref "Q37") (pin "1") (pinfunction "S_1") (pintype "passive"))
      (node (ref "Q37") (pin "2") (pinfunction "S_2") (pintype "passive"))
      (node (ref "Q37") (pin "3") (pinfunction "S_3") (pintype "passive"))
      (node (ref "Q41") (pin "5") (pinfunction "D_5") (pintype "passive"))
      (node (ref "Q41") (pin "6") (pinfunction "D_6") (pintype "passive"))
      (node (ref "Q41") (pin "7") (pinfunction "D_7") (pintype "passive"))
      (node (ref "Q41") (pin "8") (pinfunction "D_8") (pintype "passive"))
      (node (ref "Q42") (pin "5") (pinfunction "D_5") (pintype "passive"))
      (node (ref "Q42") (pin "6") (pinfunction "D_6") (pintype "passive"))
      (node (ref "Q42") (pin "7") (pinfunction "D_7") (pintype "passive"))
      (node (ref "Q42") (pin "8") (pinfunction "D_8") (pintype "passive"))
      (node (ref "U23") (pin "2") (pinfunction "TS_2") (pintype "passive"))
    )
    (net (code "65") (name "/SWN5") (class "Default")
      (node (ref "C29") (pin "2") (pinfunction "2_2") (pintype "passive"))
      (node (ref "L2") (pin "1") (pinfunction "1_1") (pintype "passive"))
      (node (ref "Q2") (pin "1") (pinfunction "S_1") (pintype "passive"))
      (node (ref "Q2") (pin "2") (pinfunction "S_2") (pintype "passive"))
      (node (ref "Q2") (pin "3") (pinfunction "S_3") (pintype "passive"))
      (node (ref "Q7") (pin "5") (pinfunction "D_5") (pintype "passive"))
      (node (ref "Q7") (pin "6") (pinfunction "D_6") (pintype "passive"))
      (node (ref "Q7") (pin "7") (pinfunction "D_7") (pintype "passive"))
      (node (ref "Q7") (pin "8") (pinfunction "D_8") (pintype "passive"))
      (node (ref "Q8") (pin "5") (pinfunction "D_5") (pintype "passive"))
      (node (ref "Q8") (pin "6") (pinfunction "D_6") (pintype "passive"))
      (node (ref "Q8") (pin "7") (pinfunction "D_7") (pintype "passive"))
      (node (ref "Q8") (pin "8") (pinfunction "D_8") (pintype "passive"))
      (node (ref "U12") (pin "2") (pinfunction "TS_2") (pintype "passive"))
    )
    (net (code "66") (name "/SWN6") (class "Default")
      (node (ref "C61") (pin "2") (pinfunction "2_2") (pintype "passive"))
      (node (ref "L6") (pin "1") (pinfunction "1_1") (pintype "passive"))
      (node (ref "Q14") (pin "1") (pinfunction "S_1") (pintype "passive"))
      (node (ref "Q14") (pin "2") (pinfunction "S_2") (pintype "passive"))
      (node (ref "Q14") (pin "3") (pinfunction "S_3") (pintype "passive"))
      (node (ref "Q19") (pin "5") (pinfunction "D_5") (pintype "passive"))
      (node (ref "Q19") (pin "6") (pinfunction "D_6") (pintype "passive"))
      (node (ref "Q19") (pin "7") (pinfunction "D_7") (pintype "passive"))
      (node (ref "Q19") (pin "8") (pinfunction "D_8") (pintype "passive"))
      (node (ref "Q20") (pin "5") (pinfunction "D_5") (pintype "passive"))
      (node (ref "Q20") (pin "6") (pinfunction "D_6") (pintype "passive"))
      (node (ref "Q20") (pin "7") (pinfunction "D_7") (pintype "passive"))
      (node (ref "Q20") (pin "8") (pinfunction "D_8") (pintype "passive"))
      (node (ref "U16") (pin "2") (pinfunction "TS_2") (pintype "passive"))
    )
    (net (code "67") (name "/SWN7") (class "Default")
      (node (ref "C93") (pin "2") (pinfunction "2_2") (pintype "passive"))
      (node (ref "L10") (pin "1") (pinfunction "1_1") (pintype "passive"))
      (node (ref "Q26") (pin "1") (pinfunction "S_1") (pintype "passive"))
      (node (ref "Q26") (pin "2") (pinfunction "S_2") (pintype "passive"))
      (node (ref "Q26") (pin "3") (pinfunction "S_3") (pintype "passive"))
      (node (ref "Q31") (pin "5") (pinfunction "D_5") (pintype "passive"))
      (node (ref "Q31") (pin "6") (pinfunction "D_6") (pintype "passive"))
      (node (ref "Q31") (pin "7") (pinfunction "D_7") (pintype "passive"))
      (node (ref "Q31") (pin "8") (pinfunction "D_8") (pintype "passive"))
      (node (ref "Q32") (pin "5") (pinfunction "D_5") (pintype "passive"))
      (node (ref "Q32") (pin "6") (pinfunction "D_6") (pintype "passive"))
      (node (ref "Q32") (pin "7") (pinfunction "D_7") (pintype "passive"))
      (node (ref "Q32") (pin "8") (pinfunction "D_8") (pintype "passive"))
      (node (ref "U20") (pin "2") (pinfunction "TS_2") (pintype "passive"))
    )
    (net (code "68") (name "/SWN8") (class "Default")
      (node (ref "C125") (pin "2") (pinfunction "2_2") (pintype "passive"))
      (node (ref "L14") (pin "1") (pinfunction "1_1") (pintype "passive"))
      (node (ref "Q38") (pin "1") (pinfunction "S_1") (pintype "passive"))
      (node (ref "Q38") (pin "2") (pinfunction "S_2") (pintype "passive"))
      (node (ref "Q38") (pin "3") (pinfunction "S_3") (pintype "passive"))
      (node (ref "Q43") (pin "5") (pinfunction "D_5") (pintype "passive"))
      (node (ref "Q43") (pin "6") (pinfunction "D_6") (pintype "passive"))
      (node (ref "Q43") (pin "7") (pinfunction "D_7") (pintype "passive"))
      (node (ref "Q43") (pin "8") (pinfunction "D_8") (pintype "passive"))
      (node (ref "Q44") (pin "5") (pinfunction "D_5") (pintype "passive"))
      (node (ref "Q44") (pin "6") (pinfunction "D_6") (pintype "passive"))
      (node (ref "Q44") (pin "7") (pinfunction "D_7") (pintype "passive"))
      (node (ref "Q44") (pin "8") (pinfunction "D_8") (pintype "passive"))
      (node (ref "U24") (pin "2") (pinfunction "TS_2") (pintype "passive"))
    )
    (net (code "69") (name "/SWN9") (class "Default")
      (node (ref "C30") (pin "2") (pinfunction "2_2") (pintype "passive"))
      (node (ref "L3") (pin "1") (pinfunction "1_1") (pintype "passive"))
      (node (ref "Q10") (pin "5") (pinfunction "D_5") (pintype "passive"))
      (node (ref "Q10") (pin "6") (pinfunction "D_6") (pintype "passive"))
      (node (ref "Q10") (pin "7") (pinfunction "D_7") (pintype "passive"))
      (node (ref "Q10") (pin "8") (pinfunction "D_8") (pintype "passive"))
      (node (ref "Q3") (pin "1") (pinfunction "S_1") (pintype "passive"))
      (node (ref "Q3") (pin "2") (pinfunction "S_2") (pintype "passive"))
      (node (ref "Q3") (pin "3") (pinfunction "S_3") (pintype "passive"))
      (node (ref "Q9") (pin "5") (pinfunction "D_5") (pintype "passive"))
      (node (ref "Q9") (pin "6") (pinfunction "D_6") (pintype "passive"))
      (node (ref "Q9") (pin "7") (pinfunction "D_7") (pintype "passive"))
      (node (ref "Q9") (pin "8") (pinfunction "D_8") (pintype "passive"))
      (node (ref "U13") (pin "2") (pinfunction "TS_2") (pintype "passive"))
    )
    (net (code "70") (name "/SWN10") (class "Default")
      (node (ref "C62") (pin "2") (pinfunction "2_2") (pintype "passive"))
      (node (ref "L7") (pin "1") (pinfunction "1_1") (pintype "passive"))
      (node (ref "Q15") (pin "1") (pinfunction "S_1") (pintype "passive"))
      (node (ref "Q15") (pin "2") (pinfunction "S_2") (pintype "passive"))
      (node (ref "Q15") (pin "3") (pinfunction "S_3") (pintype "passive"))
      (node (ref "Q21") (pin "5") (pinfunction "D_5") (pintype "passive"))
      (node (ref "Q21") (pin "6") (pinfunction "D_6") (pintype "passive"))
      (node (ref "Q21") (pin "7") (pinfunction "D_7") (pintype "passive"))
      (node (ref "Q21") (pin "8") (pinfunction "D_8") (pintype "passive"))
      (node (ref "Q22") (pin "5") (pinfunction "D_5") (pintype "passive"))
      (node (ref "Q22") (pin "6") (pinfunction "D_6") (pintype "passive"))
      (node (ref "Q22") (pin "7") (pinfunction "D_7") (pintype "passive"))
      (node (ref "Q22") (pin "8") (pinfunction "D_8") (pintype "passive"))
      (node (ref "U17") (pin "2") (pinfunction "TS_2") (pintype "passive"))
    )
    (net (code "71") (name "/SWN11") (class "Default")
      (node (ref "C94") (pin "2") (pinfunction "2_2") (pintype "passive"))
      (node (ref "L11") (pin "1") (pinfunction "1_1") (pintype "passive"))
      (node (ref "Q27") (pin "1") (pinfunction "S_1") (pintype "passive"))
      (node (ref "Q27") (pin "2") (pinfunction "S_2") (pintype "passive"))
      (node (ref "Q27") (pin "3") (pinfunction "S_3") (pintype "passive"))
      (node (ref "Q33") (pin "5") (pinfunction "D_5") (pintype "passive"))
      (node (ref "Q33") (pin "6") (pinfunction "D_6") (pintype "passive"))
      (node (ref "Q33") (pin "7") (pinfunction "D_7") (pintype "passive"))
      (node (ref "Q33") (pin "8") (pinfunction "D_8") (pintype "passive"))
      (node (ref "Q34") (pin "5") (pinfunction "D_5") (pintype "passive"))
      (node (ref "Q34") (pin "6") (pinfunction "D_6") (pintype "passive"))
      (node (ref "Q34") (pin "7") (pinfunction "D_7") (pintype "passive"))
      (node (ref "Q34") (pin "8") (pinfunction "D_8") (pintype "passive"))
      (node (ref "U21") (pin "2") (pinfunction "TS_2") (pintype "passive"))
    )
    (net (code "72") (name "/SWN12") (class "Default")
      (node (ref "C126") (pin "2") (pinfunction "2_2") (pintype "passive"))
      (node (ref "L15") (pin "1") (pinfunction "1_1") (pintype "passive"))
      (node (ref "Q39") (pin "1") (pinfunction "S_1") (pintype "passive"))
      (node (ref "Q39") (pin "2") (pinfunction "S_2") (pintype "passive"))
      (node (ref "Q39") (pin "3") (pinfunction "S_3") (pintype "passive"))
      (node (ref "Q45") (pin "5") (pinfunction "D_5") (pintype "passive"))
      (node (ref "Q45") (pin "6") (pinfunction "D_6") (pintype "passive"))
      (node (ref "Q45") (pin "7") (pinfunction "D_7") (pintype "passive"))
      (node (ref "Q45") (pin "8") (pinfunction "D_8") (pintype "passive"))
      (node (ref "Q46") (pin "5") (pinfunction "D_5") (pintype "passive"))
      (node (ref "Q46") (pin "6") (pinfunction "D_6") (pintype "passive"))
      (node (ref "Q46") (pin "7") (pinfunction "D_7") (pintype "passive"))
      (node (ref "Q46") (pin "8") (pinfunction "D_8") (pintype "passive"))
      (node (ref "U25") (pin "2") (pinfunction "TS_2") (pintype "passive"))
    )
    (net (code "73") (name "/SWN13") (class "Default")
      (node (ref "C31") (pin "2") (pinfunction "2_2") (pintype "passive"))
      (node (ref "L4") (pin "1") (pinfunction "1_1") (pintype "passive"))
      (node (ref "Q11") (pin "5") (pinfunction "D_5") (pintype "passive"))
      (node (ref "Q11") (pin "6") (pinfunction "D_6") (pintype "passive"))
      (node (ref "Q11") (pin "7") (pinfunction "D_7") (pintype "passive"))
      (node (ref "Q11") (pin "8") (pinfunction "D_8") (pintype "passive"))
      (node (ref "Q12") (pin "5") (pinfunction "D_5") (pintype "passive"))
      (node (ref "Q12") (pin "6") (pinfunction "D_6") (pintype "passive"))
      (node (ref "Q12") (pin "7") (pinfunction "D_7") (pintype "passive"))
      (node (ref "Q12") (pin "8") (pinfunction "D_8") (pintype "passive"))
      (node (ref "Q4") (pin "1") (pinfunction "S_1") (pintype "passive"))
      (node (ref "Q4") (pin "2") (pinfunction "S_2") (pintype "passive"))
      (node (ref "Q4") (pin "3") (pinfunction "S_3") (pintype "passive"))
      (node (ref "U14") (pin "2") (pinfunction "TS_2") (pintype "passive"))
    )
    (net (code "74") (name "/SWN14") (class "Default")
      (node (ref "C63") (pin "2") (pinfunction "2_2") (pintype "passive"))
      (node (ref "L8") (pin "1") (pinfunction "1_1") (pintype "passive"))
      (node (ref "Q16") (pin "1") (pinfunction "S_1") (pintype "passive"))
      (node (ref "Q16") (pin "2") (pinfunction "S_2") (pintype "passive"))
      (node (ref "Q16") (pin "3") (pinfunction "S_3") (pintype "passive"))
      (node (ref "Q23") (pin "5") (pinfunction "D_5") (pintype "passive"))
      (node (ref "Q23") (pin "6") (pinfunction "D_6") (pintype "passive"))
      (node (ref "Q23") (pin "7") (pinfunction "D_7") (pintype "passive"))
      (node (ref "Q23") (pin "8") (pinfunction "D_8") (pintype "passive"))
      (node (ref "Q24") (pin "5") (pinfunction "D_5") (pintype "passive"))
      (node (ref "Q24") (pin "6") (pinfunction "D_6") (pintype "passive"))
      (node (ref "Q24") (pin "7") (pinfunction "D_7") (pintype "passive"))
      (node (ref "Q24") (pin "8") (pinfunction "D_8") (pintype "passive"))
      (node (ref "U18") (pin "2") (pinfunction "TS_2") (pintype "passive"))
    )
    (net (code "75") (name "/SWN15") (class "Default")
      (node (ref "C95") (pin "2") (pinfunction "2_2") (pintype "passive"))
      (node (ref "L12") (pin "1") (pinfunction "1_1") (pintype "passive"))
      (node (ref "Q28") (pin "1") (pinfunction "S_1") (pintype "passive"))
      (node (ref "Q28") (pin "2") (pinfunction "S_2") (pintype "passive"))
      (node (ref "Q28") (pin "3") (pinfunction "S_3") (pintype "passive"))
      (node (ref "Q35") (pin "5") (pinfunction "D_5") (pintype "passive"))
      (node (ref "Q35") (pin "6") (pinfunction "D_6") (pintype "passive"))
      (node (ref "Q35") (pin "7") (pinfunction "D_7") (pintype "passive"))
      (node (ref "Q35") (pin "8") (pinfunction "D_8") (pintype "passive"))
      (node (ref "Q36") (pin "5") (pinfunction "D_5") (pintype "passive"))
      (node (ref "Q36") (pin "6") (pinfunction "D_6") (pintype "passive"))
      (node (ref "Q36") (pin "7") (pinfunction "D_7") (pintype "passive"))
      (node (ref "Q36") (pin "8") (pinfunction "D_8") (pintype "passive"))
      (node (ref "U22") (pin "2") (pinfunction "TS_2") (pintype "passive"))
    )
    (net (code "76") (name "/SWN16") (class "Default")
      (node (ref "C127") (pin "2") (pinfunction "2_2") (pintype "passive"))
      (node (ref "L16") (pin "1") (pinfunction "1_1") (pintype "passive"))
      (node (ref "Q40") (pin "1") (pinfunction "S_1") (pintype "passive"))
      (node (ref "Q40") (pin "2") (pinfunction "S_2") (pintype "passive"))
      (node (ref "Q40") (pin "3") (pinfunction "S_3") (pintype "passive"))
      (node (ref "Q47") (pin "5") (pinfunction "D_5") (pintype "passive"))
      (node (ref "Q47") (pin "6") (pinfunction "D_6") (pintype "passive"))
      (node (ref "Q47") (pin "7") (pinfunction "D_7") (pintype "passive"))
      (node (ref "Q47") (pin "8") (pinfunction "D_8") (pintype "passive"))
      (node (ref "Q48") (pin "5") (pinfunction "D_5") (pintype "passive"))
      (node (ref "Q48") (pin "6") (pinfunction "D_6") (pintype "passive"))
      (node (ref "Q48") (pin "7") (pinfunction "D_7") (pintype "passive"))
      (node (ref "Q48") (pin "8") (pinfunction "D_8") (pintype "passive"))
      (node (ref "U26") (pin "2") (pinfunction "TS_2") (pintype "passive"))
    )
    (net (code "77") (name "GND") (class "Default")
      (node (ref "C100") (pin "1") (pinfunction "1_1") (pintype "passive"))
      (node (ref "C101") (pin "1") (pinfunction "1_1") (pintype "passive"))
      (node (ref "C102") (pin "1") (pinfunction "1_1") (pintype "passive"))
      (node (ref "C103") (pin "1") (pinfunction "1_1") (pintype "passive"))
      (node (ref "C104") (pin "1") (pinfunction "1_1") (pintype "passive"))
      (node (ref "C105") (pin "1") (pinfunction "1_1") (pintype "passive"))
      (node (ref "C106") (pin "1") (pinfunction "1_1") (pintype "passive"))
      (node (ref "C107") (pin "1") (pinfunction "1_1") (pintype "passive"))
      (node (ref "C108") (pin "1") (pinfunction "1_1") (pintype "passive"))
      (node (ref "C109") (pin "1") (pinfunction "1_1") (pintype "passive"))
      (node (ref "C110") (pin "1") (pinfunction "1_1") (pintype "passive"))
      (node (ref "C111") (pin "1") (pinfunction "1_1") (pintype "passive"))
      (node (ref "C112") (pin "1") (pinfunction "1_1") (pintype "passive"))
      (node (ref "C113") (pin "1") (pinfunction "1_1") (pintype "passive"))
      (node (ref "C114") (pin "1") (pinfunction "1_1") (pintype "passive"))
      (node (ref "C115") (pin "1") (pinfunction "1_1") (pintype "passive"))
      (node (ref "C116") (pin "1") (pinfunction "1_1") (pintype "passive"))
      (node (ref "C117") (pin "1") (pinfunction "1_1") (pintype "passive"))
      (node (ref "C118") (pin "1") (pinfunction "1_1") (pintype "passive"))
      (node (ref "C119") (pin "1") (pinfunction "1_1") (pintype "passive"))
      (node (ref "C120") (pin "2") (pinfunction "2_2") (pintype "passive"))
      (node (ref "C121") (pin "2") (pinfunction "2_2") (pintype "passive"))
      (node (ref "C122") (pin "2") (pinfunction "2_2") (pintype "passive"))
      (node (ref "C123") (pin "2") (pinfunction "2_2") (pintype "passive"))
      (node (ref "C128") (pin "1") (pinfunction "1_1") (pintype "passive"))
      (node (ref "C129") (pin "1") (pinfunction "1_1") (pintype "passive"))
      (node (ref "C130") (pin "1") (pinfunction "1_1") (pintype "passive"))
      (node (ref "C131") (pin "1") (pinfunction "1_1") (pintype "passive"))
      (node (ref "C132") (pin "1") (pinfunction "1_1") (pintype "passive"))
      (node (ref "C133") (pin "1") (pinfunction "1_1") (pintype "passive"))
      (node (ref "C134") (pin "1") (pinfunction "1_1") (pintype "passive"))
      (node (ref "C135") (pin "1") (pinfunction "1_1") (pintype "passive"))
      (node (ref "C136") (pin "1") (pinfunction "1_1") (pintype "passive"))
      (node (ref "C137") (pin "1") (pinfunction "1_1") (pintype "passive"))
      (node (ref "C138") (pin "1") (pinfunction "1_1") (pintype "passive"))
      (node (ref "C139") (pin "1") (pinfunction "1_1") (pintype "passive"))
      (node (ref "C140") (pin "1") (pinfunction "1_1") (pintype "passive"))
      (node (ref "C141") (pin "1") (pinfunction "1_1") (pintype "passive"))
      (node (ref "C142") (pin "1") (pinfunction "1_1") (pintype "passive"))
      (node (ref "C143") (pin "1") (pinfunction "1_1") (pintype "passive"))
      (node (ref "C144") (pin "1") (pinfunction "1_1") (pintype "passive"))
      (node (ref "C145") (pin "1") (pinfunction "1_1") (pintype "passive"))
      (node (ref "C146") (pin "1") (pinfunction "1_1") (pintype "passive"))
      (node (ref "C147") (pin "1") (pinfunction "1_1") (pintype "passive"))
      (node (ref "C20") (pin "1") (pinfunction "1_1") (pintype "passive"))
      (node (ref "C21") (pin "1") (pinfunction "1_1") (pintype "passive"))
      (node (ref "C22") (pin "1") (pinfunction "1_1") (pintype "passive"))
      (node (ref "C23") (pin "1") (pinfunction "1_1") (pintype "passive"))
      (node (ref "C24") (pin "2") (pinfunction "2_2") (pintype "passive"))
      (node (ref "C25") (pin "2") (pinfunction "2_2") (pintype "passive"))
      (node (ref "C26") (pin "2") (pinfunction "2_2") (pintype "passive"))
      (node (ref "C27") (pin "2") (pinfunction "2_2") (pintype "passive"))
      (node (ref "C32") (pin "1") (pinfunction "1_1") (pintype "passive"))
      (node (ref "C33") (pin "1") (pinfunction "1_1") (pintype "passive"))
      (node (ref "C34") (pin "1") (pinfunction "1_1") (pintype "passive"))
      (node (ref "C35") (pin "1") (pinfunction "1_1") (pintype "passive"))
      (node (ref "C36") (pin "1") (pinfunction "1_1") (pintype "passive"))
      (node (ref "C37") (pin "1") (pinfunction "1_1") (pintype "passive"))
      (node (ref "C38") (pin "1") (pinfunction "1_1") (pintype "passive"))
      (node (ref "C39") (pin "1") (pinfunction "1_1") (pintype "passive"))
      (node (ref "C40") (pin "1") (pinfunction "1_1") (pintype "passive"))
      (node (ref "C41") (pin "1") (pinfunction "1_1") (pintype "passive"))
      (node (ref "C42") (pin "1") (pinfunction "1_1") (pintype "passive"))
      (node (ref "C43") (pin "1") (pinfunction "1_1") (pintype "passive"))
      (node (ref "C44") (pin "1") (pinfunction "1_1") (pintype "passive"))
      (node (ref "C45") (pin "1") (pinfunction "1_1") (pintype "passive"))
      (node (ref "C46") (pin "1") (pinfunction "1_1") (pintype "passive"))
      (node (ref "C47") (pin "1") (pinfunction "1_1") (pintype "passive"))
      (node (ref "C48") (pin "1") (pinfunction "1_1") (pintype "passive"))
      (node (ref "C49") (pin "1") (pinfunction "1_1") (pintype "passive"))
      (node (ref "C50") (pin "1") (pinfunction "1_1") (pintype "passive"))
      (node (ref "C51") (pin "1") (pinfunction "1_1") (pintype "passive"))
      (node (ref "C52") (pin "1") (pinfunction "1_1") (pintype "passive"))
      (node (ref "C53") (pin "1") (pinfunction "1_1") (pintype "passive"))
      (node (ref "C54") (pin "1") (pinfunction "1_1") (pintype "passive"))
      (node (ref "C55") (pin "1") (pinfunction "1_1") (pintype "passive"))
      (node (ref "C56") (pin "2") (pinfunction "2_2") (pintype "passive"))
      (node (ref "C57") (pin "2") (pinfunction "2_2") (pintype "passive"))
      (node (ref "C58") (pin "2") (pinfunction "2_2") (pintype "passive"))
      (node (ref "C59") (pin "2") (pinfunction "2_2") (pintype "passive"))
      (node (ref "C64") (pin "1") (pinfunction "1_1") (pintype "passive"))
      (node (ref "C65") (pin "1") (pinfunction "1_1") (pintype "passive"))
      (node (ref "C66") (pin "1") (pinfunction "1_1") (pintype "passive"))
      (node (ref "C67") (pin "1") (pinfunction "1_1") (pintype "passive"))
      (node (ref "C68") (pin "1") (pinfunction "1_1") (pintype "passive"))
      (node (ref "C69") (pin "1") (pinfunction "1_1") (pintype "passive"))
      (node (ref "C70") (pin "1") (pinfunction "1_1") (pintype "passive"))
      (node (ref "C71") (pin "1") (pinfunction "1_1") (pintype "passive"))
      (node (ref "C72") (pin "1") (pinfunction "1_1") (pintype "passive"))
      (node (ref "C73") (pin "1") (pinfunction "1_1") (pintype "passive"))
      (node (ref "C74") (pin "1") (pinfunction "1_1") (pintype "passive"))
      (node (ref "C75") (pin "1") (pinfunction "1_1") (pintype "passive"))
      (node (ref "C76") (pin "1") (pinfunction "1_1") (pintype "passive"))
      (node (ref "C77") (pin "1") (pinfunction "1_1") (pintype "passive"))
      (node (ref "C78") (pin "1") (pinfunction "1_1") (pintype "passive"))
      (node (ref "C79") (pin "1") (pinfunction "1_1") (pintype "passive"))
      (node (ref "C80") (pin "1") (pinfunction "1_1") (pintype "passive"))
      (node (ref "C81") (pin "1") (pinfunction "1_1") (pintype "passive"))
      (node (ref "C82") (pin "1") (pinfunction "1_1") (pintype "passive"))
      (node (ref "C83") (pin "1") (pinfunction "1_1") (pintype "passive"))
      (node (ref "C84") (pin "1") (pinfunction "1_1") (pintype "passive"))
      (node (ref "C85") (pin "1") (pinfunction "1_1") (pintype "passive"))
      (node (ref "C86") (pin "1") (pinfunction "1_1") (pintype "passive"))
      (node (ref "C87") (pin "1") (pinfunction "1_1") (pintype "passive"))
      (node (ref "C88") (pin "2") (pinfunction "2_2") (pintype "passive"))
      (node (ref "C89") (pin "2") (pinfunction "2_2") (pintype "passive"))
      (node (ref "C90") (pin "2") (pinfunction "2_2") (pintype "passive"))
      (node (ref "C91") (pin "2") (pinfunction "2_2") (pintype "passive"))
      (node (ref "C96") (pin "1") (pinfunction "1_1") (pintype "passive"))
      (node (ref "C97") (pin "1") (pinfunction "1_1") (pintype "passive"))
      (node (ref "C98") (pin "1") (pinfunction "1_1") (pintype "passive"))
      (node (ref "C99") (pin "1") (pinfunction "1_1") (pintype "passive"))
      (node (ref "Q10") (pin "1") (pinfunction "S_1") (pintype "passive"))
      (node (ref "Q10") (pin "2") (pinfunction "S_2") (pintype "passive"))
      (node (ref "Q10") (pin "3") (pinfunction "S_3") (pintype "passive"))
      (node (ref "Q11") (pin "1") (pinfunction "S_1") (pintype "passive"))
      (node (ref "Q11") (pin "2") (pinfunction "S_2") (pintype "passive"))
      (node (ref "Q11") (pin "3") (pinfunction "S_3") (pintype "passive"))
      (node (ref "Q12") (pin "1") (pinfunction "S_1") (pintype "passive"))
      (node (ref "Q12") (pin "2") (pinfunction "S_2") (pintype "passive"))
      (node (ref "Q12") (pin "3") (pinfunction "S_3") (pintype "passive"))
      (node (ref "Q17") (pin "1") (pinfunction "S_1") (pintype "passive"))
      (node (ref "Q17") (pin "2") (pinfunction "S_2") (pintype "passive"))
      (node (ref "Q17") (pin "3") (pinfunction "S_3") (pintype "passive"))
      (node (ref "Q18") (pin "1") (pinfunction "S_1") (pintype "passive"))
      (node (ref "Q18") (pin "2") (pinfunction "S_2") (pintype "passive"))
      (node (ref "Q18") (pin "3") (pinfunction "S_3") (pintype "passive"))
      (node (ref "Q19") (pin "1") (pinfunction "S_1") (pintype "passive"))
      (node (ref "Q19") (pin "2") (pinfunction "S_2") (pintype "passive"))
      (node (ref "Q19") (pin "3") (pinfunction "S_3") (pintype "passive"))
      (node (ref "Q20") (pin "1") (pinfunction "S_1") (pintype "passive"))
      (node (ref "Q20") (pin "2") (pinfunction "S_2") (pintype "passive"))
      (node (ref "Q20") (pin "3") (pinfunction "S_3") (pintype "passive"))
      (node (ref "Q21") (pin "1") (pinfunction "S_1") (pintype "passive"))
      (node (ref "Q21") (pin "2") (pinfunction "S_2") (pintype "passive"))
      (node (ref "Q21") (pin "3") (pinfunction "S_3") (pintype "passive"))
      (node (ref "Q22") (pin "1") (pinfunction "S_1") (pintype "passive"))
      (node (ref "Q22") (pin "2") (pinfunction "S_2") (pintype "passive"))
      (node (ref "Q22") (pin "3") (pinfunction "S_3") (pintype "passive"))
      (node (ref "Q23") (pin "1") (pinfunction "S_1") (pintype "passive"))
      (node (ref "Q23") (pin "2") (pinfunction "S_2") (pintype "passive"))
      (node (ref "Q23") (pin "3") (pinfunction "S_3") (pintype "passive"))
      (node (ref "Q24") (pin "1") (pinfunction "S_1") (pintype "passive"))
      (node (ref "Q24") (pin "2") (pinfunction "S_2") (pintype "passive"))
      (node (ref "Q24") (pin "3") (pinfunction "S_3") (pintype "passive"))
      (node (ref "Q29") (pin "1") (pinfunction "S_1") (pintype "passive"))
      (node (ref "Q29") (pin "2") (pinfunction "S_2") (pintype "passive"))
      (node (ref "Q29") (pin "3") (pinfunction "S_3") (pintype "passive"))
      (node (ref "Q30") (pin "1") (pinfunction "S_1") (pintype "passive"))
      (node (ref "Q30") (pin "2") (pinfunction "S_2") (pintype "passive"))
      (node (ref "Q30") (pin "3") (pinfunction "S_3") (pintype "passive"))
      (node (ref "Q31") (pin "1") (pinfunction "S_1") (pintype "passive"))
      (node (ref "Q31") (pin "2") (pinfunction "S_2") (pintype "passive"))
      (node (ref "Q31") (pin "3") (pinfunction "S_3") (pintype "passive"))
      (node (ref "Q32") (pin "1") (pinfunction "S_1") (pintype "passive"))
      (node (ref "Q32") (pin "2") (pinfunction "S_2") (pintype "passive"))
      (node (ref "Q32") (pin "3") (pinfunction "S_3") (pintype "passive"))
      (node (ref "Q33") (pin "1") (pinfunction "S_1") (pintype "passive"))
      (node (ref "Q33") (pin "2") (pinfunction "S_2") (pintype "passive"))
      (node (ref "Q33") (pin "3") (pinfunction "S_3") (pintype "passive"))
      (node (ref "Q34") (pin "1") (pinfunction "S_1") (pintype "passive"))
      (node (ref "Q34") (pin "2") (pinfunction "S_2") (pintype "passive"))
      (node (ref "Q34") (pin "3") (pinfunction "S_3") (pintype "passive"))
      (node (ref "Q35") (pin "1") (pinfunction "S_1") (pintype "passive"))
      (node (ref "Q35") (pin "2") (pinfunction "S_2") (pintype "passive"))
      (node (ref "Q35") (pin "3") (pinfunction "S_3") (pintype "passive"))
      (node (ref "Q36") (pin "1") (pinfunction "S_1") (pintype "passive"))
      (node (ref "Q36") (pin "2") (pinfunction "S_2") (pintype "passive"))
      (node (ref "Q36") (pin "3") (pinfunction "S_3") (pintype "passive"))
      (node (ref "Q41") (pin "1") (pinfunction "S_1") (pintype "passive"))
      (node (ref "Q41") (pin "2") (pinfunction "S_2") (pintype "passive"))
      (node (ref "Q41") (pin "3") (pinfunction "S_3") (pintype "passive"))
      (node (ref "Q42") (pin "1") (pinfunction "S_1") (pintype "passive"))
      (node (ref "Q42") (pin "2") (pinfunction "S_2") (pintype "passive"))
      (node (ref "Q42") (pin "3") (pinfunction "S_3") (pintype "passive"))
      (node (ref "Q43") (pin "1") (pinfunction "S_1") (pintype "passive"))
      (node (ref "Q43") (pin "2") (pinfunction "S_2") (pintype "passive"))
      (node (ref "Q43") (pin "3") (pinfunction "S_3") (pintype "passive"))
      (node (ref "Q44") (pin "1") (pinfunction "S_1") (pintype "passive"))
      (node (ref "Q44") (pin "2") (pinfunction "S_2") (pintype "passive"))
      (node (ref "Q44") (pin "3") (pinfunction "S_3") (pintype "passive"))
      (node (ref "Q45") (pin "1") (pinfunction "S_1") (pintype "passive"))
      (node (ref "Q45") (pin "2") (pinfunction "S_2") (pintype "passive"))
      (node (ref "Q45") (pin "3") (pinfunction "S_3") (pintype "passive"))
      (node (ref "Q46") (pin "1") (pinfunction "S_1") (pintype "passive"))
      (node (ref "Q46") (pin "2") (pinfunction "S_2") (pintype "passive"))
      (node (ref "Q46") (pin "3") (pinfunction "S_3") (pintype "passive"))
      (node (ref "Q47") (pin "1") (pinfunction "S_1") (pintype "passive"))
      (node (ref "Q47") (pin "2") (pinfunction "S_2") (pintype "passive"))
      (node (ref "Q47") (pin "3") (pinfunction "S_3") (pintype "passive"))
      (node (ref "Q48") (pin "1") (pinfunction "S_1") (pintype "passive"))
      (node (ref "Q48") (pin "2") (pinfunction "S_2") (pintype "passive"))
      (node (ref "Q48") (pin "3") (pinfunction "S_3") (pintype "passive"))
      (node (ref "Q5") (pin "1") (pinfunction "S_1") (pintype "passive"))
      (node (ref "Q5") (pin "2") (pinfunction "S_2") (pintype "passive"))
      (node (ref "Q5") (pin "3") (pinfunction "S_3") (pintype "passive"))
      (node (ref "Q6") (pin "1") (pinfunction "S_1") (pintype "passive"))
      (node (ref "Q6") (pin "2") (pinfunction "S_2") (pintype "passive"))
      (node (ref "Q6") (pin "3") (pinfunction "S_3") (pintype "passive"))
      (node (ref "Q7") (pin "1") (pinfunction "S_1") (pintype "passive"))
      (node (ref "Q7") (pin "2") (pinfunction "S_2") (pintype "passive"))
      (node (ref "Q7") (pin "3") (pinfunction "S_3") (pintype "passive"))
      (node (ref "Q8") (pin "1") (pinfunction "S_1") (pintype "passive"))
      (node (ref "Q8") (pin "2") (pinfunction "S_2") (pintype "passive"))
      (node (ref "Q8") (pin "3") (pinfunction "S_3") (pintype "passive"))
      (node (ref "Q9") (pin "1") (pinfunction "S_1") (pintype "passive"))
      (node (ref "Q9") (pin "2") (pinfunction "S_2") (pintype "passive"))
      (node (ref "Q9") (pin "3") (pinfunction "S_3") (pintype "passive"))
      (node (ref "U11") (pin "4") (pinfunction "GND_4") (pintype "passive"))
      (node (ref "U11") (pin "9") (pinfunction "EP_9") (pintype "passive"))
      (node (ref "U12") (pin "4") (pinfunction "GND_4") (pintype "passive"))
      (node (ref "U12") (pin "9") (pinfunction "EP_9") (pintype "passive"))
      (node (ref "U13") (pin "4") (pinfunction "GND_4") (pintype "passive"))
      (node (ref "U13") (pin "9") (pinfunction "EP_9") (pintype "passive"))
      (node (ref "U14") (pin "4") (pinfunction "GND_4") (pintype "passive"))
      (node (ref "U14") (pin "9") (pinfunction "EP_9") (pintype "passive"))
      (node (ref "U15") (pin "4") (pinfunction "GND_4") (pintype "passive"))
      (node (ref "U15") (pin "9") (pinfunction "EP_9") (pintype "passive"))
      (node (ref "U16") (pin "4") (pinfunction "GND_4") (pintype "passive"))
      (node (ref "U16") (pin "9") (pinfunction "EP_9") (pintype "passive"))
      (node (ref "U17") (pin "4") (pinfunction "GND_4") (pintype "passive"))
      (node (ref "U17") (pin "9") (pinfunction "EP_9") (pintype "passive"))
      (node (ref "U18") (pin "4") (pinfunction "GND_4") (pintype "passive"))
      (node (ref "U18") (pin "9") (pinfunction "EP_9") (pintype "passive"))
      (node (ref "U19") (pin "4") (pinfunction "GND_4") (pintype "passive"))
      (node (ref "U19") (pin "9") (pinfunction "EP_9") (pintype "passive"))
      (node (ref "U20") (pin "4") (pinfunction "GND_4") (pintype "passive"))
      (node (ref "U20") (pin "9") (pinfunction "EP_9") (pintype "passive"))
      (node (ref "U21") (pin "4") (pinfunction "GND_4") (pintype "passive"))
      (node (ref "U21") (pin "9") (pinfunction "EP_9") (pintype "passive"))
      (node (ref "U22") (pin "4") (pinfunction "GND_4") (pintype "passive"))
      (node (ref "U22") (pin "9") (pinfunction "EP_9") (pintype "passive"))
      (node (ref "U23") (pin "4") (pinfunction "GND_4") (pintype "passive"))
      (node (ref "U23") (pin "9") (pinfunction "EP_9") (pintype "passive"))
      (node (ref "U24") (pin "4") (pinfunction "GND_4") (pintype "passive"))
      (node (ref "U24") (pin "9") (pinfunction "EP_9") (pintype "passive"))
      (node (ref "U25") (pin "4") (pinfunction "GND_4") (pintype "passive"))
      (node (ref "U25") (pin "9") (pinfunction "EP_9") (pintype "passive"))
      (node (ref "U26") (pin "4") (pinfunction "GND_4") (pintype "passive"))
      (node (ref "U26") (pin "9") (pinfunction "EP_9") (pintype "passive"))
    )
  )
)
